# openadc_ztex.net
KiCad netlist of a schematic drawn in EAGLE
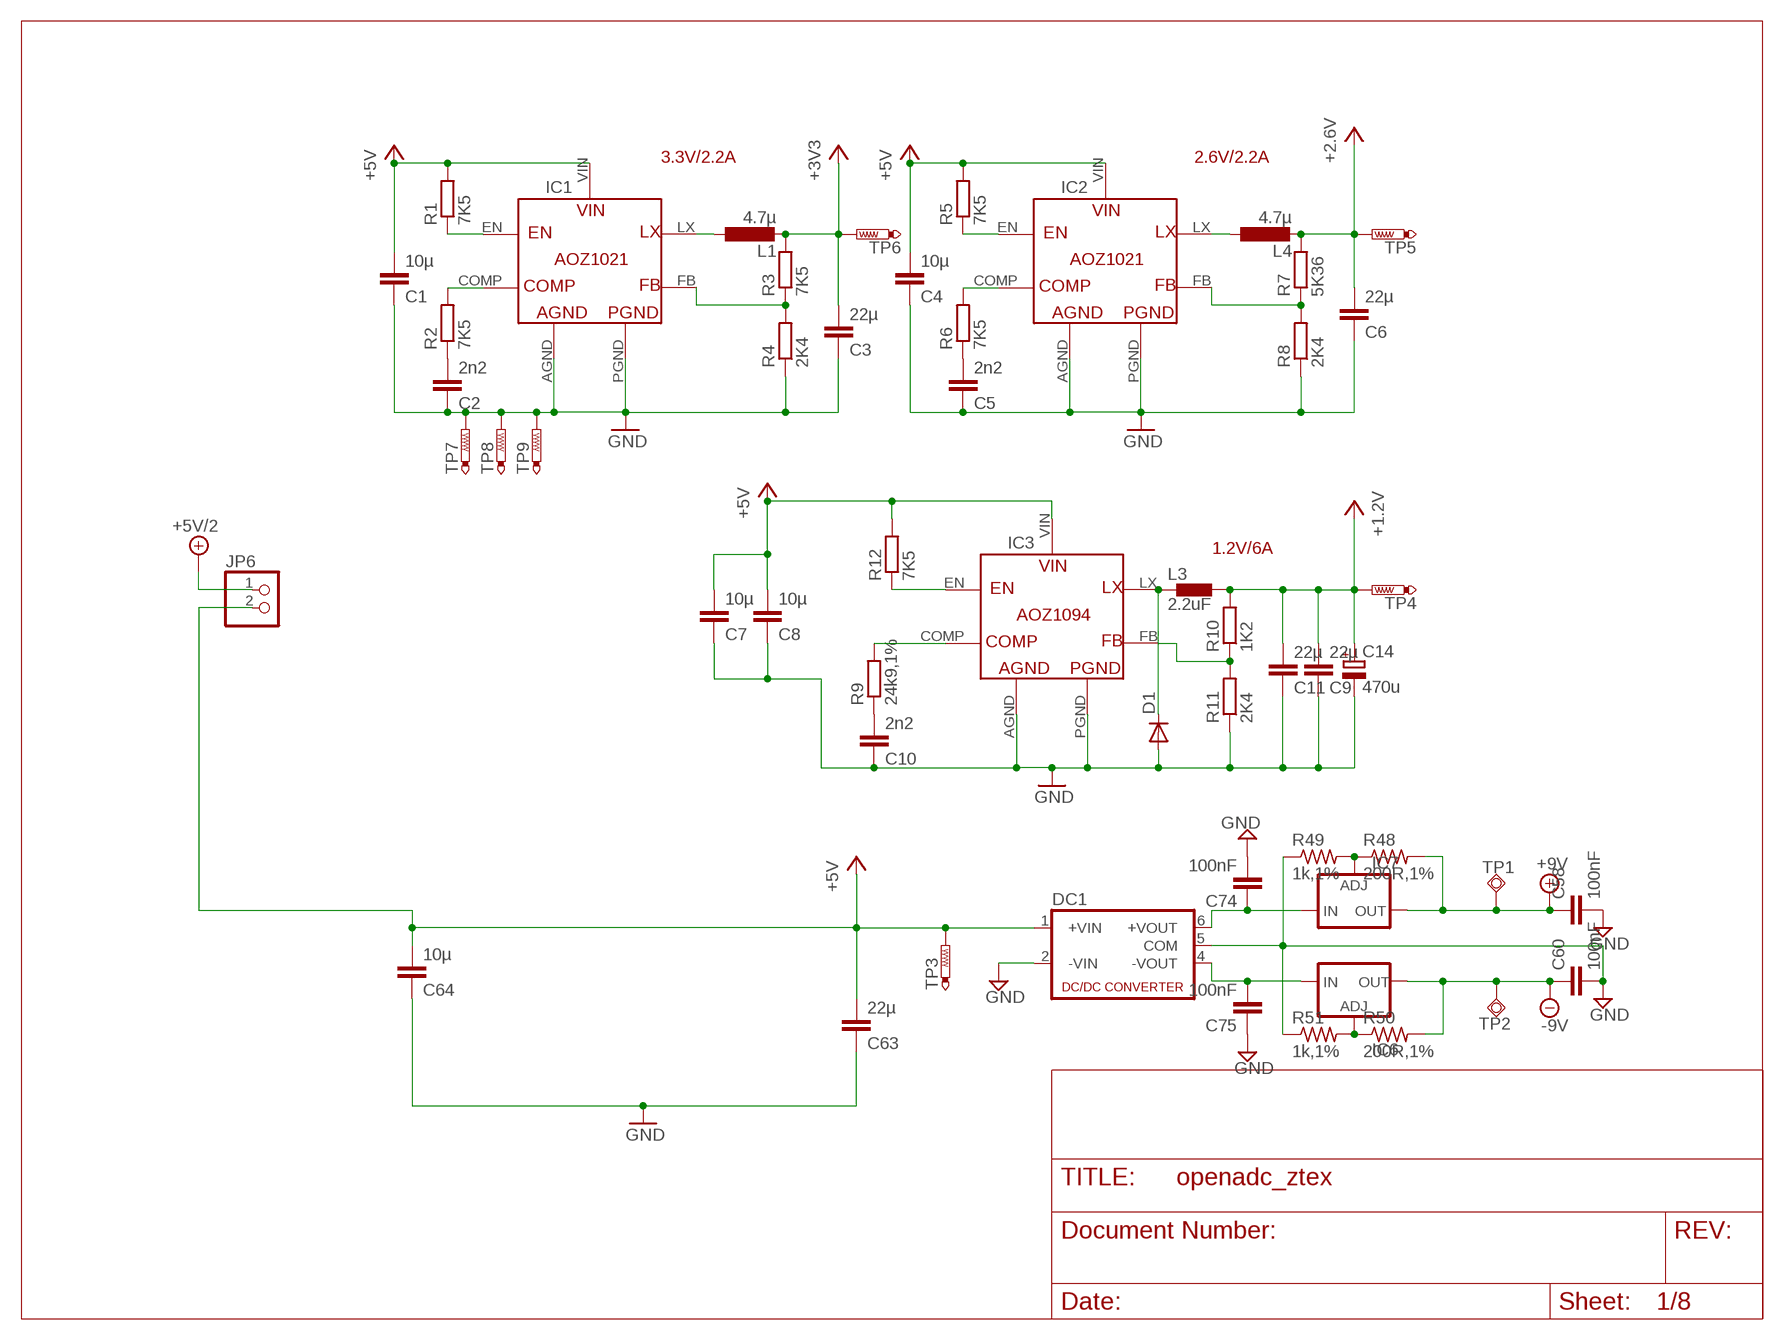
[diagram p0: schematic, sheet 1]
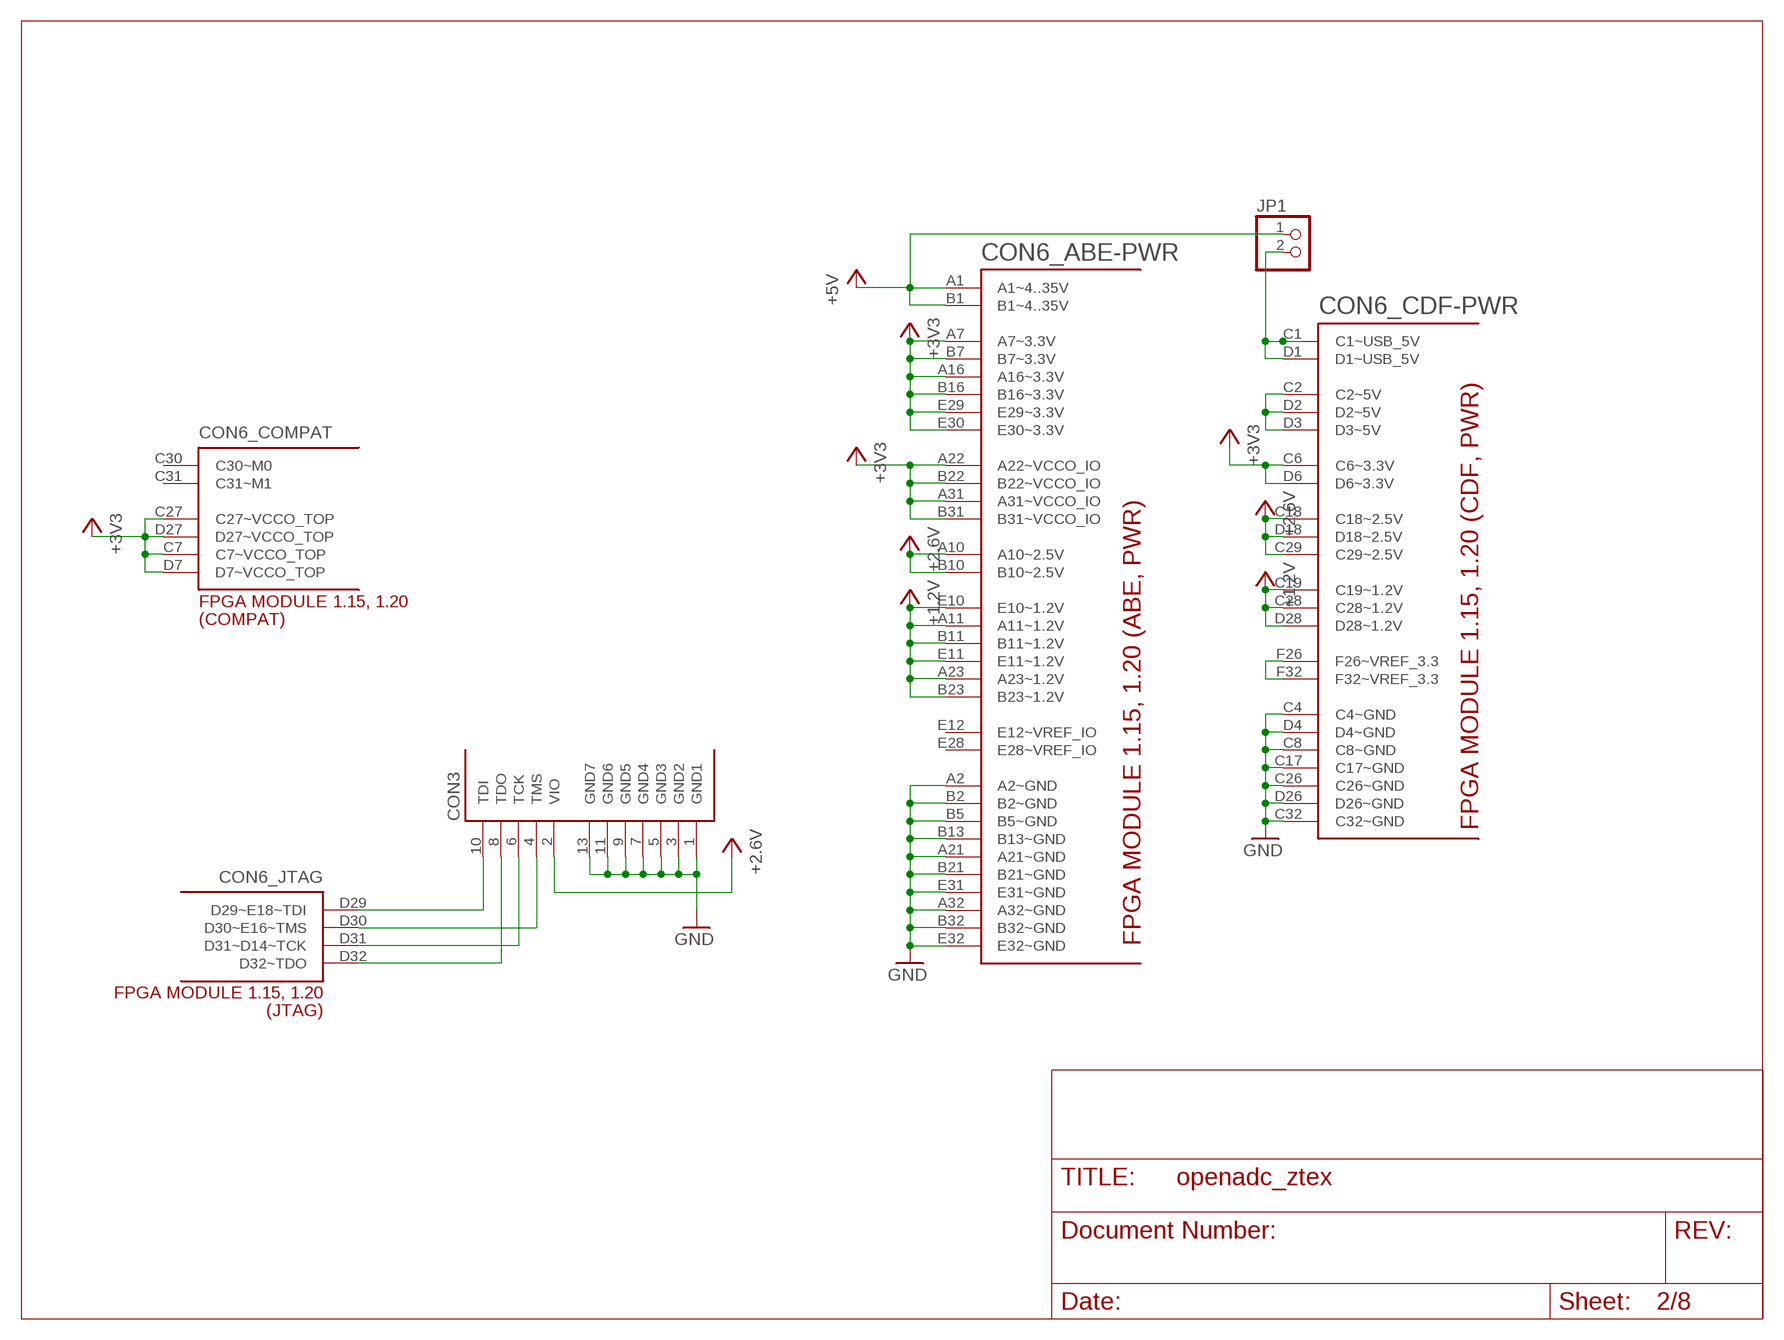
[diagram p1: schematic, sheet 2]
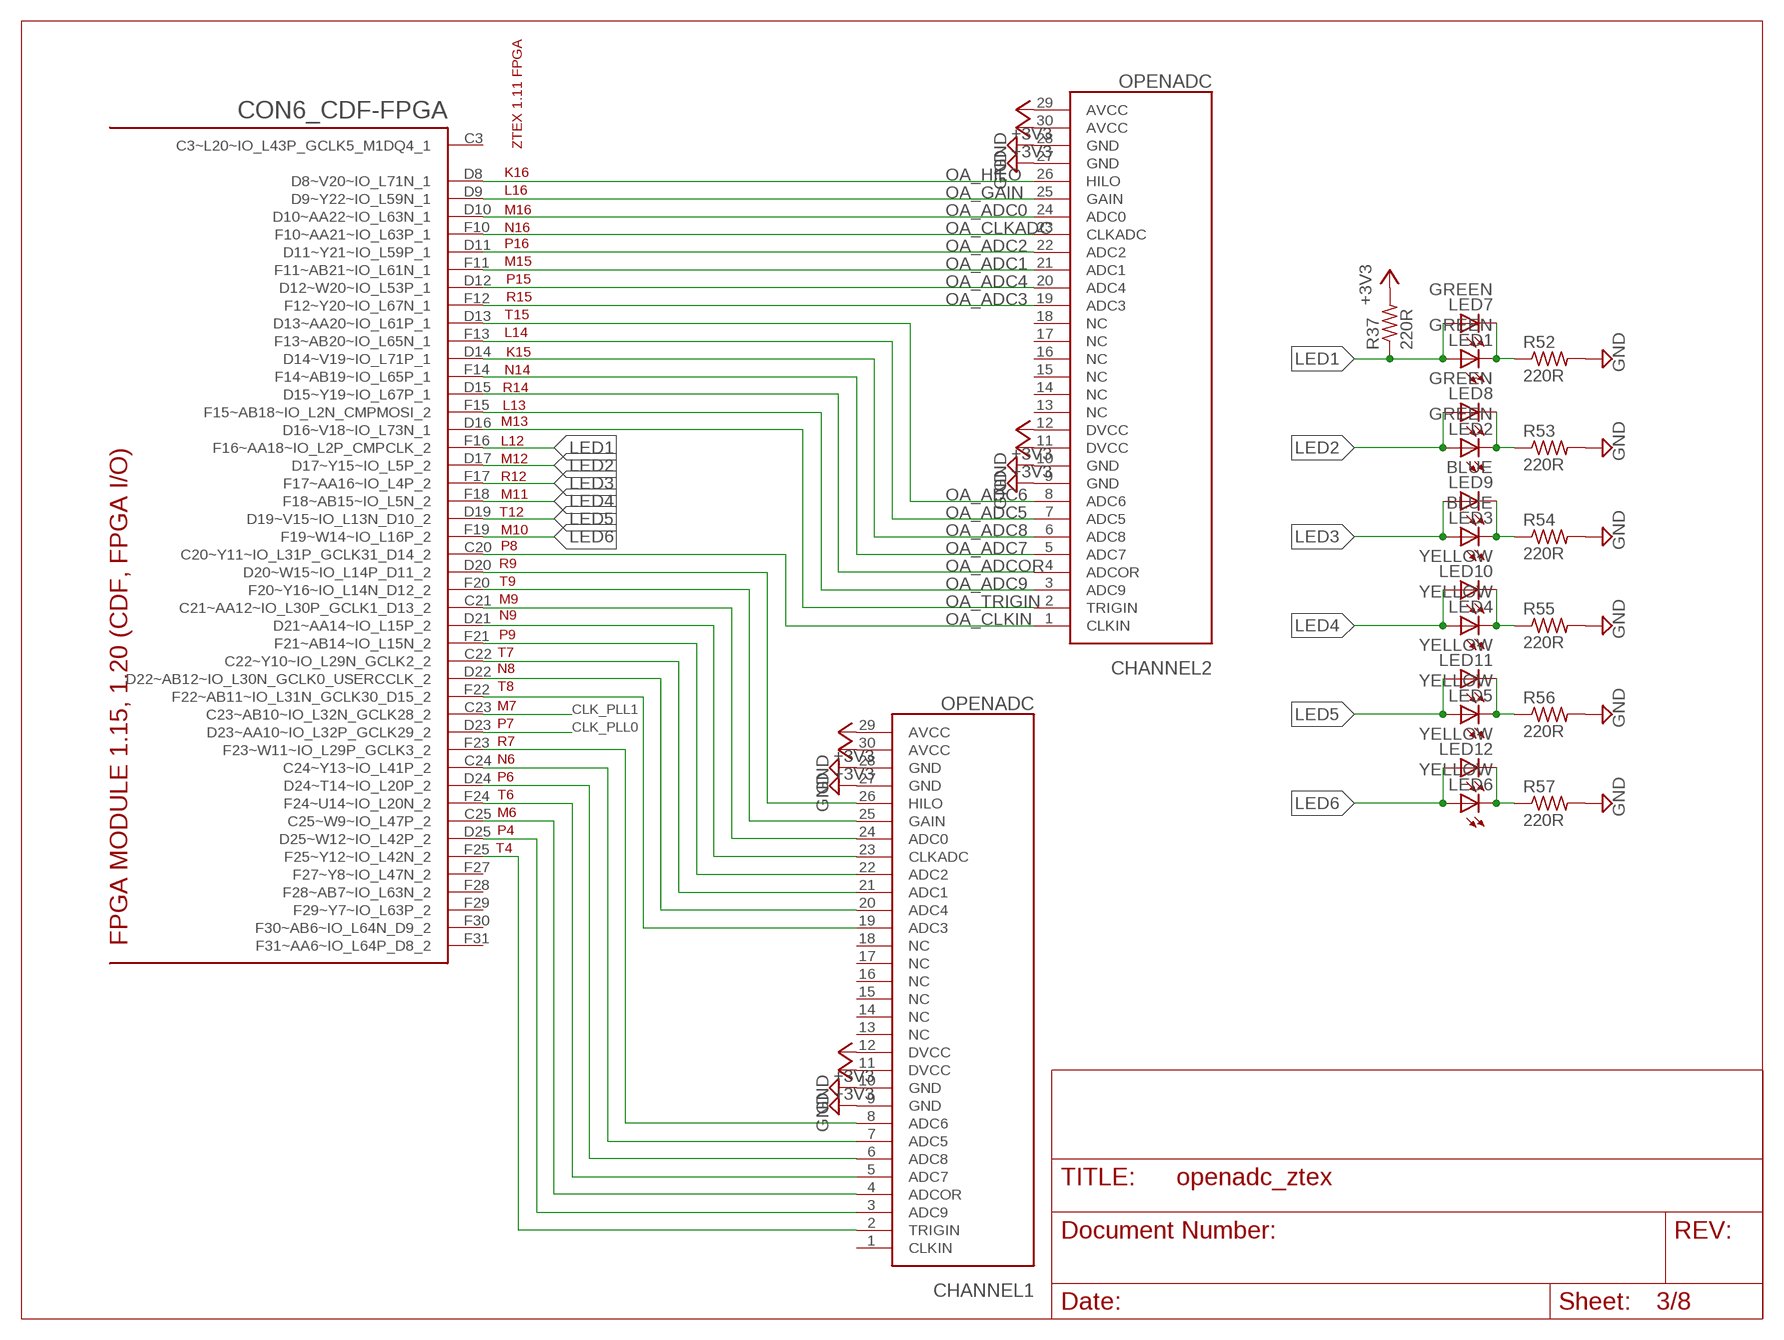
[diagram p2: schematic, sheet 3]
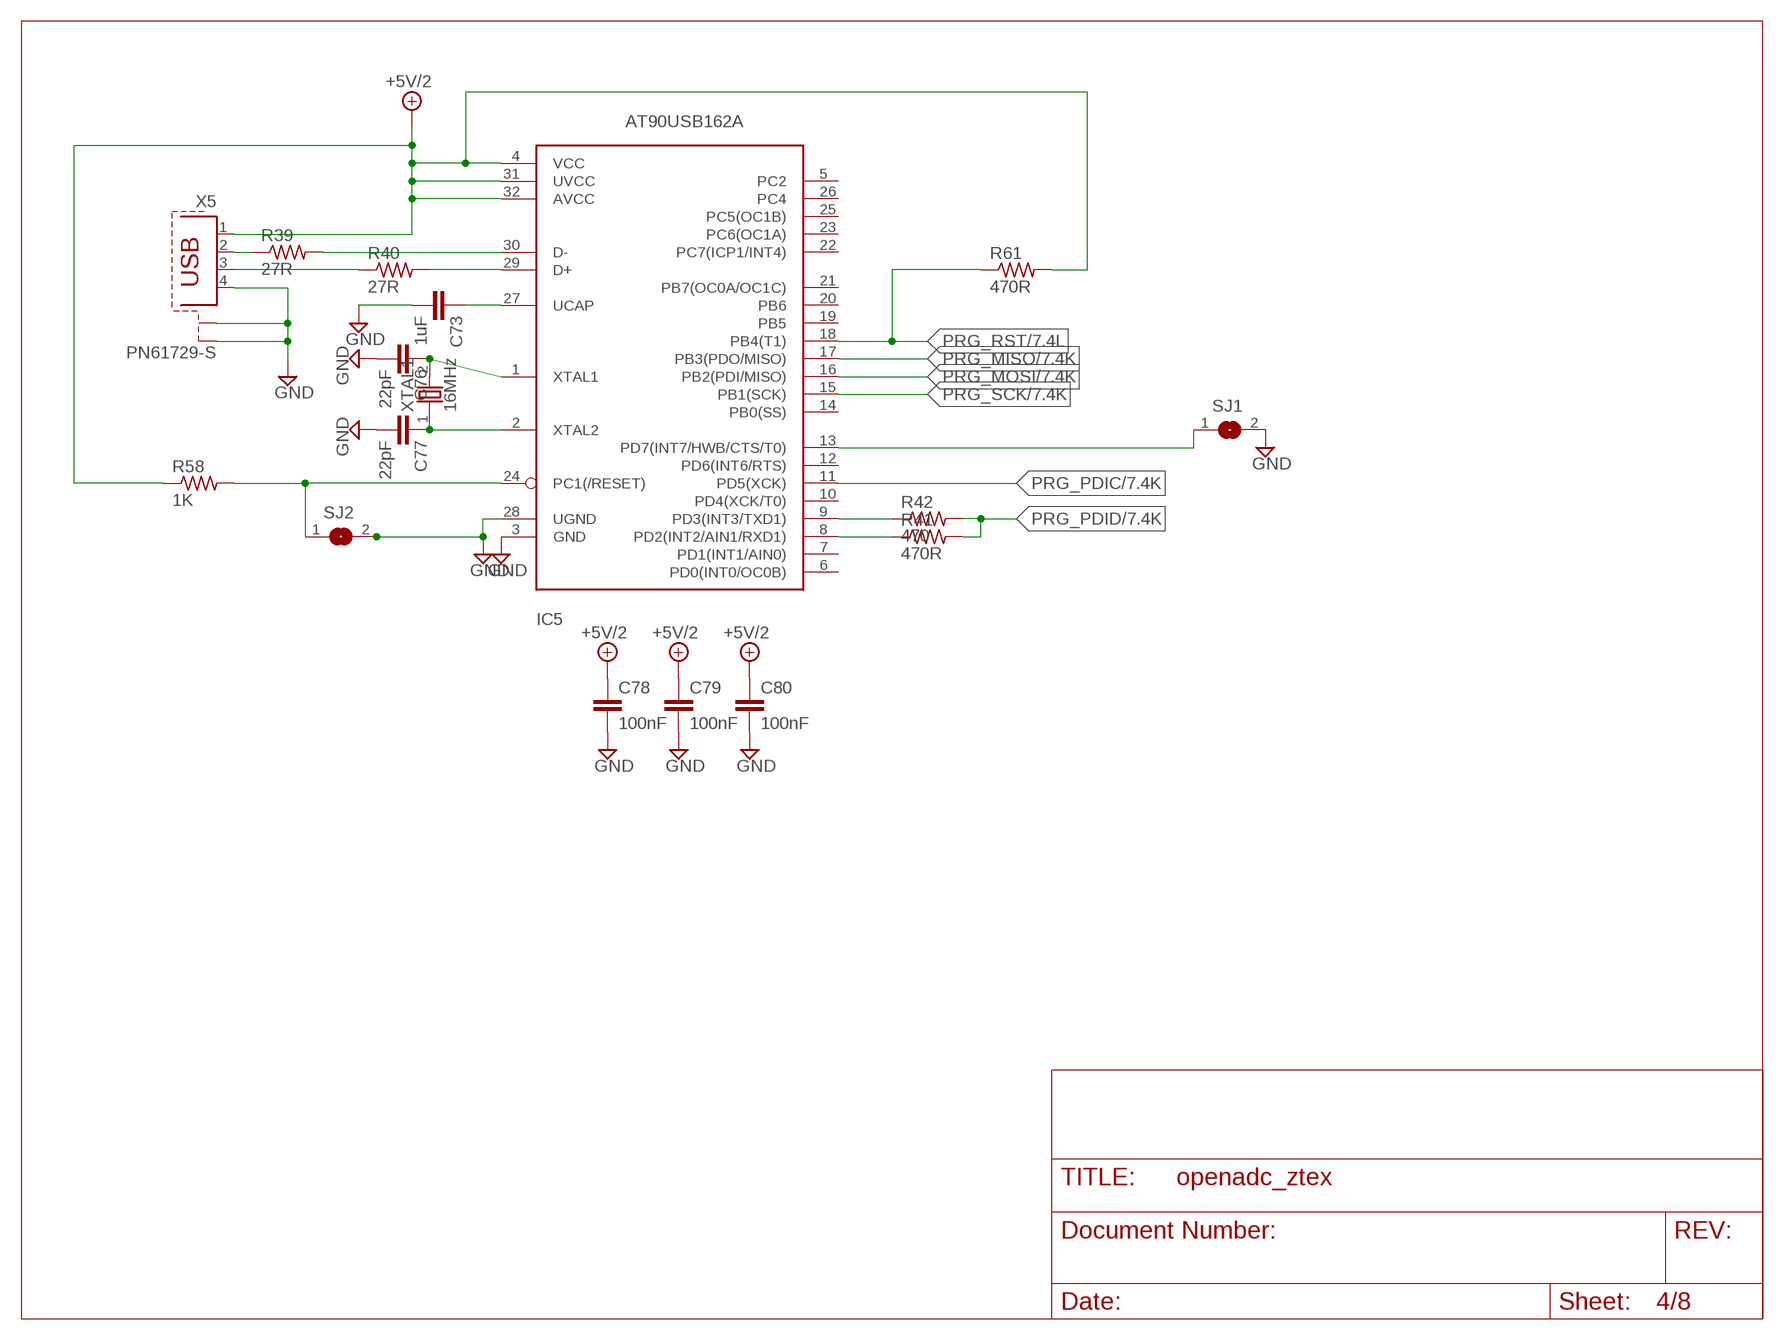
[diagram p3: schematic, sheet 4]
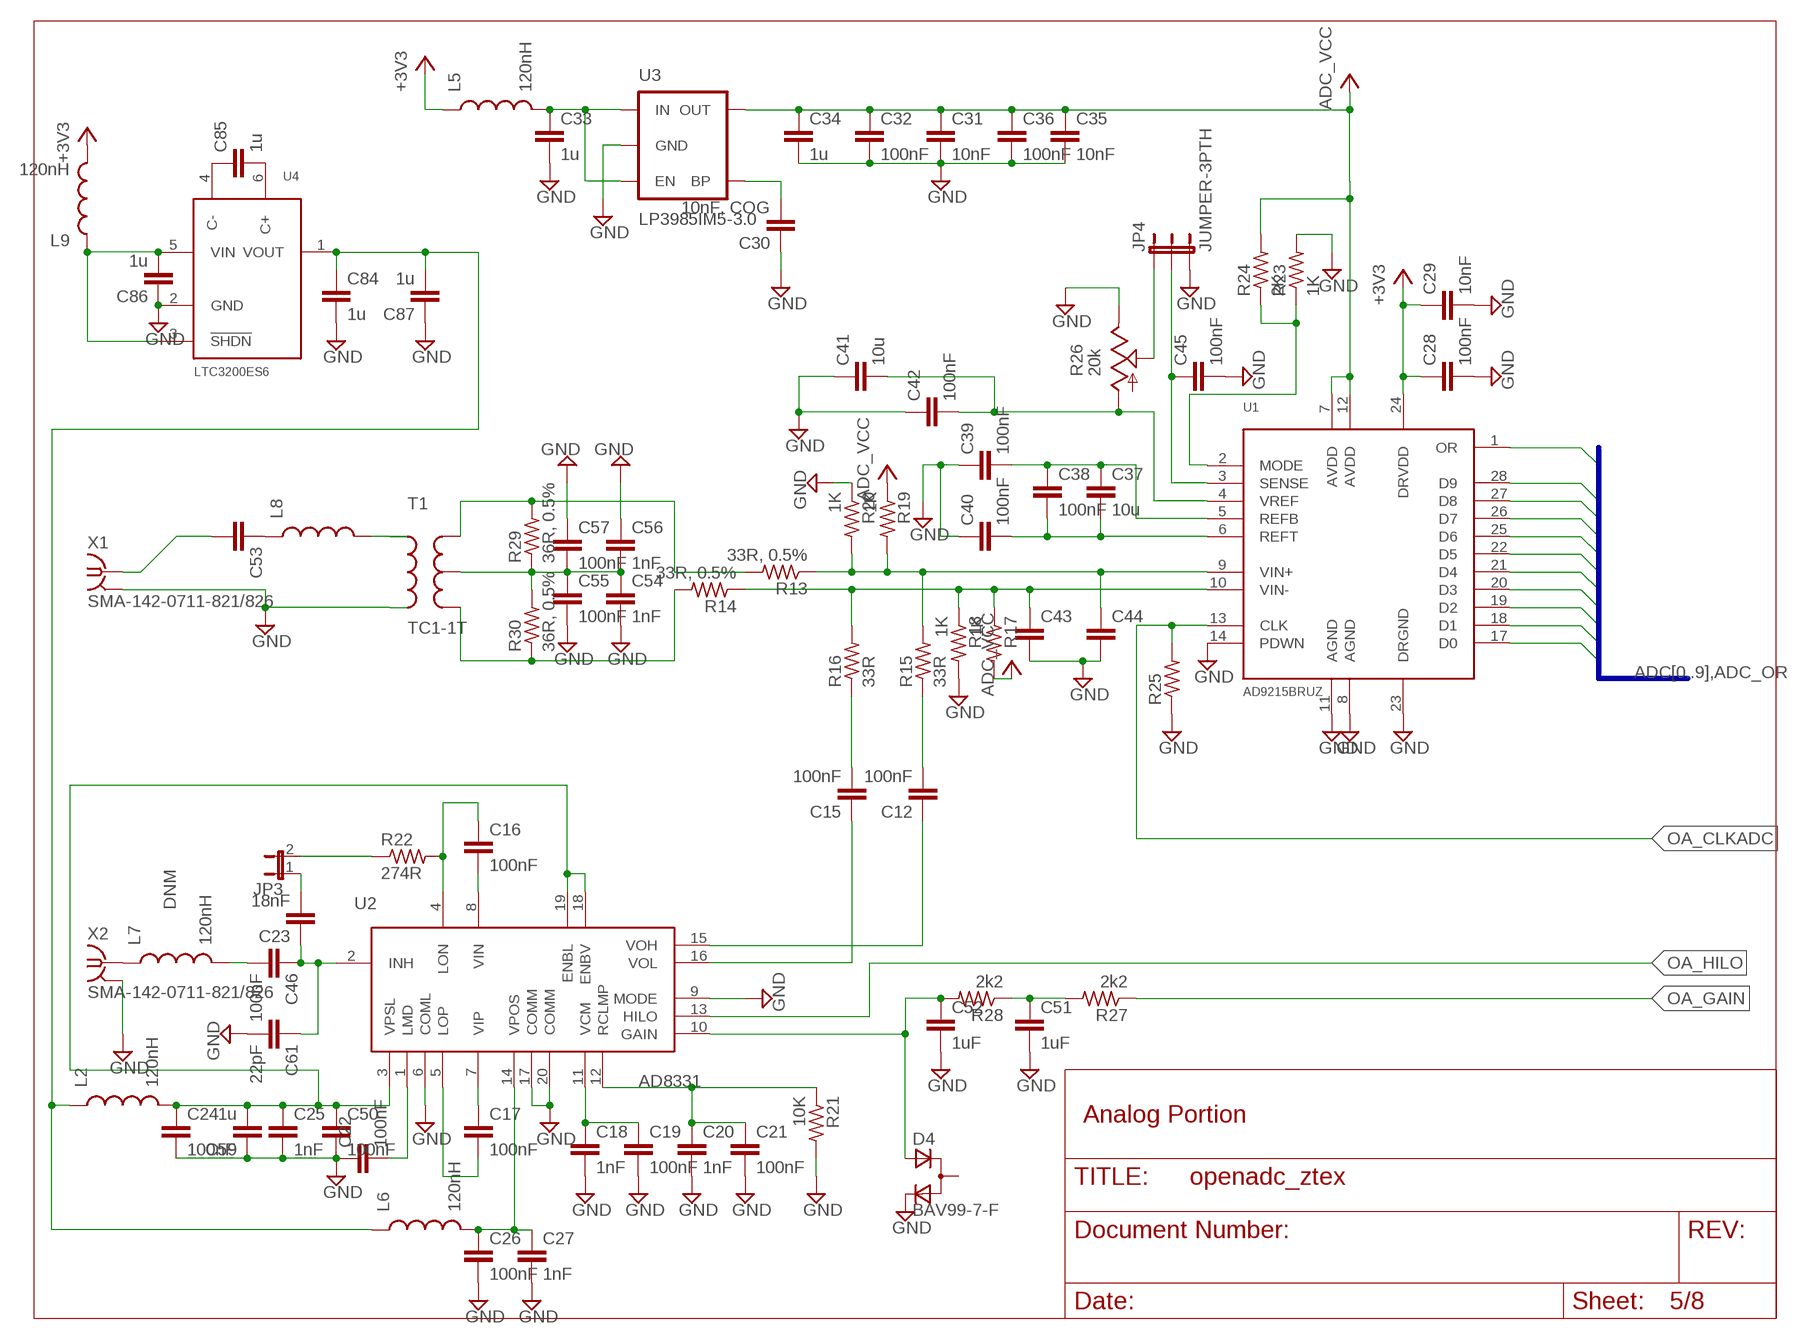
[diagram p4: schematic, sheet 5]
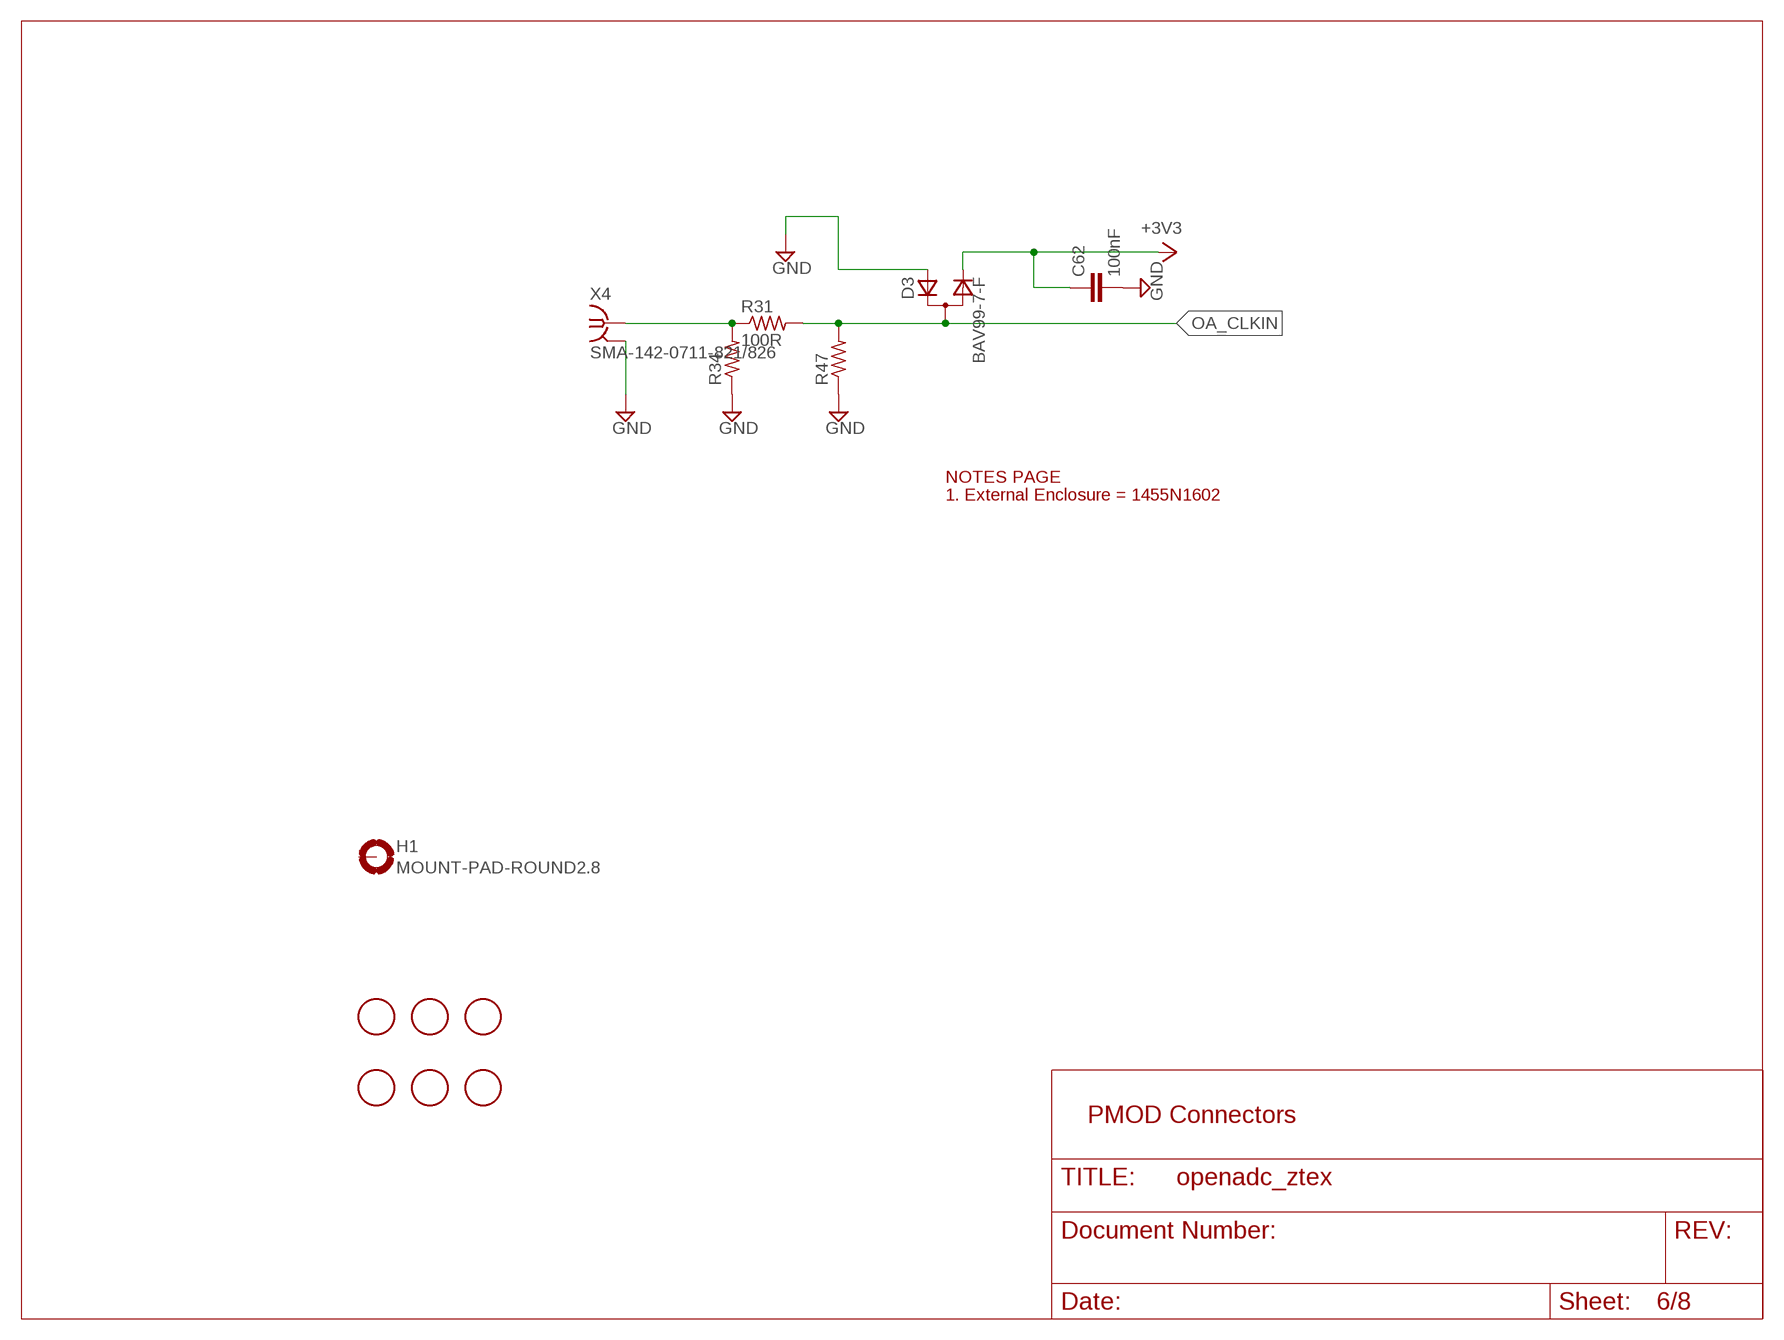
[diagram p5: schematic, sheet 6]
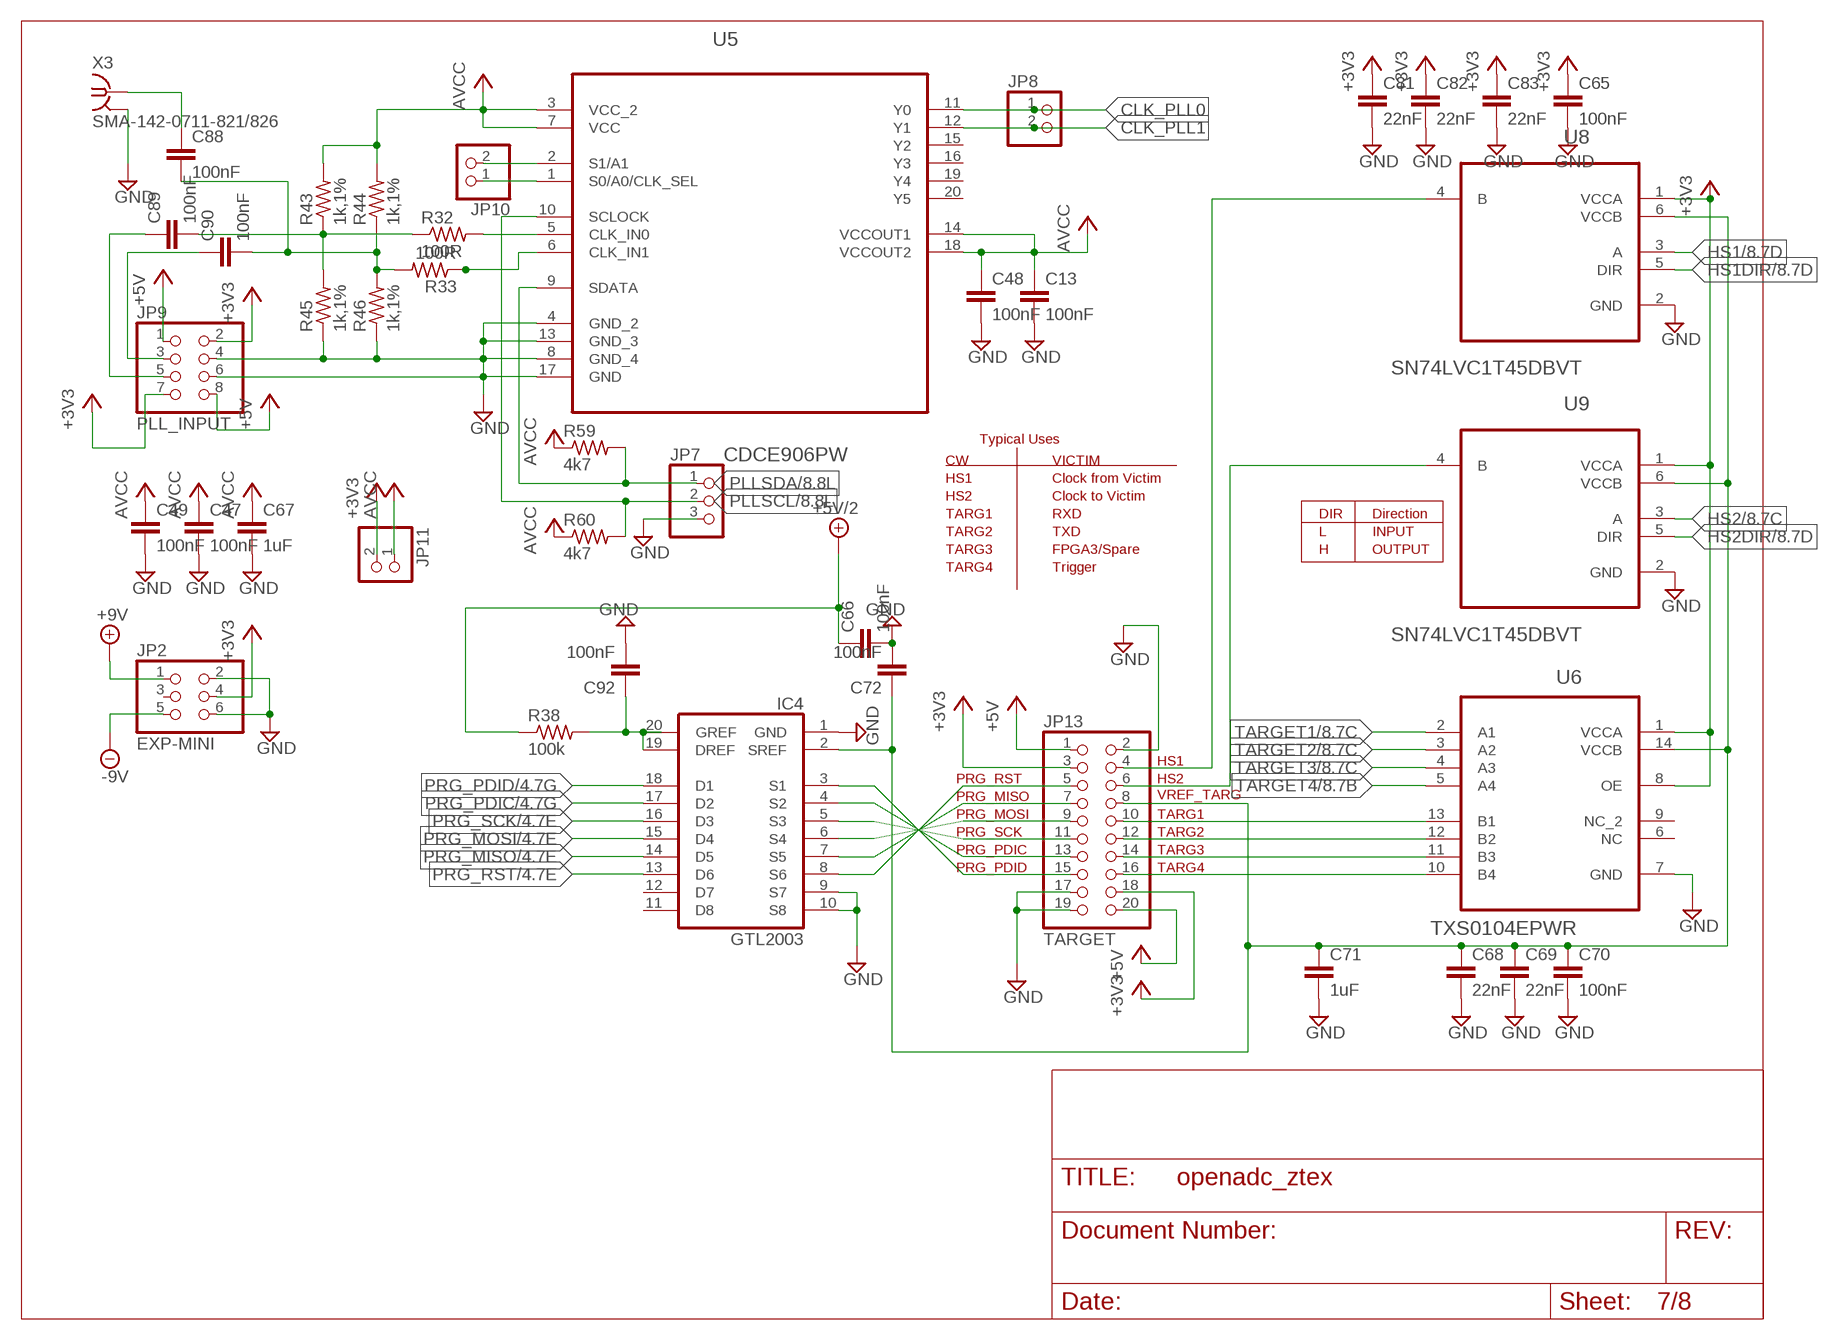
[diagram p6: schematic, sheet 7]
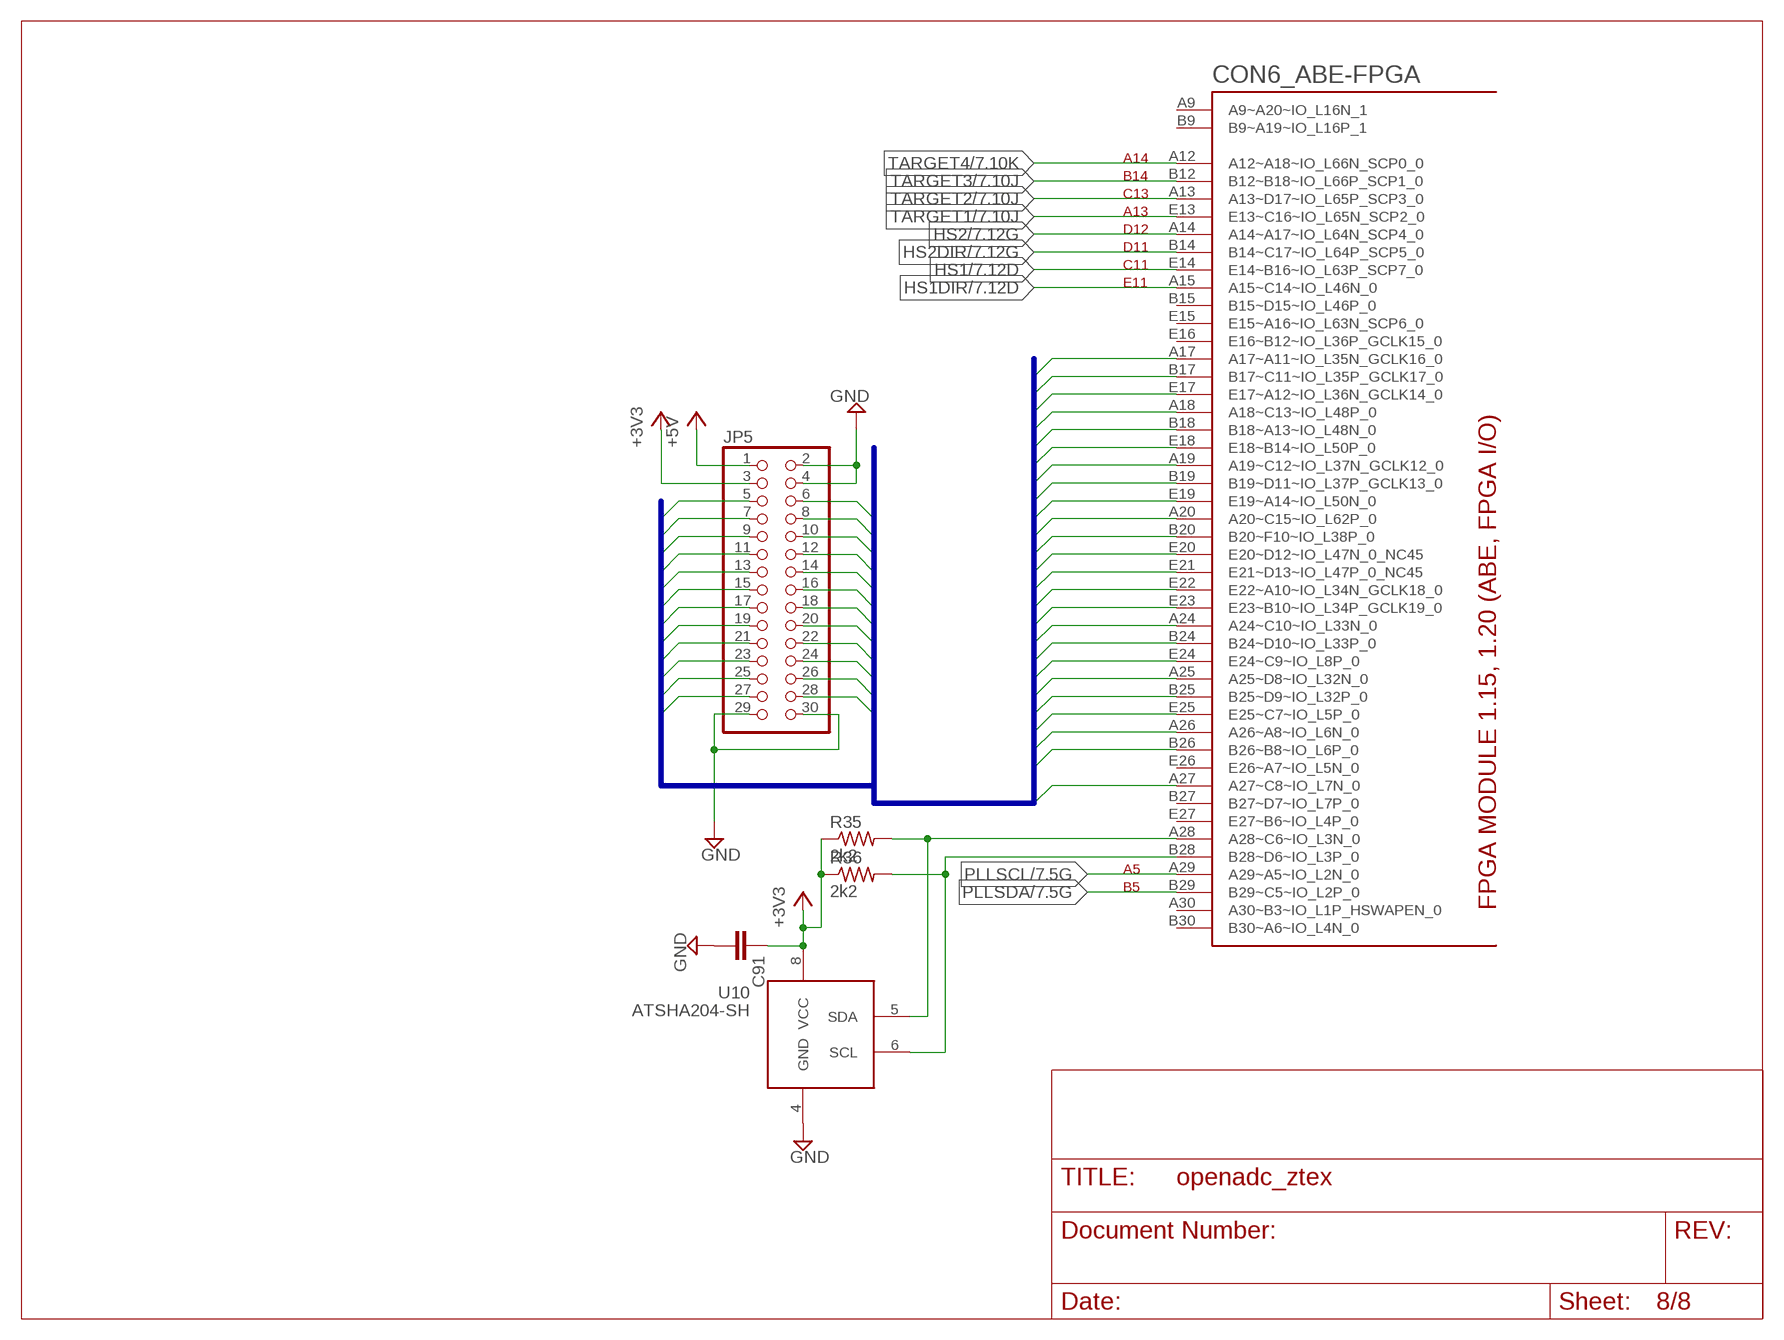
[diagram p7: schematic, sheet 8]

(export (version "E")
  (design (tool "Eeschema 10.0.6"))
  (components
    (comp (ref "C12")
      (value "100nF")
      (footprint "eagle-import:C0603K")
      (libsource (lib "eagle-import") (part "rcl_C-EUC0603K"))
    )
    (comp (ref "C15")
      (value "100nF")
      (footprint "eagle-import:C0603K")
      (libsource (lib "eagle-import") (part "rcl_C-EUC0603K"))
    )
    (comp (ref "C16")
      (value "100nF")
      (footprint "eagle-import:C0402")
      (libsource (lib "eagle-import") (part "rcl_C-EUC0402"))
    )
    (comp (ref "C17")
      (value "100nF")
      (footprint "eagle-import:C0402")
      (libsource (lib "eagle-import") (part "rcl_C-EUC0402"))
    )
    (comp (ref "C18")
      (value "1nF")
      (footprint "eagle-import:C0402")
      (fields (field (name "PART#") "C1005X7R1E102K"))
      (libsource (lib "eagle-import") (part "rcl_C-EUC0402"))
    )
    (comp (ref "C19")
      (value "100nF")
      (footprint "eagle-import:C0402")
      (fields (field (name "PART#") "GRM155R61A104KA01D"))
      (libsource (lib "eagle-import") (part "rcl_C-EUC0402"))
    )
    (comp (ref "C20")
      (value "1nF")
      (footprint "eagle-import:C0402")
      (fields (field (name "PART#") "C1005X7R1E102K"))
      (libsource (lib "eagle-import") (part "rcl_C-EUC0402"))
    )
    (comp (ref "C21")
      (value "100nF")
      (footprint "eagle-import:C0402")
      (fields (field (name "PART#") "GRM155R61A104KA01D"))
      (libsource (lib "eagle-import") (part "rcl_C-EUC0402"))
    )
    (comp (ref "C22")
      (value "100nF")
      (footprint "eagle-import:C0402")
      (fields (field (name "PART#") "GRM155R61A104KA01D"))
      (libsource (lib "eagle-import") (part "rcl_C-EUC0402"))
    )
    (comp (ref "C23")
      (value "18nF")
      (footprint "eagle-import:C0603")
      (libsource (lib "eagle-import") (part "rcl_C-EUC0603"))
    )
    (comp (ref "C24")
      (value "100nF")
      (footprint "eagle-import:C0402")
      (fields (field (name "PART#") "GRM155R61A104KA01D"))
      (libsource (lib "eagle-import") (part "rcl_C-EUC0402"))
    )
    (comp (ref "C25")
      (value "1nF")
      (footprint "eagle-import:C0402")
      (fields (field (name "PART#") "C1005X7R1E102K"))
      (libsource (lib "eagle-import") (part "rcl_C-EUC0402"))
    )
    (comp (ref "C26")
      (value "100nF")
      (footprint "eagle-import:C0402")
      (fields (field (name "PART#") "GRM155R61A104KA01D"))
      (libsource (lib "eagle-import") (part "rcl_C-EUC0402"))
    )
    (comp (ref "C27")
      (value "1nF")
      (footprint "eagle-import:C0402")
      (fields (field (name "PART#") "C1005X7R1E102K"))
      (libsource (lib "eagle-import") (part "rcl_C-EUC0402"))
    )
    (comp (ref "C28")
      (value "100nF")
      (footprint "eagle-import:C0402")
      (fields (field (name "PART#") "GRM155R61A104KA01D"))
      (libsource (lib "eagle-import") (part "rcl_C-EUC0402"))
    )
    (comp (ref "C29")
      (value "10nF")
      (footprint "eagle-import:C0402")
      (libsource (lib "eagle-import") (part "rcl_C-EUC0402"))
    )
    (comp (ref "C30")
      (value "10nF, COG")
      (footprint "eagle-import:C0402")
      (libsource (lib "eagle-import") (part "rcl_C-EUC0402"))
    )
    (comp (ref "C31")
      (value "10nF")
      (footprint "eagle-import:C0402")
      (fields (field (name "PART#") "GRM155R71E103KA01D"))
      (libsource (lib "eagle-import") (part "rcl_C-EUC0402"))
    )
    (comp (ref "C32")
      (value "100nF")
      (footprint "eagle-import:C0402")
      (fields (field (name "PART#") "GRM155R61A104KA01D"))
      (libsource (lib "eagle-import") (part "rcl_C-EUC0402"))
    )
    (comp (ref "C33")
      (value "1u")
      (footprint "eagle-import:C0603")
      (fields (field (name "PART#") "GRM188R61A105KA61D"))
      (libsource (lib "eagle-import") (part "rcl_C-EUC0603"))
    )
    (comp (ref "C34")
      (value "1u")
      (footprint "eagle-import:C0603")
      (fields (field (name "PART#") "GRM188R61A105KA61D"))
      (libsource (lib "eagle-import") (part "rcl_C-EUC0603"))
    )
    (comp (ref "C35")
      (value "10nF")
      (footprint "eagle-import:C0402")
      (fields (field (name "PART#") "GRM155R71E103KA01D"))
      (libsource (lib "eagle-import") (part "rcl_C-EUC0402"))
    )
    (comp (ref "C36")
      (value "100nF")
      (footprint "eagle-import:C0402")
      (fields (field (name "PART#") "GRM155R61A104KA01D"))
      (libsource (lib "eagle-import") (part "rcl_C-EUC0402"))
    )
    (comp (ref "C37")
      (value "10u")
      (footprint "eagle-import:C0603")
      (libsource (lib "eagle-import") (part "rcl_C-EUC0603"))
    )
    (comp (ref "C38")
      (value "100nF")
      (footprint "eagle-import:C0402")
      (fields (field (name "PART#") "GRM155R61A104KA01D"))
      (libsource (lib "eagle-import") (part "rcl_C-EUC0402"))
    )
    (comp (ref "C39")
      (value "100nF")
      (footprint "eagle-import:C0402")
      (fields (field (name "PART#") "GRM155R61A104KA01D"))
      (libsource (lib "eagle-import") (part "rcl_C-EUC0402"))
    )
    (comp (ref "C40")
      (value "100nF")
      (footprint "eagle-import:C0402")
      (fields (field (name "PART#") "GRM155R61A104KA01D"))
      (libsource (lib "eagle-import") (part "rcl_C-EUC0402"))
    )
    (comp (ref "C41")
      (value "10u")
      (footprint "eagle-import:C0603")
      (libsource (lib "eagle-import") (part "rcl_C-EUC0603"))
    )
    (comp (ref "C42")
      (value "100nF")
      (footprint "eagle-import:C0402")
      (fields (field (name "PART#") "GRM155R61A104KA01D"))
      (libsource (lib "eagle-import") (part "rcl_C-EUC0402"))
    )
    (comp (ref "C43")
      (value "C-EUC0402")
      (footprint "eagle-import:C0402")
      (libsource (lib "eagle-import") (part "rcl_C-EUC0402"))
    )
    (comp (ref "C44")
      (value "C-EUC0402")
      (footprint "eagle-import:C0402")
      (libsource (lib "eagle-import") (part "rcl_C-EUC0402"))
    )
    (comp (ref "C45")
      (value "100nF")
      (footprint "eagle-import:C0402")
      (fields (field (name "PART#") "GRM155R61A104KA01D"))
      (libsource (lib "eagle-import") (part "rcl_C-EUC0402"))
    )
    (comp (ref "C46")
      (value "100nF")
      (footprint "eagle-import:C0603K")
      (libsource (lib "eagle-import") (part "rcl_C-EUC0603K"))
    )
    (comp (ref "C50")
      (value "100nF")
      (footprint "eagle-import:C0402")
      (fields (field (name "PART#") "GRM155R61A104KA01D"))
      (libsource (lib "eagle-import") (part "rcl_C-EUC0402"))
    )
    (comp (ref "C51")
      (value "1uF")
      (footprint "eagle-import:C0603")
      (libsource (lib "eagle-import") (part "rcl_C-EUC0603"))
    )
    (comp (ref "C52")
      (value "1uF")
      (footprint "eagle-import:C0603")
      (libsource (lib "eagle-import") (part "rcl_C-EUC0603"))
    )
    (comp (ref "C53")
      (value "C-EUC0603K")
      (footprint "eagle-import:C0603K")
      (libsource (lib "eagle-import") (part "rcl_C-EUC0603K"))
    )
    (comp (ref "C54")
      (value "1nF")
      (footprint "eagle-import:C0402")
      (fields (field (name "PART#") "C1005X7R1E102K"))
      (libsource (lib "eagle-import") (part "rcl_C-EUC0402"))
    )
    (comp (ref "C55")
      (value "100nF")
      (footprint "eagle-import:C0402")
      (fields (field (name "PART#") "GRM155R61A104KA01D"))
      (libsource (lib "eagle-import") (part "rcl_C-EUC0402"))
    )
    (comp (ref "C56")
      (value "1nF")
      (footprint "eagle-import:C0402")
      (fields (field (name "PART#") "C1005X7R1E102K"))
      (libsource (lib "eagle-import") (part "rcl_C-EUC0402"))
    )
    (comp (ref "C57")
      (value "100nF")
      (footprint "eagle-import:C0402")
      (fields (field (name "PART#") "GRM155R61A104KA01D"))
      (libsource (lib "eagle-import") (part "rcl_C-EUC0402"))
    )
    (comp (ref "C59")
      (value "1u")
      (footprint "eagle-import:C0402")
      (fields (field (name "PART#") "GRM188R61A105KA61D"))
      (libsource (lib "eagle-import") (part "rcl_C-EUC0402"))
    )
    (comp (ref "C61")
      (value "22pF")
      (footprint "eagle-import:C0603")
      (libsource (lib "eagle-import") (part "rcl_C-EUC0603"))
    )
    (comp (ref "C84")
      (value "1u")
      (footprint "eagle-import:C0603")
      (fields (field (name "PART#") "GRM188R61A105KA61D"))
      (libsource (lib "eagle-import") (part "rcl_C-EUC0603"))
    )
    (comp (ref "C85")
      (value "1u")
      (footprint "eagle-import:C0603")
      (fields (field (name "PART#") "GRM188R61A105KA61D"))
      (libsource (lib "eagle-import") (part "rcl_C-EUC0603"))
    )
    (comp (ref "C86")
      (value "1u")
      (footprint "eagle-import:C0603")
      (fields (field (name "PART#") "GRM188R61A105KA61D"))
      (libsource (lib "eagle-import") (part "rcl_C-EUC0603"))
    )
    (comp (ref "C87")
      (value "1u")
      (footprint "eagle-import:C0603")
      (fields (field (name "PART#") "GRM188R61A105KA61D"))
      (libsource (lib "eagle-import") (part "rcl_C-EUC0603"))
    )
    (comp (ref "D4")
      (value "BAV99-7-F")
      (footprint "eagle-import:SOT-23")
      (libsource (lib "eagle-import") (part "D_ACACSOT23"))
    )
    (comp (ref "JP3")
      (value "JUMPER-2SMD-NC")
      (footprint "eagle-import:SJ_2S")
      (libsource (lib "eagle-import") (part "JUMPER-2SMD-NC"))
    )
    (comp (ref "JP4")
      (value "JUMPER-3PTH")
      (footprint "eagle-import:1X03")
      (libsource (lib "eagle-import") (part "JUMPER-3PTH"))
    )
    (comp (ref "L2")
      (value "120nH")
      (footprint "eagle-import:0603")
      (fields (field (name "PART#") "MLF1608DR12M"))
      (libsource (lib "eagle-import") (part "INDUCTOR0603"))
    )
    (comp (ref "L5")
      (value "120nH")
      (footprint "eagle-import:0603")
      (libsource (lib "eagle-import") (part "INDUCTOR0603"))
    )
    (comp (ref "L6")
      (value "120nH")
      (footprint "eagle-import:0603")
      (libsource (lib "eagle-import") (part "INDUCTOR0603"))
    )
    (comp (ref "L7")
      (value "120nH")
      (footprint "eagle-import:0603")
      (libsource (lib "eagle-import") (part "INDUCTOR0603"))
    )
    (comp (ref "L8")
      (value "INDUCTOR0603")
      (footprint "eagle-import:0603")
      (libsource (lib "eagle-import") (part "INDUCTOR0603"))
    )
    (comp (ref "L9")
      (value "120nH")
      (footprint "eagle-import:0603")
      (libsource (lib "eagle-import") (part "INDUCTOR0603"))
    )
    (comp (ref "R13")
      (value "33R, 0.5%")
      (footprint "eagle-import:R0603")
      (libsource (lib "eagle-import") (part "R-US_R0603"))
    )
    (comp (ref "R14")
      (value "33R, 0.5%")
      (footprint "eagle-import:R0603")
      (libsource (lib "eagle-import") (part "R-US_R0603"))
    )
    (comp (ref "R15")
      (value "33R")
      (footprint "eagle-import:R0603")
      (libsource (lib "eagle-import") (part "R-US_R0603"))
    )
    (comp (ref "R16")
      (value "33R")
      (footprint "eagle-import:R0603")
      (libsource (lib "eagle-import") (part "R-US_R0603"))
    )
    (comp (ref "R17")
      (value "1K")
      (footprint "eagle-import:R0402")
      (libsource (lib "eagle-import") (part "R-US_R0402"))
    )
    (comp (ref "R18")
      (value "1K")
      (footprint "eagle-import:R0402")
      (libsource (lib "eagle-import") (part "R-US_R0402"))
    )
    (comp (ref "R19")
      (value "1K")
      (footprint "eagle-import:R0402")
      (libsource (lib "eagle-import") (part "R-US_R0402"))
    )
    (comp (ref "R20")
      (value "1K")
      (footprint "eagle-import:R0402")
      (libsource (lib "eagle-import") (part "R-US_R0402"))
    )
    (comp (ref "R21")
      (value "10K")
      (footprint "eagle-import:R0603")
      (libsource (lib "eagle-import") (part "R-US_R0603"))
    )
    (comp (ref "R22")
      (value "274R")
      (footprint "eagle-import:R0603")
      (libsource (lib "eagle-import") (part "R-US_R0603"))
    )
    (comp (ref "R23")
      (value "1K")
      (footprint "eagle-import:R0402")
      (libsource (lib "eagle-import") (part "R-US_R0402"))
    )
    (comp (ref "R24")
      (value "2K")
      (footprint "eagle-import:R0603")
      (libsource (lib "eagle-import") (part "R-US_R0603"))
    )
    (comp (ref "R25")
      (value "R-US_R0603")
      (footprint "eagle-import:R0603")
      (libsource (lib "eagle-import") (part "R-US_R0603"))
    )
    (comp (ref "R26")
      (value "20k")
      (footprint "eagle-import:3361P")
      (fields (field (name "PART#") "3361P-1-203GLF"))
      (libsource (lib "eagle-import") (part "TRIM_US-3361P"))
    )
    (comp (ref "R27")
      (value "2k2")
      (footprint "eagle-import:R0603")
      (libsource (lib "eagle-import") (part "R-US_R0603"))
    )
    (comp (ref "R28")
      (value "2k2")
      (footprint "eagle-import:R0603")
      (libsource (lib "eagle-import") (part "R-US_R0603"))
    )
    (comp (ref "R29")
      (value "36R, 0.5%")
      (footprint "eagle-import:R0603")
      (libsource (lib "eagle-import") (part "R-US_R0603"))
    )
    (comp (ref "R30")
      (value "36R, 0.5%")
      (footprint "eagle-import:R0603")
      (libsource (lib "eagle-import") (part "R-US_R0603"))
    )
    (comp (ref "T1")
      (value "TC1-1T")
      (footprint "eagle-import:AT224-1A")
      (libsource (lib "eagle-import") (part "TC1-1T"))
    )
    (comp (ref "U1")
      (value "AD9215BRUZ")
      (footprint "eagle-import:TSSOP28")
      (libsource (lib "eagle-import") (part "AD9215BRUZ"))
    )
    (comp (ref "U2")
      (value "AD8331")
      (footprint "eagle-import:QSOP20")
      (fields (field (name "PART#") "AD8331ARQZ"))
      (libsource (lib "eagle-import") (part "AD8331"))
    )
    (comp (ref "U3")
      (value "LP3985IM5-3.0")
      (footprint "eagle-import:SOT23-5")
      (libsource (lib "eagle-import") (part "V_REG_LDOSMD"))
    )
    (comp (ref "U4")
      (value "LTC3200ES6")
      (footprint "eagle-import:SOT23-6L")
      (libsource (lib "eagle-import") (part "LTC3200ES6"))
    )
    (comp (ref "X1")
      (value "SMA-142-0711-821/826")
      (footprint "eagle-import:J502-ND-142-0711-821_826")
      (fields (field (name "MF") "JOHNSON COMPONENTS") (field (name "MPN") "142-0711-821"))
      (libsource (lib "eagle-import") (part "SMA-142-0711-821/826"))
    )
    (comp (ref "X2")
      (value "SMA-142-0711-821/826")
      (footprint "eagle-import:J502-ND-142-0711-821_826")
      (fields (field (name "MF") "JOHNSON COMPONENTS") (field (name "MPN") "142-0711-821"))
      (libsource (lib "eagle-import") (part "SMA-142-0711-821/826"))
    )
    (comp (ref "CON3")
      (value "JTAG")
      (footprint "eagle-import:JTAG")
      (libsource (lib "eagle-import") (part "JTAG"))
    )
    (comp (ref "CON6")
      (value "USB-FPGA1.15")
      (footprint "eagle-import:USB-FPGA1.15")
      (libsource (lib "eagle-import") (part "USB-FPGA1.15"))
    )
    (comp (ref "JP1")
      (value "PINHD-1X2")
      (footprint "eagle-import:1X02")
      (libsource (lib "eagle-import") (part "PINHD-1X2"))
    )
    (comp (ref "C73")
      (value "1uF")
      (footprint "eagle-import:C0603")
      (libsource (lib "eagle-import") (part "rcl_C-EUC0603"))
    )
    (comp (ref "C76")
      (value "22pF")
      (footprint "eagle-import:C0603")
      (libsource (lib "eagle-import") (part "rcl_C-EUC0603"))
    )
    (comp (ref "C77")
      (value "22pF")
      (footprint "eagle-import:C0603")
      (libsource (lib "eagle-import") (part "rcl_C-EUC0603"))
    )
    (comp (ref "C78")
      (value "100nF")
      (footprint "eagle-import:C0603")
      (libsource (lib "eagle-import") (part "rcl_C-EUC0603"))
    )
    (comp (ref "C79")
      (value "100nF")
      (footprint "eagle-import:C0603")
      (libsource (lib "eagle-import") (part "rcl_C-EUC0603"))
    )
    (comp (ref "C80")
      (value "100nF")
      (footprint "eagle-import:C0603")
      (libsource (lib "eagle-import") (part "rcl_C-EUC0603"))
    )
    (comp (ref "IC5")
      (value "AT90USB162A")
      (footprint "eagle-import:TQFP32-08")
      (libsource (lib "eagle-import") (part "AT90USB162A"))
    )
    (comp (ref "R39")
      (value "27R")
      (footprint "eagle-import:R0603")
      (libsource (lib "eagle-import") (part "resistor_R-US_R0603"))
    )
    (comp (ref "R40")
      (value "27R")
      (footprint "eagle-import:R0603")
      (libsource (lib "eagle-import") (part "resistor_R-US_R0603"))
    )
    (comp (ref "R41")
      (value "470R")
      (footprint "eagle-import:R0603")
      (libsource (lib "eagle-import") (part "resistor_R-US_R0603"))
    )
    (comp (ref "R42")
      (value "470")
      (footprint "eagle-import:R0603")
      (libsource (lib "eagle-import") (part "resistor_R-US_R0603"))
    )
    (comp (ref "R58")
      (value "1K")
      (footprint "eagle-import:R0603")
      (libsource (lib "eagle-import") (part "resistor_R-US_R0603"))
    )
    (comp (ref "R61")
      (value "470R")
      (footprint "eagle-import:R0603")
      (libsource (lib "eagle-import") (part "resistor_R-US_R0603"))
    )
    (comp (ref "SJ1") (value "SJ") (footprint "eagle-import:SJ") (libsource (lib "eagle-import") (part "SJ")))
    (comp (ref "SJ2") (value "SJ") (footprint "eagle-import:SJ") (libsource (lib "eagle-import") (part "SJ")))
    (comp (ref "X5")
      (value "PN61729-S")
      (footprint "eagle-import:PN61729-S")
      (libsource (lib "eagle-import") (part "PN61729-S"))
    )
    (comp (ref "XTAL1")
      (value "16MHz")
      (footprint "eagle-import:HC-49U")
      (libsource (lib "eagle-import") (part "OSC-XTAL-HC-49U-SMD"))
    )
    (comp (ref "C1")
      (value "10µ")
      (footprint "eagle-import:C1206")
      (libsource (lib "eagle-import") (part "myrcl_C-EUC1206"))
    )
    (comp (ref "C2")
      (value "2n2")
      (footprint "eagle-import:C0805K")
      (libsource (lib "eagle-import") (part "myrcl_C-EUC0805K"))
    )
    (comp (ref "C3")
      (value "22µ")
      (footprint "eagle-import:C0805K")
      (libsource (lib "eagle-import") (part "myrcl_C-EUC0805K"))
    )
    (comp (ref "C4")
      (value "10µ")
      (footprint "eagle-import:C1206")
      (libsource (lib "eagle-import") (part "myrcl_C-EUC1206"))
    )
    (comp (ref "C5")
      (value "2n2")
      (footprint "eagle-import:C0805K")
      (libsource (lib "eagle-import") (part "myrcl_C-EUC0805K"))
    )
    (comp (ref "C6")
      (value "22µ")
      (footprint "eagle-import:C0805K")
      (libsource (lib "eagle-import") (part "myrcl_C-EUC0805K"))
    )
    (comp (ref "C7")
      (value "10µ")
      (footprint "eagle-import:C1206")
      (libsource (lib "eagle-import") (part "myrcl_C-EUC1206"))
    )
    (comp (ref "C8")
      (value "10µ")
      (footprint "eagle-import:C1206")
      (libsource (lib "eagle-import") (part "myrcl_C-EUC1206"))
    )
    (comp (ref "C9")
      (value "22µ")
      (footprint "eagle-import:C0805K")
      (libsource (lib "eagle-import") (part "myrcl_C-EUC0805K"))
    )
    (comp (ref "C10")
      (value "2n2")
      (footprint "eagle-import:C0805K")
      (libsource (lib "eagle-import") (part "myrcl_C-EUC0805K"))
    )
    (comp (ref "C11")
      (value "22µ")
      (footprint "eagle-import:C0805K")
      (libsource (lib "eagle-import") (part "myrcl_C-EUC0805K"))
    )
    (comp (ref "C14")
      (value "470u")
      (footprint "eagle-import:E2,5-6")
      (libsource (lib "eagle-import") (part "CPOL-EUE2.5-6"))
    )
    (comp (ref "C58")
      (value "100nF")
      (footprint "eagle-import:C0603")
      (libsource (lib "eagle-import") (part "resistor_C-EUC0603"))
    )
    (comp (ref "C60")
      (value "100nF")
      (footprint "eagle-import:C0603")
      (libsource (lib "eagle-import") (part "resistor_C-EUC0603"))
    )
    (comp (ref "C63")
      (value "22µ")
      (footprint "eagle-import:C0805K")
      (libsource (lib "eagle-import") (part "myrcl_C-EUC0805K"))
    )
    (comp (ref "C64")
      (value "10µ")
      (footprint "eagle-import:C1206")
      (libsource (lib "eagle-import") (part "myrcl_C-EUC1206"))
    )
    (comp (ref "C74")
      (value "100nF")
      (footprint "eagle-import:C0603")
      (libsource (lib "eagle-import") (part "resistor_C-EUC0603"))
    )
    (comp (ref "C75")
      (value "100nF")
      (footprint "eagle-import:C0603")
      (libsource (lib "eagle-import") (part "resistor_C-EUC0603"))
    )
    (comp (ref "D1")
      (value "DIODE-MELF-MLL41")
      (footprint "eagle-import:MELF-MLL41")
      (libsource (lib "eagle-import") (part "DIODE-MELF-MLL41"))
    )
    (comp (ref "DC1")
      (value "NMA")
      (footprint "eagle-import:NMA")
      (fields (field (name "MF") "C & D TECHNOLOGIES, INC") (field (name "MPN") "NMA0515SC"))
      (libsource (lib "eagle-import") (part "NMA"))
    )
    (comp (ref "IC1")
      (value "AOZ1021")
      (footprint "eagle-import:AOZ1021")
      (libsource (lib "eagle-import") (part "AOZ1021"))
    )
    (comp (ref "IC2")
      (value "AOZ1021")
      (footprint "eagle-import:AOZ1021")
      (libsource (lib "eagle-import") (part "AOZ1021"))
    )
    (comp (ref "IC3")
      (value "AOZ1094")
      (footprint "eagle-import:AOZ1094.PAC")
      (libsource (lib "eagle-import") (part "AOZ1094"))
    )
    (comp (ref "IC6")
      (value "LM337L")
      (footprint "eagle-import:337L")
      (libsource (lib "eagle-import") (part "LM337L"))
    )
    (comp (ref "IC7")
      (value "LM317L")
      (footprint "eagle-import:317L")
      (libsource (lib "eagle-import") (part "LM317L"))
    )
    (comp (ref "JP6")
      (value "PINHD-1X2")
      (footprint "eagle-import:1X02")
      (libsource (lib "eagle-import") (part "PINHD-1X2"))
    )
    (comp (ref "L1")
      (value "4.7µ")
      (footprint "eagle-import:NR60")
      (libsource (lib "eagle-import") (part "L-EUNR60"))
    )
    (comp (ref "L3")
      (value "2.2uF")
      (footprint "eagle-import:DR1030MOD.PAC")
      (fields (field (name "MPN") "CDRH104RNP-2R5NC"))
      (libsource (lib "eagle-import") (part "DR1030FAKE"))
    )
    (comp (ref "L4")
      (value "4.7µ")
      (footprint "eagle-import:NR60")
      (libsource (lib "eagle-import") (part "L-EUNR60"))
    )
    (comp (ref "R1")
      (value "7K5")
      (footprint "eagle-import:R0805K")
      (libsource (lib "eagle-import") (part "R-EU_R0805K"))
    )
    (comp (ref "R2")
      (value "7K5")
      (footprint "eagle-import:R0805K")
      (libsource (lib "eagle-import") (part "R-EU_R0805K"))
    )
    (comp (ref "R3")
      (value "7K5")
      (footprint "eagle-import:R0805K")
      (libsource (lib "eagle-import") (part "R-EU_R0805K"))
    )
    (comp (ref "R4")
      (value "2K4")
      (footprint "eagle-import:R0805K")
      (libsource (lib "eagle-import") (part "R-EU_R0805K"))
    )
    (comp (ref "R5")
      (value "7K5")
      (footprint "eagle-import:R0805K")
      (libsource (lib "eagle-import") (part "R-EU_R0805K"))
    )
    (comp (ref "R6")
      (value "7K5")
      (footprint "eagle-import:R0805K")
      (libsource (lib "eagle-import") (part "R-EU_R0805K"))
    )
    (comp (ref "R7")
      (value "5K36")
      (footprint "eagle-import:R0805K")
      (libsource (lib "eagle-import") (part "R-EU_R0805K"))
    )
    (comp (ref "R8")
      (value "2K4")
      (footprint "eagle-import:R0805K")
      (libsource (lib "eagle-import") (part "R-EU_R0805K"))
    )
    (comp (ref "R9")
      (value "24k9,1%")
      (footprint "eagle-import:R0805K")
      (libsource (lib "eagle-import") (part "R-EU_R0805K"))
    )
    (comp (ref "R10")
      (value "1K2")
      (footprint "eagle-import:R0805K")
      (libsource (lib "eagle-import") (part "R-EU_R0805K"))
    )
    (comp (ref "R11")
      (value "2K4")
      (footprint "eagle-import:R0805K")
      (libsource (lib "eagle-import") (part "R-EU_R0805K"))
    )
    (comp (ref "R12")
      (value "7K5")
      (footprint "eagle-import:R0805K")
      (libsource (lib "eagle-import") (part "R-EU_R0805K"))
    )
    (comp (ref "R48")
      (value "200R,1%")
      (footprint "eagle-import:R0603")
      (libsource (lib "eagle-import") (part "resistor_R-US_R0603"))
    )
    (comp (ref "R49")
      (value "1k,1%")
      (footprint "eagle-import:R0603")
      (libsource (lib "eagle-import") (part "resistor_R-US_R0603"))
    )
    (comp (ref "R50")
      (value "200R,1%")
      (footprint "eagle-import:R0603")
      (libsource (lib "eagle-import") (part "resistor_R-US_R0603"))
    )
    (comp (ref "R51")
      (value "1k,1%")
      (footprint "eagle-import:R0603")
      (libsource (lib "eagle-import") (part "resistor_R-US_R0603"))
    )
    (comp (ref "TP1")
      (value "TPSQPAD1-13")
      (footprint "eagle-import:P1-13")
      (libsource (lib "eagle-import") (part "TPSQPAD1-13"))
    )
    (comp (ref "TP2")
      (value "TPSQPAD1-13")
      (footprint "eagle-import:P1-13")
      (libsource (lib "eagle-import") (part "TPSQPAD1-13"))
    )
    (comp (ref "TP3")
      (value "PTR1PAD1-13")
      (footprint "eagle-import:P1-13")
      (libsource (lib "eagle-import") (part "PTR1PAD1-13"))
    )
    (comp (ref "TP4")
      (value "PTR1PAD1-13")
      (footprint "eagle-import:P1-13")
      (libsource (lib "eagle-import") (part "PTR1PAD1-13"))
    )
    (comp (ref "TP5")
      (value "PTR1PAD1-13")
      (footprint "eagle-import:P1-13")
      (libsource (lib "eagle-import") (part "PTR1PAD1-13"))
    )
    (comp (ref "TP6")
      (value "PTR1PAD1-13")
      (footprint "eagle-import:P1-13")
      (libsource (lib "eagle-import") (part "PTR1PAD1-13"))
    )
    (comp (ref "TP7")
      (value "PTR1PAD1-13")
      (footprint "eagle-import:P1-13")
      (libsource (lib "eagle-import") (part "PTR1PAD1-13"))
    )
    (comp (ref "TP8")
      (value "PTR1PAD1-13")
      (footprint "eagle-import:P1-13")
      (libsource (lib "eagle-import") (part "PTR1PAD1-13"))
    )
    (comp (ref "TP9")
      (value "PTR1PAD1-13")
      (footprint "eagle-import:P1-13")
      (libsource (lib "eagle-import") (part "PTR1PAD1-13"))
    )
    (comp (ref "CHANNEL1")
      (value "OPENADC")
      (footprint "eagle-import:OPENADCREV1")
      (libsource (lib "eagle-import") (part "OPENADC"))
    )
    (comp (ref "CHANNEL2")
      (value "OPENADC")
      (footprint "eagle-import:OPENADCREV1")
      (libsource (lib "eagle-import") (part "OPENADC"))
    )
    (comp (ref "LED1")
      (value "GREEN")
      (footprint "eagle-import:LED-805")
      (libsource (lib "eagle-import") (part "LED-0805"))
    )
    (comp (ref "LED2")
      (value "GREEN")
      (footprint "eagle-import:LED-805")
      (libsource (lib "eagle-import") (part "LED-0805"))
    )
    (comp (ref "LED3")
      (value "BLUE")
      (footprint "eagle-import:LED-805")
      (libsource (lib "eagle-import") (part "LED-0805"))
    )
    (comp (ref "LED4")
      (value "YELLOW")
      (footprint "eagle-import:LED-805")
      (libsource (lib "eagle-import") (part "LED-0805"))
    )
    (comp (ref "LED5")
      (value "YELLOW")
      (footprint "eagle-import:LED-805")
      (libsource (lib "eagle-import") (part "LED-0805"))
    )
    (comp (ref "LED6")
      (value "YELLOW")
      (footprint "eagle-import:LED-805")
      (libsource (lib "eagle-import") (part "LED-0805"))
    )
    (comp (ref "LED7")
      (value "GREEN")
      (footprint "eagle-import:LED-805")
      (libsource (lib "eagle-import") (part "LED-0805"))
    )
    (comp (ref "LED8")
      (value "GREEN")
      (footprint "eagle-import:LED-805")
      (libsource (lib "eagle-import") (part "LED-0805"))
    )
    (comp (ref "LED9")
      (value "BLUE")
      (footprint "eagle-import:LED-805")
      (libsource (lib "eagle-import") (part "LED-0805"))
    )
    (comp (ref "LED10")
      (value "YELLOW")
      (footprint "eagle-import:LED-805")
      (libsource (lib "eagle-import") (part "LED-0805"))
    )
    (comp (ref "LED11")
      (value "YELLOW")
      (footprint "eagle-import:LED-805")
      (libsource (lib "eagle-import") (part "LED-0805"))
    )
    (comp (ref "LED12")
      (value "YELLOW")
      (footprint "eagle-import:LED-805")
      (libsource (lib "eagle-import") (part "LED-0805"))
    )
    (comp (ref "R37")
      (value "220R")
      (footprint "eagle-import:R0603")
      (libsource (lib "eagle-import") (part "resistor_R-US_R0603"))
    )
    (comp (ref "R52")
      (value "220R")
      (footprint "eagle-import:R0603")
      (libsource (lib "eagle-import") (part "resistor_R-US_R0603"))
    )
    (comp (ref "R53")
      (value "220R")
      (footprint "eagle-import:R0603")
      (libsource (lib "eagle-import") (part "resistor_R-US_R0603"))
    )
    (comp (ref "R54")
      (value "220R")
      (footprint "eagle-import:R0603")
      (libsource (lib "eagle-import") (part "resistor_R-US_R0603"))
    )
    (comp (ref "R55")
      (value "220R")
      (footprint "eagle-import:R0603")
      (libsource (lib "eagle-import") (part "resistor_R-US_R0603"))
    )
    (comp (ref "R56")
      (value "220R")
      (footprint "eagle-import:R0603")
      (libsource (lib "eagle-import") (part "resistor_R-US_R0603"))
    )
    (comp (ref "R57")
      (value "220R")
      (footprint "eagle-import:R0603")
      (libsource (lib "eagle-import") (part "resistor_R-US_R0603"))
    )
    (comp (ref "C62")
      (value "100nF")
      (footprint "eagle-import:C0603")
      (libsource (lib "eagle-import") (part "C-EUC0603"))
    )
    (comp (ref "D3")
      (value "BAV99-7-F")
      (footprint "eagle-import:SOT-23")
      (libsource (lib "eagle-import") (part "D_ACACSOT23"))
    )
    (comp (ref "FID1")
      (value "FIDUCIAL")
      (footprint "eagle-import:FIDUCIAL_1MM")
      (libsource (lib "eagle-import") (part "FIDUCIAL"))
    )
    (comp (ref "FID2")
      (value "FIDUCIAL")
      (footprint "eagle-import:FIDUCIAL_1MM")
      (libsource (lib "eagle-import") (part "FIDUCIAL"))
    )
    (comp (ref "FID3")
      (value "FIDUCIAL")
      (footprint "eagle-import:FIDUCIAL_1MM")
      (libsource (lib "eagle-import") (part "FIDUCIAL"))
    )
    (comp (ref "FID4")
      (value "FIDUCIAL")
      (footprint "eagle-import:FIDUCIAL_1MM")
      (libsource (lib "eagle-import") (part "FIDUCIAL"))
    )
    (comp (ref "FID5")
      (value "FIDUCIAL")
      (footprint "eagle-import:FIDUCIAL_1MM")
      (libsource (lib "eagle-import") (part "FIDUCIAL"))
    )
    (comp (ref "FID6")
      (value "FIDUCIAL")
      (footprint "eagle-import:FIDUCIAL_1MM")
      (libsource (lib "eagle-import") (part "FIDUCIAL"))
    )
    (comp (ref "H1")
      (value "MOUNT-PAD-ROUND2.8")
      (footprint "eagle-import:2,8-PAD")
      (libsource (lib "eagle-import") (part "MOUNT-PAD-ROUND2.8"))
    )
    (comp (ref "R31")
      (value "100R")
      (footprint "eagle-import:R0805")
      (libsource (lib "eagle-import") (part "R-US_R0805"))
    )
    (comp (ref "R34")
      (value "R-US_R0805")
      (footprint "eagle-import:R0805")
      (libsource (lib "eagle-import") (part "R-US_R0805"))
    )
    (comp (ref "R47")
      (value "R-US_R0805")
      (footprint "eagle-import:R0805")
      (libsource (lib "eagle-import") (part "R-US_R0805"))
    )
    (comp (ref "X4")
      (value "SMA-142-0711-821/826")
      (footprint "eagle-import:J502-ND-142-0711-821_826")
      (fields (field (name "MF") "JOHNSON COMPONENTS") (field (name "MPN") "142-0711-821"))
      (libsource (lib "eagle-import") (part "SMA-142-0711-821/826"))
    )
    (comp (ref "C13")
      (value "100nF")
      (footprint "eagle-import:C0603")
      (libsource (lib "eagle-import") (part "rcl_C-EUC0603"))
    )
    (comp (ref "C47")
      (value "100nF")
      (footprint "eagle-import:C0603")
      (libsource (lib "eagle-import") (part "rcl_C-EUC0603"))
    )
    (comp (ref "C48")
      (value "100nF")
      (footprint "eagle-import:C0603")
      (libsource (lib "eagle-import") (part "rcl_C-EUC0603"))
    )
    (comp (ref "C49")
      (value "100nF")
      (footprint "eagle-import:C0603")
      (libsource (lib "eagle-import") (part "rcl_C-EUC0603"))
    )
    (comp (ref "C65")
      (value "100nF")
      (footprint "eagle-import:C0603")
      (libsource (lib "eagle-import") (part "rcl_C-EUC0603"))
    )
    (comp (ref "C66")
      (value "100nF")
      (footprint "eagle-import:C0603")
      (libsource (lib "eagle-import") (part "rcl_C-EUC0603"))
    )
    (comp (ref "C67")
      (value "1uF")
      (footprint "eagle-import:C0603")
      (libsource (lib "eagle-import") (part "rcl_C-EUC0603"))
    )
    (comp (ref "C68")
      (value "22nF")
      (footprint "eagle-import:C0603")
      (libsource (lib "eagle-import") (part "rcl_C-EUC0603"))
    )
    (comp (ref "C69")
      (value "22nF")
      (footprint "eagle-import:C0603")
      (libsource (lib "eagle-import") (part "rcl_C-EUC0603"))
    )
    (comp (ref "C70")
      (value "100nF")
      (footprint "eagle-import:C0603")
      (libsource (lib "eagle-import") (part "rcl_C-EUC0603"))
    )
    (comp (ref "C71")
      (value "1uF")
      (footprint "eagle-import:C0603")
      (libsource (lib "eagle-import") (part "rcl_C-EUC0603"))
    )
    (comp (ref "C72")
      (value "100nF")
      (footprint "eagle-import:C0603")
      (libsource (lib "eagle-import") (part "rcl_C-EUC0603"))
    )
    (comp (ref "C81")
      (value "22nF")
      (footprint "eagle-import:C0603")
      (libsource (lib "eagle-import") (part "rcl_C-EUC0603"))
    )
    (comp (ref "C82")
      (value "22nF")
      (footprint "eagle-import:C0603")
      (libsource (lib "eagle-import") (part "rcl_C-EUC0603"))
    )
    (comp (ref "C83")
      (value "22nF")
      (footprint "eagle-import:C0603")
      (libsource (lib "eagle-import") (part "rcl_C-EUC0603"))
    )
    (comp (ref "C88")
      (value "100nF")
      (footprint "eagle-import:C0603")
      (libsource (lib "eagle-import") (part "rcl_C-EUC0603"))
    )
    (comp (ref "C89")
      (value "100nF")
      (footprint "eagle-import:C0603")
      (libsource (lib "eagle-import") (part "rcl_C-EUC0603"))
    )
    (comp (ref "C90")
      (value "100nF")
      (footprint "eagle-import:C0603")
      (libsource (lib "eagle-import") (part "rcl_C-EUC0603"))
    )
    (comp (ref "C92")
      (value "100nF")
      (footprint "eagle-import:C0603")
      (libsource (lib "eagle-import") (part "rcl_C-EUC0603"))
    )
    (comp (ref "IC4")
      (value "GTL2003")
      (footprint "eagle-import:TSSOP20")
      (libsource (lib "eagle-import") (part "GTL2003"))
    )
    (comp (ref "JP2")
      (value "EXP-MINI")
      (footprint "eagle-import:2X03_90")
      (libsource (lib "eagle-import") (part "PINHD-2X3/90"))
    )
    (comp (ref "JP7")
      (value "PINHD-1X3")
      (footprint "eagle-import:1X03")
      (libsource (lib "eagle-import") (part "PINHD-1X3"))
    )
    (comp (ref "JP8")
      (value "PINHD-1X2")
      (footprint "eagle-import:1X02")
      (libsource (lib "eagle-import") (part "PINHD-1X2"))
    )
    (comp (ref "JP9")
      (value "PLL_INPUT")
      (footprint "eagle-import:2X04_90")
      (libsource (lib "eagle-import") (part "PINHD-2X4/90"))
    )
    (comp (ref "JP10")
      (value "PINHD-1X2")
      (footprint "eagle-import:1X02")
      (libsource (lib "eagle-import") (part "PINHD-1X2"))
    )
    (comp (ref "JP11")
      (value "PINHD-1X2")
      (footprint "eagle-import:1X02")
      (libsource (lib "eagle-import") (part "PINHD-1X2"))
    )
    (comp (ref "JP13")
      (value "TARGET")
      (footprint "eagle-import:2X10_90")
      (libsource (lib "eagle-import") (part "PINHD-2X10/90"))
    )
    (comp (ref "R32")
      (value "100R")
      (footprint "eagle-import:R0603")
      (libsource (lib "eagle-import") (part "resistor_R-US_R0603"))
    )
    (comp (ref "R33")
      (value "100R")
      (footprint "eagle-import:R0603")
      (libsource (lib "eagle-import") (part "resistor_R-US_R0603"))
    )
    (comp (ref "R38")
      (value "100k")
      (footprint "eagle-import:R0603")
      (libsource (lib "eagle-import") (part "resistor_R-US_R0603"))
    )
    (comp (ref "R43")
      (value "1k,1%")
      (footprint "eagle-import:R0603")
      (libsource (lib "eagle-import") (part "resistor_R-US_R0603"))
    )
    (comp (ref "R44")
      (value "1k,1%")
      (footprint "eagle-import:R0603")
      (libsource (lib "eagle-import") (part "resistor_R-US_R0603"))
    )
    (comp (ref "R45")
      (value "1k,1%")
      (footprint "eagle-import:R0603")
      (libsource (lib "eagle-import") (part "resistor_R-US_R0603"))
    )
    (comp (ref "R46")
      (value "1k,1%")
      (footprint "eagle-import:R0603")
      (libsource (lib "eagle-import") (part "resistor_R-US_R0603"))
    )
    (comp (ref "R59")
      (value "4k7")
      (footprint "eagle-import:R0603")
      (libsource (lib "eagle-import") (part "resistor_R-US_R0603"))
    )
    (comp (ref "R60")
      (value "4k7")
      (footprint "eagle-import:R0603")
      (libsource (lib "eagle-import") (part "resistor_R-US_R0603"))
    )
    (comp (ref "U5")
      (value "CDCE906PW")
      (footprint "eagle-import:SOP65P640X120-20N")
      (libsource (lib "eagle-import") (part "CDCE906PW"))
    )
    (comp (ref "U6")
      (value "TXS0104EPWR")
      (footprint "eagle-import:SOP65P640X120-14N")
      (fields (field (name "MPN") "TXB0104PWR"))
      (libsource (lib "eagle-import") (part "TXB0104PWR"))
    )
    (comp (ref "U8")
      (value "SN74LVC1T45DBVT")
      (footprint "eagle-import:SOT95P280X145-6N")
      (libsource (lib "eagle-import") (part "SN74LVC1T45DBVT"))
    )
    (comp (ref "U9")
      (value "SN74LVC1T45DBVT")
      (footprint "eagle-import:SOT95P280X145-6N")
      (libsource (lib "eagle-import") (part "SN74LVC1T45DBVT"))
    )
    (comp (ref "X3")
      (value "SMA-142-0711-821/826")
      (footprint "eagle-import:J502-ND-142-0711-821_826")
      (fields (field (name "MF") "JOHNSON COMPONENTS") (field (name "MPN") "142-0711-821"))
      (libsource (lib "eagle-import") (part "SMA-142-0711-821/826"))
    )
    (comp (ref "C91")
      (value "C-EUC0603")
      (footprint "eagle-import:C0603")
      (libsource (lib "eagle-import") (part "resistor_C-EUC0603"))
    )
    (comp (ref "JP5")
      (value "PINHD-2X15/90")
      (footprint "eagle-import:2X15_90")
      (libsource (lib "eagle-import") (part "PINHD-2X15/90"))
    )
    (comp (ref "R35")
      (value "2k2")
      (footprint "eagle-import:R0603")
      (libsource (lib "eagle-import") (part "resistor_R-US_R0603"))
    )
    (comp (ref "R36")
      (value "2k2")
      (footprint "eagle-import:R0603")
      (libsource (lib "eagle-import") (part "resistor_R-US_R0603"))
    )
    (comp (ref "U10")
      (value "ATSHA204-SH")
      (footprint "eagle-import:SO08")
      (libsource (lib "eagle-import") (part "ATSHA204-SH"))
    )
  )
  (nets
    (net (code "2") (name "+1.2V") (class "Default")
      (node (ref "C11") (pin "2") (pinfunction "2_2") (pintype "passive"))
      (node (ref "C14") (pin "+") (pinfunction "+_+") (pintype "passive"))
      (node (ref "C9") (pin "2") (pinfunction "2_2") (pintype "passive"))
      (node (ref "CON6") (pin "A11") (pinfunction "A11~{1.2V}_A11") (pintype "bidirectional"))
      (node (ref "CON6") (pin "A23") (pinfunction "A23~{1.2V}_A23") (pintype "bidirectional"))
      (node (ref "CON6") (pin "B11") (pinfunction "B11~{1.2V}_B11") (pintype "bidirectional"))
      (node (ref "CON6") (pin "B23") (pinfunction "B23~{1.2V}_B23") (pintype "bidirectional"))
      (node (ref "CON6") (pin "C19") (pinfunction "C19~{1.2V}_C19") (pintype "bidirectional"))
      (node (ref "CON6") (pin "C28") (pinfunction "C28~{1.2V}_C28") (pintype "bidirectional"))
      (node (ref "CON6") (pin "D28") (pinfunction "D28~{1.2V}_D28") (pintype "bidirectional"))
      (node (ref "CON6") (pin "E10") (pinfunction "E10~{1.2V}_E10") (pintype "bidirectional"))
      (node (ref "CON6") (pin "E11") (pinfunction "E11~{1.2V}_E11") (pintype "bidirectional"))
      (node (ref "L3") (pin "2") (pinfunction "2_2") (pintype "passive"))
      (node (ref "R10") (pin "2") (pinfunction "2_2") (pintype "passive"))
      (node (ref "TP4") (pin "TP") (pinfunction "TP_TP") (pintype "input"))
    )
    (net (code "3") (name "+2.6V") (class "Default")
      (node (ref "C6") (pin "2") (pinfunction "2_2") (pintype "passive"))
      (node (ref "CON3") (pin "2") (pinfunction "VIO_2") (pintype "bidirectional"))
      (node (ref "CON6") (pin "A10") (pinfunction "A10~{2.5V}_A10") (pintype "bidirectional"))
      (node (ref "CON6") (pin "B10") (pinfunction "B10~{2.5V}_B10") (pintype "bidirectional"))
      (node (ref "CON6") (pin "C18") (pinfunction "C18~{2.5V}_C18") (pintype "bidirectional"))
      (node (ref "CON6") (pin "C29") (pinfunction "C29~{2.5V}_C29") (pintype "bidirectional"))
      (node (ref "CON6") (pin "D18") (pinfunction "D18~{2.5V}_D18") (pintype "bidirectional"))
      (node (ref "L4") (pin "P$2") (pinfunction "2_P$2") (pintype "passive"))
      (node (ref "R7") (pin "2") (pinfunction "2_2") (pintype "passive"))
      (node (ref "TP5") (pin "TP") (pinfunction "TP_TP") (pintype "input"))
    )
    (net (code "4") (name "+3V3") (class "Default")
      (node (ref "C28") (pin "1") (pinfunction "1_1") (pintype "passive"))
      (node (ref "C29") (pin "1") (pinfunction "1_1") (pintype "passive"))
      (node (ref "C3") (pin "2") (pinfunction "2_2") (pintype "passive"))
      (node (ref "C62") (pin "1") (pinfunction "1_1") (pintype "passive"))
      (node (ref "C65") (pin "1") (pinfunction "1_1") (pintype "passive"))
      (node (ref "C81") (pin "1") (pinfunction "1_1") (pintype "passive"))
      (node (ref "C82") (pin "1") (pinfunction "1_1") (pintype "passive"))
      (node (ref "C83") (pin "1") (pinfunction "1_1") (pintype "passive"))
      (node (ref "C91") (pin "1") (pinfunction "1_1") (pintype "passive"))
      (node (ref "CHANNEL1") (pin "11") (pinfunction "DVCC_11") (pintype "bidirectional"))
      (node (ref "CHANNEL1") (pin "12") (pinfunction "DVCC_12") (pintype "bidirectional"))
      (node (ref "CHANNEL1") (pin "29") (pinfunction "AVCC_29") (pintype "bidirectional"))
      (node (ref "CHANNEL1") (pin "30") (pinfunction "AVCC_30") (pintype "bidirectional"))
      (node (ref "CHANNEL2") (pin "11") (pinfunction "DVCC_11") (pintype "bidirectional"))
      (node (ref "CHANNEL2") (pin "12") (pinfunction "DVCC_12") (pintype "bidirectional"))
      (node (ref "CHANNEL2") (pin "29") (pinfunction "AVCC_29") (pintype "bidirectional"))
      (node (ref "CHANNEL2") (pin "30") (pinfunction "AVCC_30") (pintype "bidirectional"))
      (node (ref "CON6") (pin "A16") (pinfunction "A16~{3.3V}_A16") (pintype "bidirectional"))
      (node (ref "CON6") (pin "A22") (pinfunction "A22~{VCCO_IO}_A22") (pintype "bidirectional"))
      (node (ref "CON6") (pin "A31") (pinfunction "A31~{VCCO_IO}_A31") (pintype "bidirectional"))
      (node (ref "CON6") (pin "A7") (pinfunction "A7~{3.3V}_A7") (pintype "bidirectional"))
      (node (ref "CON6") (pin "B16") (pinfunction "B16~{3.3V}_B16") (pintype "bidirectional"))
      (node (ref "CON6") (pin "B22") (pinfunction "B22~{VCCO_IO}_B22") (pintype "bidirectional"))
      (node (ref "CON6") (pin "B31") (pinfunction "B31~{VCCO_IO}_B31") (pintype "bidirectional"))
      (node (ref "CON6") (pin "B7") (pinfunction "B7~{3.3V}_B7") (pintype "bidirectional"))
      (node (ref "CON6") (pin "C27") (pinfunction "C27~{VCCO_TOP}_C27") (pintype "bidirectional"))
      (node (ref "CON6") (pin "C6") (pinfunction "C6~{3.3V}_C6") (pintype "bidirectional"))
      (node (ref "CON6") (pin "C7") (pinfunction "C7~{VCCO_TOP}_C7") (pintype "bidirectional"))
      (node (ref "CON6") (pin "D27") (pinfunction "D27~{VCCO_TOP}_D27") (pintype "bidirectional"))
      (node (ref "CON6") (pin "D6") (pinfunction "D6~{3.3V}_D6") (pintype "bidirectional"))
      (node (ref "CON6") (pin "D7") (pinfunction "D7~{VCCO_TOP}_D7") (pintype "bidirectional"))
      (node (ref "CON6") (pin "E29") (pinfunction "E29~{3.3V}_E29") (pintype "bidirectional"))
      (node (ref "CON6") (pin "E30") (pinfunction "E30~{3.3V}_E30") (pintype "bidirectional"))
      (node (ref "D3") (pin "2") (pinfunction "C_2") (pintype "passive"))
      (node (ref "JP11") (pin "2") (pinfunction "2_2") (pintype "passive"))
      (node (ref "JP13") (pin "18") (pinfunction "18_18") (pintype "passive"))
      (node (ref "JP13") (pin "3") (pinfunction "3_3") (pintype "passive"))
      (node (ref "JP2") (pin "4") (pinfunction "4_4") (pintype "passive"))
      (node (ref "JP5") (pin "3") (pinfunction "3_3") (pintype "passive"))
      (node (ref "JP9") (pin "2") (pinfunction "2_2") (pintype "passive"))
      (node (ref "JP9") (pin "7") (pinfunction "7_7") (pintype "passive"))
      (node (ref "L1") (pin "P$2") (pinfunction "2_P$2") (pintype "passive"))
      (node (ref "L5") (pin "1") (pinfunction "1_1") (pintype "passive"))
      (node (ref "L9") (pin "2") (pinfunction "2_2") (pintype "passive"))
      (node (ref "R3") (pin "2") (pinfunction "2_2") (pintype "passive"))
      (node (ref "R35") (pin "1") (pinfunction "1_1") (pintype "passive"))
      (node (ref "R36") (pin "1") (pinfunction "1_1") (pintype "passive"))
      (node (ref "R37") (pin "2") (pinfunction "2_2") (pintype "passive"))
      (node (ref "TP6") (pin "TP") (pinfunction "TP_TP") (pintype "input"))
      (node (ref "U1") (pin "24") (pinfunction "DRVDD_24") (pintype "bidirectional"))
      (node (ref "U10") (pin "8") (pinfunction "VCC_8") (pintype "bidirectional"))
      (node (ref "U6") (pin "1") (pinfunction "VCCA_1") (pintype "power_in"))
      (node (ref "U6") (pin "8") (pinfunction "OE_8") (pintype "input"))
      (node (ref "U8") (pin "1") (pinfunction "VCCA_1") (pintype "power_in"))
      (node (ref "U9") (pin "1") (pinfunction "VCCA_1") (pintype "power_in"))
    )
    (net (code "5") (name "+5V") (class "Default")
      (node (ref "C1") (pin "2") (pinfunction "2_2") (pintype "passive"))
      (node (ref "C4") (pin "2") (pinfunction "2_2") (pintype "passive"))
      (node (ref "C63") (pin "2") (pinfunction "2_2") (pintype "passive"))
      (node (ref "C64") (pin "2") (pinfunction "2_2") (pintype "passive"))
      (node (ref "C7") (pin "2") (pinfunction "2_2") (pintype "passive"))
      (node (ref "C8") (pin "2") (pinfunction "2_2") (pintype "passive"))
      (node (ref "CON6") (pin "A1") (pinfunction "A1~{4..35V}_A1") (pintype "bidirectional"))
      (node (ref "CON6") (pin "B1") (pinfunction "B1~{4..35V}_B1") (pintype "bidirectional"))
      (node (ref "DC1") (pin "1") (pinfunction "+VIN_1") (pintype "passive"))
      (node (ref "IC1") (pin "VIN") (pinfunction "VIN_VIN") (pintype "bidirectional"))
      (node (ref "IC2") (pin "VIN") (pinfunction "VIN_VIN") (pintype "bidirectional"))
      (node (ref "IC3") (pin "VIN") (pinfunction "VIN_VIN") (pintype "bidirectional"))
      (node (ref "JP1") (pin "1") (pinfunction "1_1") (pintype "passive"))
      (node (ref "JP13") (pin "1") (pinfunction "1_1") (pintype "passive"))
      (node (ref "JP13") (pin "20") (pinfunction "20_20") (pintype "passive"))
      (node (ref "JP5") (pin "1") (pinfunction "1_1") (pintype "passive"))
      (node (ref "JP6") (pin "2") (pinfunction "2_2") (pintype "passive"))
      (node (ref "JP9") (pin "1") (pinfunction "1_1") (pintype "passive"))
      (node (ref "JP9") (pin "8") (pinfunction "8_8") (pintype "passive"))
      (node (ref "R1") (pin "2") (pinfunction "2_2") (pintype "passive"))
      (node (ref "R12") (pin "2") (pinfunction "2_2") (pintype "passive"))
      (node (ref "R5") (pin "2") (pinfunction "2_2") (pintype "passive"))
      (node (ref "TP3") (pin "TP") (pinfunction "TP_TP") (pintype "input"))
    )
    (net (code "6") (name "+5V{slash}2") (class "Default")
      (node (ref "C66") (pin "1") (pinfunction "1_1") (pintype "passive"))
      (node (ref "C78") (pin "1") (pinfunction "1_1") (pintype "passive"))
      (node (ref "C79") (pin "1") (pinfunction "1_1") (pintype "passive"))
      (node (ref "C80") (pin "1") (pinfunction "1_1") (pintype "passive"))
      (node (ref "IC5") (pin "31") (pinfunction "UVCC_31") (pintype "bidirectional"))
      (node (ref "IC5") (pin "32") (pinfunction "AVCC_32") (pintype "bidirectional"))
      (node (ref "IC5") (pin "4") (pinfunction "VCC_4") (pintype "bidirectional"))
      (node (ref "JP6") (pin "1") (pinfunction "1_1") (pintype "passive"))
      (node (ref "R38") (pin "1") (pinfunction "1_1") (pintype "passive"))
      (node (ref "R58") (pin "1") (pinfunction "1_1") (pintype "passive"))
      (node (ref "R61") (pin "2") (pinfunction "2_2") (pintype "passive"))
      (node (ref "X5") (pin "1") (pinfunction "1_1") (pintype "passive"))
    )
    (net (code "7") (name "+9V") (class "Default")
      (node (ref "C58") (pin "1") (pinfunction "1_1") (pintype "passive"))
      (node (ref "IC7") (pin "2") (pinfunction "OUT_2") (pintype "passive"))
      (node (ref "JP2") (pin "1") (pinfunction "1_1") (pintype "passive"))
      (node (ref "R48") (pin "2") (pinfunction "2_2") (pintype "passive"))
      (node (ref "TP1") (pin "TP") (pinfunction "TP_TP") (pintype "input"))
    )
    (net (code "8") (name "-9V") (class "Default")
      (node (ref "C60") (pin "1") (pinfunction "1_1") (pintype "passive"))
      (node (ref "IC6") (pin "OUT") (pinfunction "OUT_OUT") (pintype "passive"))
      (node (ref "JP2") (pin "5") (pinfunction "5_5") (pintype "passive"))
      (node (ref "R50") (pin "2") (pinfunction "2_2") (pintype "passive"))
      (node (ref "TP2") (pin "TP") (pinfunction "TP_TP") (pintype "input"))
    )
    (net (code "10") (name "ADC_VCC") (class "Default")
      (node (ref "C31") (pin "1") (pinfunction "1_1") (pintype "passive"))
      (node (ref "C32") (pin "1") (pinfunction "1_1") (pintype "passive"))
      (node (ref "C34") (pin "1") (pinfunction "1_1") (pintype "passive"))
      (node (ref "C35") (pin "1") (pinfunction "1_1") (pintype "passive"))
      (node (ref "C36") (pin "1") (pinfunction "1_1") (pintype "passive"))
      (node (ref "R17") (pin "2") (pinfunction "2_2") (pintype "passive"))
      (node (ref "R19") (pin "1") (pinfunction "1_1") (pintype "passive"))
      (node (ref "R24") (pin "2") (pinfunction "2_2") (pintype "passive"))
      (node (ref "U1") (pin "12") (pinfunction "AVDD_12") (pintype "bidirectional"))
      (node (ref "U1") (pin "7") (pinfunction "AVDD_7") (pintype "bidirectional"))
      (node (ref "U3") (pin "5") (pinfunction "OUT_5") (pintype "passive"))
    )
    (net (code "11") (name "AVCC") (class "Default")
      (node (ref "C13") (pin "1") (pinfunction "1_1") (pintype "passive"))
      (node (ref "C47") (pin "1") (pinfunction "1_1") (pintype "passive"))
      (node (ref "C48") (pin "1") (pinfunction "1_1") (pintype "passive"))
      (node (ref "C49") (pin "1") (pinfunction "1_1") (pintype "passive"))
      (node (ref "C67") (pin "1") (pinfunction "1_1") (pintype "passive"))
      (node (ref "JP11") (pin "1") (pinfunction "1_1") (pintype "passive"))
      (node (ref "R43") (pin "2") (pinfunction "2_2") (pintype "passive"))
      (node (ref "R44") (pin "2") (pinfunction "2_2") (pintype "passive"))
      (node (ref "R59") (pin "1") (pinfunction "1_1") (pintype "passive"))
      (node (ref "R60") (pin "1") (pinfunction "1_1") (pintype "passive"))
      (node (ref "U5") (pin "14") (pinfunction "VCCOUT1_14") (pintype "output"))
      (node (ref "U5") (pin "18") (pinfunction "VCCOUT2_18") (pintype "output"))
      (node (ref "U5") (pin "3") (pinfunction "VCC_2_3") (pintype "power_in"))
      (node (ref "U5") (pin "7") (pinfunction "VCC_7") (pintype "power_in"))
    )
    (net (code "12") (name "CLK_PLL0") (class "Default")
      (node (ref "CON6") (pin "D23") (pinfunction "D23~{AA10}IO_L32P_GCLK29_2_D23") (pintype "bidirectional"))
      (node (ref "JP8") (pin "1") (pinfunction "1_1") (pintype "passive"))
      (node (ref "U5") (pin "11") (pinfunction "Y0_11") (pintype "output"))
    )
    (net (code "13") (name "CLK_PLL1") (class "Default")
      (node (ref "CON6") (pin "C23") (pinfunction "C23~{AB10}IO_L32N_GCLK28_2_C23") (pintype "bidirectional"))
      (node (ref "JP8") (pin "2") (pinfunction "2_2") (pintype "passive"))
      (node (ref "U5") (pin "12") (pinfunction "Y1_12") (pintype "output"))
    )
    (net (code "14") (name "EXPIO5") (class "Default")
      (node (ref "CON6") (pin "A27") (pinfunction "A27~{C8}IO_L7N_0_A27") (pintype "bidirectional"))
      (node (ref "JP5") (pin "5") (pinfunction "5_5") (pintype "passive"))
    )
    (net (code "15") (name "EXPIO6") (class "Default")
      (node (ref "CON6") (pin "B26") (pinfunction "B26~{B8}IO_L6P_0_B26") (pintype "bidirectional"))
      (node (ref "JP5") (pin "6") (pinfunction "6_6") (pintype "passive"))
    )
    (net (code "16") (name "EXPIO7") (class "Default")
      (node (ref "CON6") (pin "A26") (pinfunction "A26~{A8}IO_L6N_0_A26") (pintype "bidirectional"))
      (node (ref "JP5") (pin "7") (pinfunction "7_7") (pintype "passive"))
    )
    (net (code "17") (name "EXPIO8") (class "Default")
      (node (ref "CON6") (pin "A25") (pinfunction "A25~{D8}IO_L32N_0_A25") (pintype "bidirectional"))
      (node (ref "JP5") (pin "8") (pinfunction "8_8") (pintype "passive"))
    )
    (net (code "18") (name "EXPIO9") (class "Default")
      (node (ref "CON6") (pin "B25") (pinfunction "B25~{D9}IO_L32P_0_B25") (pintype "bidirectional"))
      (node (ref "JP5") (pin "9") (pinfunction "9_9") (pintype "passive"))
    )
    (net (code "19") (name "EXPIO10") (class "Default")
      (node (ref "CON6") (pin "E25") (pinfunction "E25~{C7}IO_L5P_0_E25") (pintype "bidirectional"))
      (node (ref "JP5") (pin "10") (pinfunction "10_10") (pintype "passive"))
    )
    (net (code "20") (name "EXPIO11") (class "Default")
      (node (ref "CON6") (pin "A24") (pinfunction "A24~{C10}IO_L33N_0_A24") (pintype "bidirectional"))
      (node (ref "JP5") (pin "11") (pinfunction "11_11") (pintype "passive"))
    )
    (net (code "21") (name "EXPIO12") (class "Default")
      (node (ref "CON6") (pin "B24") (pinfunction "B24~{D10}IO_L33P_0_B24") (pintype "bidirectional"))
      (node (ref "JP5") (pin "12") (pinfunction "12_12") (pintype "passive"))
    )
    (net (code "22") (name "EXPIO13") (class "Default")
      (node (ref "CON6") (pin "E24") (pinfunction "E24~{C9}IO_L8P_0_E24") (pintype "bidirectional"))
      (node (ref "JP5") (pin "13") (pinfunction "13_13") (pintype "passive"))
    )
    (net (code "23") (name "EXPIO14") (class "Default")
      (node (ref "CON6") (pin "E23") (pinfunction "E23~{B10}IO_L34P_GCLK19_0_E23") (pintype "bidirectional"))
      (node (ref "JP5") (pin "14") (pinfunction "14_14") (pintype "passive"))
    )
    (net (code "24") (name "EXPIO15") (class "Default")
      (node (ref "CON6") (pin "E22") (pinfunction "E22~{A10}IO_L34N_GCLK18_0_E22") (pintype "bidirectional"))
      (node (ref "JP5") (pin "15") (pinfunction "15_15") (pintype "passive"))
    )
    (net (code "25") (name "EXPIO16") (class "Default")
      (node (ref "CON6") (pin "E21") (pinfunction "E21~{D13}IO_L47P_0_NC45_E21") (pintype "bidirectional"))
      (node (ref "JP5") (pin "16") (pinfunction "16_16") (pintype "passive"))
    )
    (net (code "26") (name "EXPIO17") (class "Default")
      (node (ref "CON6") (pin "E20") (pinfunction "E20~{D12}IO_L47N_0_NC45_E20") (pintype "bidirectional"))
      (node (ref "JP5") (pin "17") (pinfunction "17_17") (pintype "passive"))
    )
    (net (code "27") (name "EXPIO18") (class "Default")
      (node (ref "CON6") (pin "B20") (pinfunction "B20~{F10}IO_L38P_0_B20") (pintype "bidirectional"))
      (node (ref "JP5") (pin "18") (pinfunction "18_18") (pintype "passive"))
    )
    (net (code "28") (name "EXPIO19") (class "Default")
      (node (ref "CON6") (pin "A20") (pinfunction "A20~{C15}IO_L62P_0_A20") (pintype "bidirectional"))
      (node (ref "JP5") (pin "19") (pinfunction "19_19") (pintype "passive"))
    )
    (net (code "29") (name "EXPIO20") (class "Default")
      (node (ref "CON6") (pin "E19") (pinfunction "E19~{A14}IO_L50N_0_E19") (pintype "bidirectional"))
      (node (ref "JP5") (pin "20") (pinfunction "20_20") (pintype "passive"))
    )
    (net (code "30") (name "EXPIO21") (class "Default")
      (node (ref "CON6") (pin "B19") (pinfunction "B19~{D11}IO_L37P_GCLK13_0_B19") (pintype "bidirectional"))
      (node (ref "JP5") (pin "21") (pinfunction "21_21") (pintype "passive"))
    )
    (net (code "31") (name "EXPIO22") (class "Default")
      (node (ref "CON6") (pin "A19") (pinfunction "A19~{C12}IO_L37N_GCLK12_0_A19") (pintype "bidirectional"))
      (node (ref "JP5") (pin "22") (pinfunction "22_22") (pintype "passive"))
    )
    (net (code "32") (name "EXPIO23") (class "Default")
      (node (ref "CON6") (pin "A18") (pinfunction "A18~{C13}IO_L48P_0_A18") (pintype "bidirectional"))
      (node (ref "JP5") (pin "23") (pinfunction "23_23") (pintype "passive"))
    )
    (net (code "33") (name "EXPIO24") (class "Default")
      (node (ref "CON6") (pin "B18") (pinfunction "B18~{A13}IO_L48N_0_B18") (pintype "bidirectional"))
      (node (ref "JP5") (pin "24") (pinfunction "24_24") (pintype "passive"))
    )
    (net (code "34") (name "EXPIO25") (class "Default")
      (node (ref "CON6") (pin "E18") (pinfunction "E18~{B14}IO_L50P_0_E18") (pintype "bidirectional"))
      (node (ref "JP5") (pin "25") (pinfunction "25_25") (pintype "passive"))
    )
    (net (code "35") (name "EXPIO26") (class "Default")
      (node (ref "CON6") (pin "B17") (pinfunction "B17~{C11}IO_L35P_GCLK17_0_B17") (pintype "bidirectional"))
      (node (ref "JP5") (pin "26") (pinfunction "26_26") (pintype "passive"))
    )
    (net (code "36") (name "EXPIO27") (class "Default")
      (node (ref "CON6") (pin "A17") (pinfunction "A17~{A11}IO_L35N_GCLK16_0_A17") (pintype "bidirectional"))
      (node (ref "JP5") (pin "27") (pinfunction "27_27") (pintype "passive"))
    )
    (net (code "37") (name "EXPIO28") (class "Default")
      (node (ref "CON6") (pin "E17") (pinfunction "E17~{A12}IO_L36N_GCLK14_0_E17") (pintype "bidirectional"))
      (node (ref "JP5") (pin "28") (pinfunction "28_28") (pintype "passive"))
    )
    (net (code "38") (name "GND") (class "Default")
      (node (ref "C1") (pin "1") (pinfunction "1_1") (pintype "passive"))
      (node (ref "C10") (pin "1") (pinfunction "1_1") (pintype "passive"))
      (node (ref "C11") (pin "1") (pinfunction "1_1") (pintype "passive"))
      (node (ref "C13") (pin "2") (pinfunction "2_2") (pintype "passive"))
      (node (ref "C14") (pin "-") (pinfunction "-_-") (pintype "passive"))
      (node (ref "C18") (pin "2") (pinfunction "2_2") (pintype "passive"))
      (node (ref "C19") (pin "2") (pinfunction "2_2") (pintype "passive"))
      (node (ref "C2") (pin "1") (pinfunction "1_1") (pintype "passive"))
      (node (ref "C20") (pin "2") (pinfunction "2_2") (pintype "passive"))
      (node (ref "C21") (pin "2") (pinfunction "2_2") (pintype "passive"))
      (node (ref "C22") (pin "1") (pinfunction "1_1") (pintype "passive"))
      (node (ref "C24") (pin "2") (pinfunction "2_2") (pintype "passive"))
      (node (ref "C25") (pin "2") (pinfunction "2_2") (pintype "passive"))
      (node (ref "C26") (pin "2") (pinfunction "2_2") (pintype "passive"))
      (node (ref "C27") (pin "2") (pinfunction "2_2") (pintype "passive"))
      (node (ref "C28") (pin "2") (pinfunction "2_2") (pintype "passive"))
      (node (ref "C29") (pin "2") (pinfunction "2_2") (pintype "passive"))
      (node (ref "C3") (pin "1") (pinfunction "1_1") (pintype "passive"))
      (node (ref "C30") (pin "1") (pinfunction "1_1") (pintype "passive"))
      (node (ref "C31") (pin "2") (pinfunction "2_2") (pintype "passive"))
      (node (ref "C32") (pin "2") (pinfunction "2_2") (pintype "passive"))
      (node (ref "C33") (pin "2") (pinfunction "2_2") (pintype "passive"))
      (node (ref "C34") (pin "2") (pinfunction "2_2") (pintype "passive"))
      (node (ref "C35") (pin "2") (pinfunction "2_2") (pintype "passive"))
      (node (ref "C36") (pin "2") (pinfunction "2_2") (pintype "passive"))
      (node (ref "C39") (pin "1") (pinfunction "1_1") (pintype "passive"))
      (node (ref "C4") (pin "1") (pinfunction "1_1") (pintype "passive"))
      (node (ref "C40") (pin "1") (pinfunction "1_1") (pintype "passive"))
      (node (ref "C41") (pin "1") (pinfunction "1_1") (pintype "passive"))
      (node (ref "C42") (pin "1") (pinfunction "1_1") (pintype "passive"))
      (node (ref "C43") (pin "2") (pinfunction "2_2") (pintype "passive"))
      (node (ref "C44") (pin "2") (pinfunction "2_2") (pintype "passive"))
      (node (ref "C45") (pin "2") (pinfunction "2_2") (pintype "passive"))
      (node (ref "C47") (pin "2") (pinfunction "2_2") (pintype "passive"))
      (node (ref "C48") (pin "2") (pinfunction "2_2") (pintype "passive"))
      (node (ref "C49") (pin "2") (pinfunction "2_2") (pintype "passive"))
      (node (ref "C5") (pin "1") (pinfunction "1_1") (pintype "passive"))
      (node (ref "C50") (pin "2") (pinfunction "2_2") (pintype "passive"))
      (node (ref "C51") (pin "2") (pinfunction "2_2") (pintype "passive"))
      (node (ref "C52") (pin "2") (pinfunction "2_2") (pintype "passive"))
      (node (ref "C54") (pin "2") (pinfunction "2_2") (pintype "passive"))
      (node (ref "C55") (pin "2") (pinfunction "2_2") (pintype "passive"))
      (node (ref "C56") (pin "1") (pinfunction "1_1") (pintype "passive"))
      (node (ref "C57") (pin "1") (pinfunction "1_1") (pintype "passive"))
      (node (ref "C58") (pin "2") (pinfunction "2_2") (pintype "passive"))
      (node (ref "C59") (pin "1") (pinfunction "1_1") (pintype "passive"))
      (node (ref "C6") (pin "1") (pinfunction "1_1") (pintype "passive"))
      (node (ref "C60") (pin "2") (pinfunction "2_2") (pintype "passive"))
      (node (ref "C61") (pin "2") (pinfunction "2_2") (pintype "passive"))
      (node (ref "C62") (pin "2") (pinfunction "2_2") (pintype "passive"))
      (node (ref "C63") (pin "1") (pinfunction "1_1") (pintype "passive"))
      (node (ref "C64") (pin "1") (pinfunction "1_1") (pintype "passive"))
      (node (ref "C65") (pin "2") (pinfunction "2_2") (pintype "passive"))
      (node (ref "C66") (pin "2") (pinfunction "2_2") (pintype "passive"))
      (node (ref "C67") (pin "2") (pinfunction "2_2") (pintype "passive"))
      (node (ref "C68") (pin "2") (pinfunction "2_2") (pintype "passive"))
      (node (ref "C69") (pin "2") (pinfunction "2_2") (pintype "passive"))
      (node (ref "C7") (pin "1") (pinfunction "1_1") (pintype "passive"))
      (node (ref "C70") (pin "2") (pinfunction "2_2") (pintype "passive"))
      (node (ref "C71") (pin "2") (pinfunction "2_2") (pintype "passive"))
      (node (ref "C72") (pin "2") (pinfunction "2_2") (pintype "passive"))
      (node (ref "C73") (pin "2") (pinfunction "2_2") (pintype "passive"))
      (node (ref "C74") (pin "2") (pinfunction "2_2") (pintype "passive"))
      (node (ref "C75") (pin "1") (pinfunction "1_1") (pintype "passive"))
      (node (ref "C76") (pin "2") (pinfunction "2_2") (pintype "passive"))
      (node (ref "C77") (pin "2") (pinfunction "2_2") (pintype "passive"))
      (node (ref "C78") (pin "2") (pinfunction "2_2") (pintype "passive"))
      (node (ref "C79") (pin "2") (pinfunction "2_2") (pintype "passive"))
      (node (ref "C8") (pin "1") (pinfunction "1_1") (pintype "passive"))
      (node (ref "C80") (pin "2") (pinfunction "2_2") (pintype "passive"))
      (node (ref "C81") (pin "2") (pinfunction "2_2") (pintype "passive"))
      (node (ref "C82") (pin "2") (pinfunction "2_2") (pintype "passive"))
      (node (ref "C83") (pin "2") (pinfunction "2_2") (pintype "passive"))
      (node (ref "C84") (pin "2") (pinfunction "2_2") (pintype "passive"))
      (node (ref "C86") (pin "1") (pinfunction "1_1") (pintype "passive"))
      (node (ref "C87") (pin "1") (pinfunction "1_1") (pintype "passive"))
      (node (ref "C9") (pin "1") (pinfunction "1_1") (pintype "passive"))
      (node (ref "C91") (pin "2") (pinfunction "2_2") (pintype "passive"))
      (node (ref "C92") (pin "2") (pinfunction "2_2") (pintype "passive"))
      (node (ref "CHANNEL1") (pin "10") (pinfunction "GND_10") (pintype "bidirectional"))
      (node (ref "CHANNEL1") (pin "27") (pinfunction "GND_27") (pintype "bidirectional"))
      (node (ref "CHANNEL1") (pin "28") (pinfunction "GND_28") (pintype "bidirectional"))
      (node (ref "CHANNEL1") (pin "9") (pinfunction "GND_9") (pintype "bidirectional"))
      (node (ref "CHANNEL2") (pin "10") (pinfunction "GND_10") (pintype "bidirectional"))
      (node (ref "CHANNEL2") (pin "27") (pinfunction "GND_27") (pintype "bidirectional"))
      (node (ref "CHANNEL2") (pin "28") (pinfunction "GND_28") (pintype "bidirectional"))
      (node (ref "CHANNEL2") (pin "9") (pinfunction "GND_9") (pintype "bidirectional"))
      (node (ref "CON3") (pin "1") (pinfunction "GND1_1") (pintype "bidirectional"))
      (node (ref "CON3") (pin "11") (pinfunction "GND6_11") (pintype "bidirectional"))
      (node (ref "CON3") (pin "13") (pinfunction "GND7_13") (pintype "bidirectional"))
      (node (ref "CON3") (pin "3") (pinfunction "GND2_3") (pintype "bidirectional"))
      (node (ref "CON3") (pin "5") (pinfunction "GND3_5") (pintype "bidirectional"))
      (node (ref "CON3") (pin "7") (pinfunction "GND4_7") (pintype "bidirectional"))
      (node (ref "CON3") (pin "9") (pinfunction "GND5_9") (pintype "bidirectional"))
      (node (ref "CON6") (pin "A2") (pinfunction "A2~{GND}_A2") (pintype "bidirectional"))
      (node (ref "CON6") (pin "A21") (pinfunction "A21~{GND}_A21") (pintype "bidirectional"))
      (node (ref "CON6") (pin "A32") (pinfunction "A32~{GND}_A32") (pintype "bidirectional"))
      (node (ref "CON6") (pin "B13") (pinfunction "B13~{GND}_B13") (pintype "bidirectional"))
      (node (ref "CON6") (pin "B2") (pinfunction "B2~{GND}_B2") (pintype "bidirectional"))
      (node (ref "CON6") (pin "B21") (pinfunction "B21~{GND}_B21") (pintype "bidirectional"))
      (node (ref "CON6") (pin "B32") (pinfunction "B32~{GND}_B32") (pintype "bidirectional"))
      (node (ref "CON6") (pin "B5") (pinfunction "B5~{GND}_B5") (pintype "bidirectional"))
      (node (ref "CON6") (pin "C17") (pinfunction "C17~{GND}_C17") (pintype "bidirectional"))
      (node (ref "CON6") (pin "C26") (pinfunction "C26~{GND}_C26") (pintype "bidirectional"))
      (node (ref "CON6") (pin "C32") (pinfunction "C32~{GND}_C32") (pintype "bidirectional"))
      (node (ref "CON6") (pin "C4") (pinfunction "C4~{GND}_C4") (pintype "bidirectional"))
      (node (ref "CON6") (pin "C8") (pinfunction "C8~{GND}_C8") (pintype "bidirectional"))
      (node (ref "CON6") (pin "D26") (pinfunction "D26~{GND}_D26") (pintype "bidirectional"))
      (node (ref "CON6") (pin "D4") (pinfunction "D4~{GND}_D4") (pintype "bidirectional"))
      (node (ref "CON6") (pin "E31") (pinfunction "E31~{GND}_E31") (pintype "bidirectional"))
      (node (ref "CON6") (pin "E32") (pinfunction "E32~{GND}_E32") (pintype "bidirectional"))
      (node (ref "D1") (pin "A") (pinfunction "A_A") (pintype "passive"))
      (node (ref "D3") (pin "3") (pinfunction "A_3") (pintype "passive"))
      (node (ref "D4") (pin "2") (pinfunction "C_2") (pintype "passive"))
      (node (ref "DC1") (pin "2") (pinfunction "-VIN_2") (pintype "passive"))
      (node (ref "DC1") (pin "5") (pinfunction "COM_5") (pintype "passive"))
      (node (ref "IC1") (pin "AGND") (pinfunction "AGND_AGND") (pintype "bidirectional"))
      (node (ref "IC1") (pin "PGND") (pinfunction "PGND_PGND") (pintype "bidirectional"))
      (node (ref "IC2") (pin "AGND") (pinfunction "AGND_AGND") (pintype "bidirectional"))
      (node (ref "IC2") (pin "PGND") (pinfunction "PGND_PGND") (pintype "bidirectional"))
      (node (ref "IC3") (pin "AGND") (pinfunction "AGND_AGND") (pintype "bidirectional"))
      (node (ref "IC3") (pin "PGND") (pinfunction "PGND_PGND") (pintype "bidirectional"))
      (node (ref "IC4") (pin "1") (pinfunction "GND_1") (pintype "power_in"))
      (node (ref "IC4") (pin "10") (pinfunction "S8_10") (pintype "bidirectional"))
      (node (ref "IC4") (pin "9") (pinfunction "S7_9") (pintype "bidirectional"))
      (node (ref "IC5") (pin "28") (pinfunction "UGND_28") (pintype "bidirectional"))
      (node (ref "IC5") (pin "3") (pinfunction "GND_3") (pintype "bidirectional"))
      (node (ref "JP13") (pin "17") (pinfunction "17_17") (pintype "passive"))
      (node (ref "JP13") (pin "19") (pinfunction "19_19") (pintype "passive"))
      (node (ref "JP13") (pin "2") (pinfunction "2_2") (pintype "passive"))
      (node (ref "JP2") (pin "2") (pinfunction "2_2") (pintype "passive"))
      (node (ref "JP2") (pin "6") (pinfunction "6_6") (pintype "passive"))
      (node (ref "JP4") (pin "3") (pinfunction "3_3") (pintype "passive"))
      (node (ref "JP5") (pin "2") (pinfunction "2_2") (pintype "passive"))
      (node (ref "JP5") (pin "29") (pinfunction "29_29") (pintype "passive"))
      (node (ref "JP5") (pin "30") (pinfunction "30_30") (pintype "passive"))
      (node (ref "JP5") (pin "4") (pinfunction "4_4") (pintype "passive"))
      (node (ref "JP7") (pin "3") (pinfunction "3_3") (pintype "passive"))
      (node (ref "JP9") (pin "4") (pinfunction "4_4") (pintype "passive"))
      (node (ref "JP9") (pin "6") (pinfunction "6_6") (pintype "passive"))
      (node (ref "R11") (pin "1") (pinfunction "1_1") (pintype "passive"))
      (node (ref "R18") (pin "2") (pinfunction "2_2") (pintype "passive"))
      (node (ref "R20") (pin "1") (pinfunction "1_1") (pintype "passive"))
      (node (ref "R21") (pin "2") (pinfunction "2_2") (pintype "passive"))
      (node (ref "R23") (pin "2") (pinfunction "2_2") (pintype "passive"))
      (node (ref "R25") (pin "1") (pinfunction "1_1") (pintype "passive"))
      (node (ref "R26") (pin "1") (pinfunction "E_1") (pintype "passive"))
      (node (ref "R34") (pin "1") (pinfunction "1_1") (pintype "passive"))
      (node (ref "R4") (pin "1") (pinfunction "1_1") (pintype "passive"))
      (node (ref "R45") (pin "1") (pinfunction "1_1") (pintype "passive"))
      (node (ref "R46") (pin "1") (pinfunction "1_1") (pintype "passive"))
      (node (ref "R47") (pin "1") (pinfunction "1_1") (pintype "passive"))
      (node (ref "R49") (pin "1") (pinfunction "1_1") (pintype "passive"))
      (node (ref "R51") (pin "1") (pinfunction "1_1") (pintype "passive"))
      (node (ref "R52") (pin "2") (pinfunction "2_2") (pintype "passive"))
      (node (ref "R53") (pin "2") (pinfunction "2_2") (pintype "passive"))
      (node (ref "R54") (pin "2") (pinfunction "2_2") (pintype "passive"))
      (node (ref "R55") (pin "2") (pinfunction "2_2") (pintype "passive"))
      (node (ref "R56") (pin "2") (pinfunction "2_2") (pintype "passive"))
      (node (ref "R57") (pin "2") (pinfunction "2_2") (pintype "passive"))
      (node (ref "R8") (pin "1") (pinfunction "1_1") (pintype "passive"))
      (node (ref "SJ1") (pin "2") (pinfunction "2_2") (pintype "passive"))
      (node (ref "SJ2") (pin "2") (pinfunction "2_2") (pintype "passive"))
      (node (ref "T1") (pin "4") (pinfunction "P2_4") (pintype "passive"))
      (node (ref "TP7") (pin "TP") (pinfunction "TP_TP") (pintype "input"))
      (node (ref "TP8") (pin "TP") (pinfunction "TP_TP") (pintype "input"))
      (node (ref "TP9") (pin "TP") (pinfunction "TP_TP") (pintype "input"))
      (node (ref "U1") (pin "11") (pinfunction "AGND_11") (pintype "bidirectional"))
      (node (ref "U1") (pin "14") (pinfunction "PDWN_14") (pintype "bidirectional"))
      (node (ref "U1") (pin "23") (pinfunction "DRGND_23") (pintype "bidirectional"))
      (node (ref "U1") (pin "8") (pinfunction "AGND_8") (pintype "bidirectional"))
      (node (ref "U10") (pin "4") (pinfunction "GND_4") (pintype "bidirectional"))
      (node (ref "U2") (pin "17") (pinfunction "COMM_17") (pintype "bidirectional"))
      (node (ref "U2") (pin "20") (pinfunction "COMM_20") (pintype "bidirectional"))
      (node (ref "U2") (pin "6") (pinfunction "COML_6") (pintype "bidirectional"))
      (node (ref "U2") (pin "9") (pinfunction "MODE_9") (pintype "bidirectional"))
      (node (ref "U3") (pin "2") (pinfunction "GND_2") (pintype "input"))
      (node (ref "U4") (pin "2") (pinfunction "GND_2") (pintype "bidirectional"))
      (node (ref "U5") (pin "13") (pinfunction "GND_3_13") (pintype "passive"))
      (node (ref "U5") (pin "17") (pinfunction "GND_17") (pintype "output"))
      (node (ref "U5") (pin "4") (pinfunction "GND_2_4") (pintype "passive"))
      (node (ref "U5") (pin "8") (pinfunction "GND_4_8") (pintype "passive"))
      (node (ref "U6") (pin "7") (pinfunction "GND_7") (pintype "passive"))
      (node (ref "U8") (pin "2") (pinfunction "GND_2") (pintype "passive"))
      (node (ref "U9") (pin "2") (pinfunction "GND_2") (pintype "passive"))
      (node (ref "X1") (pin "G@1") (pinfunction "2_G@1") (pintype "passive"))
      (node (ref "X1") (pin "G@2") (pinfunction "2_G@2") (pintype "passive"))
      (node (ref "X1") (pin "G@3") (pinfunction "2_G@3") (pintype "passive"))
      (node (ref "X1") (pin "G@4") (pinfunction "2_G@4") (pintype "passive"))
      (node (ref "X2") (pin "G@1") (pinfunction "2_G@1") (pintype "passive"))
      (node (ref "X2") (pin "G@2") (pinfunction "2_G@2") (pintype "passive"))
      (node (ref "X2") (pin "G@3") (pinfunction "2_G@3") (pintype "passive"))
      (node (ref "X2") (pin "G@4") (pinfunction "2_G@4") (pintype "passive"))
      (node (ref "X3") (pin "G@1") (pinfunction "2_G@1") (pintype "passive"))
      (node (ref "X3") (pin "G@2") (pinfunction "2_G@2") (pintype "passive"))
      (node (ref "X3") (pin "G@3") (pinfunction "2_G@3") (pintype "passive"))
      (node (ref "X3") (pin "G@4") (pinfunction "2_G@4") (pintype "passive"))
      (node (ref "X4") (pin "G@1") (pinfunction "2_G@1") (pintype "passive"))
      (node (ref "X4") (pin "G@2") (pinfunction "2_G@2") (pintype "passive"))
      (node (ref "X4") (pin "G@3") (pinfunction "2_G@3") (pintype "passive"))
      (node (ref "X4") (pin "G@4") (pinfunction "2_G@4") (pintype "passive"))
      (node (ref "X5") (pin "4") (pinfunction "4_4") (pintype "passive"))
      (node (ref "X5") (pin "S1") (pinfunction "S1_S1") (pintype "passive"))
      (node (ref "X5") (pin "S2") (pinfunction "S2_S2") (pintype "passive"))
    )
    (net (code "39") (name "HS1") (class "Default")
      (node (ref "CON6") (pin "E14") (pinfunction "E14~{B16}IO_L63P_SCP7_0_E14") (pintype "bidirectional"))
      (node (ref "U8") (pin "3") (pinfunction "A_3") (pintype "input"))
    )
    (net (code "40") (name "HS1DIR") (class "Default")
      (node (ref "CON6") (pin "A15") (pinfunction "A15~{C14}IO_L46N_0_A15") (pintype "bidirectional"))
      (node (ref "U8") (pin "5") (pinfunction "DIR_5") (pintype "input"))
    )
    (net (code "41") (name "HS2") (class "Default")
      (node (ref "CON6") (pin "A14") (pinfunction "A14~{A17}IO_L64N_SCP4_0_A14") (pintype "bidirectional"))
      (node (ref "U9") (pin "3") (pinfunction "A_3") (pintype "input"))
    )
    (net (code "42") (name "HS2DIR") (class "Default")
      (node (ref "CON6") (pin "B14") (pinfunction "B14~{C17}IO_L64P_SCP5_0_B14") (pintype "bidirectional"))
      (node (ref "U9") (pin "5") (pinfunction "DIR_5") (pintype "input"))
    )
    (net (code "43") (name "LED1") (class "Default")
      (node (ref "CON6") (pin "F16") (pinfunction "F16~{AA18}IO_L2P_CMPCLK_2_F16") (pintype "bidirectional"))
      (node (ref "LED1") (pin "A") (pinfunction "A_A") (pintype "passive"))
      (node (ref "LED7") (pin "A") (pinfunction "A_A") (pintype "passive"))
      (node (ref "R37") (pin "1") (pinfunction "1_1") (pintype "passive"))
    )
    (net (code "44") (name "LED2") (class "Default")
      (node (ref "CON6") (pin "D17") (pinfunction "D17~{Y15}IO_L5P_2_D17") (pintype "bidirectional"))
      (node (ref "LED2") (pin "A") (pinfunction "A_A") (pintype "passive"))
      (node (ref "LED8") (pin "A") (pinfunction "A_A") (pintype "passive"))
    )
    (net (code "45") (name "LED3") (class "Default")
      (node (ref "CON6") (pin "F17") (pinfunction "F17~{AA16}IO_L4P_2_F17") (pintype "bidirectional"))
      (node (ref "LED3") (pin "A") (pinfunction "A_A") (pintype "passive"))
      (node (ref "LED9") (pin "A") (pinfunction "A_A") (pintype "passive"))
    )
    (net (code "46") (name "LED4") (class "Default")
      (node (ref "CON6") (pin "F18") (pinfunction "F18~{AB15}IO_L5N_2_F18") (pintype "bidirectional"))
      (node (ref "LED10") (pin "A") (pinfunction "A_A") (pintype "passive"))
      (node (ref "LED4") (pin "A") (pinfunction "A_A") (pintype "passive"))
    )
    (net (code "47") (name "LED5") (class "Default")
      (node (ref "CON6") (pin "D19") (pinfunction "D19~{V15}IO_L13N_D10_2_D19") (pintype "bidirectional"))
      (node (ref "LED11") (pin "A") (pinfunction "A_A") (pintype "passive"))
      (node (ref "LED5") (pin "A") (pinfunction "A_A") (pintype "passive"))
    )
    (net (code "48") (name "LED6") (class "Default")
      (node (ref "CON6") (pin "F19") (pinfunction "F19~{W14}IO_L16P_2_F19") (pintype "bidirectional"))
      (node (ref "LED12") (pin "A") (pinfunction "A_A") (pintype "passive"))
      (node (ref "LED6") (pin "A") (pinfunction "A_A") (pintype "passive"))
    )
    (net (code "49") (name "Net-(C2-Pad2)") (class "Default")
      (node (ref "C2") (pin "2") (pinfunction "2_2") (pintype "passive"))
      (node (ref "R2") (pin "1") (pinfunction "1_1") (pintype "passive"))
    )
    (net (code "50") (name "Net-(C5-Pad2)") (class "Default")
      (node (ref "C5") (pin "2") (pinfunction "2_2") (pintype "passive"))
      (node (ref "R6") (pin "1") (pinfunction "1_1") (pintype "passive"))
    )
    (net (code "51") (name "Net-(C10-Pad2)") (class "Default")
      (node (ref "C10") (pin "2") (pinfunction "2_2") (pintype "passive"))
      (node (ref "R9") (pin "1") (pinfunction "1_1") (pintype "passive"))
    )
    (net (code "52") (name "Net-(C12-Pad2)") (class "Default")
      (node (ref "C12") (pin "2") (pinfunction "2_2") (pintype "passive"))
      (node (ref "R15") (pin "1") (pinfunction "1_1") (pintype "passive"))
    )
    (net (code "53") (name "Net-(C15-Pad2)") (class "Default")
      (node (ref "C15") (pin "2") (pinfunction "2_2") (pintype "passive"))
      (node (ref "R16") (pin "1") (pinfunction "1_1") (pintype "passive"))
    )
    (net (code "54") (name "Net-(C23-Pad2)") (class "Default")
      (node (ref "C23") (pin "2") (pinfunction "2_2") (pintype "passive"))
      (node (ref "JP3") (pin "1") (pinfunction "1_1") (pintype "passive"))
    )
    (net (code "55") (name "Net-(C46-Pad2)") (class "Default")
      (node (ref "C46") (pin "2") (pinfunction "2_2") (pintype "passive"))
      (node (ref "L7") (pin "2") (pinfunction "2_2") (pintype "passive"))
    )
    (net (code "56") (name "Net-(C51-Pad1)") (class "Default")
      (node (ref "C51") (pin "1") (pinfunction "1_1") (pintype "passive"))
      (node (ref "R27") (pin "2") (pinfunction "2_2") (pintype "passive"))
      (node (ref "R28") (pin "1") (pinfunction "1_1") (pintype "passive"))
    )
    (net (code "57") (name "Net-(C53-Pad1)") (class "Default")
      (node (ref "C53") (pin "1") (pinfunction "1_1") (pintype "passive"))
      (node (ref "L8") (pin "1") (pinfunction "1_1") (pintype "passive"))
    )
    (net (code "58") (name "Net-(C53-Pad2)") (class "Default")
      (node (ref "C53") (pin "2") (pinfunction "2_2") (pintype "passive"))
      (node (ref "X1") (pin "1") (pinfunction "1_1") (pintype "passive"))
    )
    (net (code "59") (name "Net-(C88-Pad1)") (class "Default")
      (node (ref "C88") (pin "1") (pinfunction "1_1") (pintype "passive"))
      (node (ref "X3") (pin "1") (pinfunction "1_1") (pintype "passive"))
    )
    (net (code "60") (name "Net-(C88-Pad2)") (class "Default")
      (node (ref "C88") (pin "2") (pinfunction "2_2") (pintype "passive"))
      (node (ref "C90") (pin "2") (pinfunction "2_2") (pintype "passive"))
      (node (ref "R33") (pin "2") (pinfunction "2_2") (pintype "passive"))
      (node (ref "R44") (pin "1") (pinfunction "1_1") (pintype "passive"))
      (node (ref "R46") (pin "2") (pinfunction "2_2") (pintype "passive"))
    )
    (net (code "61") (name "Net-(C89-Pad1)") (class "Default")
      (node (ref "C89") (pin "1") (pinfunction "1_1") (pintype "passive"))
      (node (ref "JP9") (pin "5") (pinfunction "5_5") (pintype "passive"))
    )
    (net (code "62") (name "Net-(C89-Pad2)") (class "Default")
      (node (ref "C89") (pin "2") (pinfunction "2_2") (pintype "passive"))
      (node (ref "R32") (pin "1") (pinfunction "1_1") (pintype "passive"))
      (node (ref "R43") (pin "1") (pinfunction "1_1") (pintype "passive"))
      (node (ref "R45") (pin "2") (pinfunction "2_2") (pintype "passive"))
    )
    (net (code "63") (name "Net-(C90-Pad1)") (class "Default")
      (node (ref "C90") (pin "1") (pinfunction "1_1") (pintype "passive"))
      (node (ref "JP9") (pin "3") (pinfunction "3_3") (pintype "passive"))
    )
    (net (code "64") (name "Net-(CHANNEL1-ADC0)") (class "Default")
      (node (ref "CHANNEL1") (pin "24") (pinfunction "ADC0_24") (pintype "bidirectional"))
      (node (ref "CON6") (pin "C21") (pinfunction "C21~{AA12}IO_L30P_GCLK1_D13_2_C21") (pintype "bidirectional"))
    )
    (net (code "65") (name "Net-(CHANNEL1-ADC1)") (class "Default")
      (node (ref "CHANNEL1") (pin "21") (pinfunction "ADC1_21") (pintype "bidirectional"))
      (node (ref "CON6") (pin "C22") (pinfunction "C22~{Y10}IO_L29N_GCLK2_2_C22") (pintype "bidirectional"))
    )
    (net (code "66") (name "Net-(CHANNEL1-ADC2)") (class "Default")
      (node (ref "CHANNEL1") (pin "22") (pinfunction "ADC2_22") (pintype "bidirectional"))
      (node (ref "CON6") (pin "F21") (pinfunction "F21~{AB14}IO_L15N_2_F21") (pintype "bidirectional"))
    )
    (net (code "67") (name "Net-(CHANNEL1-ADC3)") (class "Default")
      (node (ref "CHANNEL1") (pin "19") (pinfunction "ADC3_19") (pintype "bidirectional"))
      (node (ref "CON6") (pin "F22") (pinfunction "F22~{AB11}IO_L31N_GCLK30_D15_2_F22") (pintype "bidirectional"))
    )
    (net (code "68") (name "Net-(CHANNEL1-ADC4)") (class "Default")
      (node (ref "CHANNEL1") (pin "20") (pinfunction "ADC4_20") (pintype "bidirectional"))
      (node (ref "CON6") (pin "D22") (pinfunction "D22~{AB12}IO_L30N_GCLK0_USERCCLK_2_D22") (pintype "bidirectional"))
    )
    (net (code "69") (name "Net-(CHANNEL1-ADC5)") (class "Default")
      (node (ref "CHANNEL1") (pin "7") (pinfunction "ADC5_7") (pintype "bidirectional"))
      (node (ref "CON6") (pin "C24") (pinfunction "C24~{Y13}IO_L41P_2_C24") (pintype "bidirectional"))
    )
    (net (code "70") (name "Net-(CHANNEL1-ADC6)") (class "Default")
      (node (ref "CHANNEL1") (pin "8") (pinfunction "ADC6_8") (pintype "bidirectional"))
      (node (ref "CON6") (pin "F23") (pinfunction "F23~{W11}IO_L29P_GCLK3_2_F23") (pintype "bidirectional"))
    )
    (net (code "71") (name "Net-(CHANNEL1-ADC7)") (class "Default")
      (node (ref "CHANNEL1") (pin "5") (pinfunction "ADC7_5") (pintype "bidirectional"))
      (node (ref "CON6") (pin "F24") (pinfunction "F24~{U14}IO_L20N_2_F24") (pintype "bidirectional"))
    )
    (net (code "72") (name "Net-(CHANNEL1-ADC8)") (class "Default")
      (node (ref "CHANNEL1") (pin "6") (pinfunction "ADC8_6") (pintype "bidirectional"))
      (node (ref "CON6") (pin "D24") (pinfunction "D24~{T14}IO_L20P_2_D24") (pintype "bidirectional"))
    )
    (net (code "73") (name "Net-(CHANNEL1-ADC9)") (class "Default")
      (node (ref "CHANNEL1") (pin "3") (pinfunction "ADC9_3") (pintype "bidirectional"))
      (node (ref "CON6") (pin "D25") (pinfunction "D25~{W12}IO_L42P_2_D25") (pintype "bidirectional"))
    )
    (net (code "74") (name "Net-(CHANNEL1-ADCOR)") (class "Default")
      (node (ref "CHANNEL1") (pin "4") (pinfunction "ADCOR_4") (pintype "bidirectional"))
      (node (ref "CON6") (pin "C25") (pinfunction "C25~{W9}IO_L47P_2_C25") (pintype "bidirectional"))
    )
    (net (code "75") (name "Net-(CHANNEL1-CLKADC)") (class "Default")
      (node (ref "CHANNEL1") (pin "23") (pinfunction "CLKADC_23") (pintype "bidirectional"))
      (node (ref "CON6") (pin "D21") (pinfunction "D21~{AA14}IO_L15P_2_D21") (pintype "bidirectional"))
    )
    (net (code "76") (name "Net-(CHANNEL1-GAIN)") (class "Default")
      (node (ref "CHANNEL1") (pin "25") (pinfunction "GAIN_25") (pintype "bidirectional"))
      (node (ref "CON6") (pin "F20") (pinfunction "F20~{Y16}IO_L14N_D12_2_F20") (pintype "bidirectional"))
    )
    (net (code "77") (name "Net-(CHANNEL1-HILO)") (class "Default")
      (node (ref "CHANNEL1") (pin "26") (pinfunction "HILO_26") (pintype "bidirectional"))
      (node (ref "CON6") (pin "D20") (pinfunction "D20~{W15}IO_L14P_D11_2_D20") (pintype "bidirectional"))
    )
    (net (code "78") (name "Net-(CHANNEL1-TRIGIN)") (class "Default")
      (node (ref "CHANNEL1") (pin "2") (pinfunction "TRIGIN_2") (pintype "bidirectional"))
      (node (ref "CON6") (pin "F25") (pinfunction "F25~{Y12}IO_L42N_2_F25") (pintype "bidirectional"))
    )
    (net (code "79") (name "Net-(CON3-TCK)") (class "Default")
      (node (ref "CON3") (pin "6") (pinfunction "TCK_6") (pintype "bidirectional"))
      (node (ref "CON6") (pin "D31") (pinfunction "D31~{D14}TCK_D31") (pintype "bidirectional"))
    )
    (net (code "80") (name "Net-(CON3-TDI)") (class "Default")
      (node (ref "CON3") (pin "10") (pinfunction "TDI_10") (pintype "bidirectional"))
      (node (ref "CON6") (pin "D29") (pinfunction "D29~{E18}TDI_D29") (pintype "bidirectional"))
    )
    (net (code "81") (name "Net-(CON3-TDO)") (class "Default")
      (node (ref "CON3") (pin "8") (pinfunction "TDO_8") (pintype "bidirectional"))
      (node (ref "CON6") (pin "D32") (pinfunction "D32~{TDO}_D32") (pintype "bidirectional"))
    )
    (net (code "82") (name "Net-(CON3-TMS)") (class "Default")
      (node (ref "CON3") (pin "4") (pinfunction "TMS_4") (pintype "bidirectional"))
      (node (ref "CON6") (pin "D30") (pinfunction "D30~{E16}TMS_D30") (pintype "bidirectional"))
    )
    (net (code "83") (name "Net-(CON6A-A28~{C6}IO_L3N_0)") (class "Default")
      (node (ref "CON6") (pin "A28") (pinfunction "A28~{C6}IO_L3N_0_A28") (pintype "bidirectional"))
      (node (ref "R35") (pin "2") (pinfunction "2_2") (pintype "passive"))
      (node (ref "U10") (pin "5") (pinfunction "SDA_5") (pintype "bidirectional"))
    )
    (net (code "84") (name "Net-(CON6A-B28~{D6}IO_L3P_0)") (class "Default")
      (node (ref "CON6") (pin "B28") (pinfunction "B28~{D6}IO_L3P_0_B28") (pintype "bidirectional"))
      (node (ref "R36") (pin "2") (pinfunction "2_2") (pintype "passive"))
      (node (ref "U10") (pin "6") (pinfunction "SCL_6") (pintype "bidirectional"))
    )
    (net (code "85") (name "Net-(CON6F-C1~{USB_5V})") (class "Default")
      (node (ref "CON6") (pin "C1") (pinfunction "C1~{USB_5V}_C1") (pintype "bidirectional"))
      (node (ref "CON6") (pin "D1") (pinfunction "D1~{USB_5V}_D1") (pintype "bidirectional"))
      (node (ref "JP1") (pin "2") (pinfunction "2_2") (pintype "passive"))
    )
    (net (code "86") (name "Net-(CON6F-C2~{5V})") (class "Default")
      (node (ref "CON6") (pin "C2") (pinfunction "C2~{5V}_C2") (pintype "bidirectional"))
      (node (ref "CON6") (pin "D2") (pinfunction "D2~{5V}_D2") (pintype "bidirectional"))
      (node (ref "CON6") (pin "D3") (pinfunction "D3~{5V}_D3") (pintype "bidirectional"))
    )
    (net (code "87") (name "Net-(CON6F-F26~{VREF_3.3})") (class "Default")
      (node (ref "CON6") (pin "F26") (pinfunction "F26~{VREF_3.3}_F26") (pintype "bidirectional"))
      (node (ref "CON6") (pin "F32") (pinfunction "F32~{VREF_3.3}_F32") (pintype "bidirectional"))
    )
    (net (code "88") (name "Net-(D1-PadC)") (class "Default")
      (node (ref "D1") (pin "C") (pinfunction "C_C") (pintype "passive"))
      (node (ref "IC3") (pin "LX") (pinfunction "LX_LX") (pintype "bidirectional"))
      (node (ref "L3") (pin "1") (pinfunction "1_1") (pintype "passive"))
    )
    (net (code "89") (name "Net-(D4-A)") (class "Default")
      (node (ref "C52") (pin "1") (pinfunction "1_1") (pintype "passive"))
      (node (ref "D4") (pin "3") (pinfunction "A_3") (pintype "passive"))
      (node (ref "R28") (pin "2") (pinfunction "2_2") (pintype "passive"))
      (node (ref "U2") (pin "10") (pinfunction "GAIN_10") (pintype "bidirectional"))
    )
    (net (code "90") (name "Net-(DC1-+VOUT)") (class "Default")
      (node (ref "C74") (pin "1") (pinfunction "1_1") (pintype "passive"))
      (node (ref "DC1") (pin "6") (pinfunction "+VOUT_6") (pintype "passive"))
      (node (ref "IC7") (pin "3") (pinfunction "IN_3") (pintype "input"))
    )
    (net (code "91") (name "Net-(DC1--VOUT)") (class "Default")
      (node (ref "C75") (pin "2") (pinfunction "2_2") (pintype "passive"))
      (node (ref "DC1") (pin "4") (pinfunction "-VOUT_4") (pintype "passive"))
      (node (ref "IC6") (pin "IN") (pinfunction "IN_IN") (pintype "input"))
    )
    (net (code "92") (name "Net-(IC1-PadCOMP)") (class "Default")
      (node (ref "IC1") (pin "COMP") (pinfunction "COMP_COMP") (pintype "bidirectional"))
      (node (ref "R2") (pin "2") (pinfunction "2_2") (pintype "passive"))
    )
    (net (code "93") (name "Net-(IC1-PadEN)") (class "Default")
      (node (ref "IC1") (pin "EN") (pinfunction "EN_EN") (pintype "bidirectional"))
      (node (ref "R1") (pin "1") (pinfunction "1_1") (pintype "passive"))
    )
    (net (code "94") (name "Net-(IC1-PadFB)") (class "Default")
      (node (ref "IC1") (pin "FB") (pinfunction "FB_FB") (pintype "bidirectional"))
      (node (ref "R3") (pin "1") (pinfunction "1_1") (pintype "passive"))
      (node (ref "R4") (pin "2") (pinfunction "2_2") (pintype "passive"))
    )
    (net (code "95") (name "Net-(IC2-PadCOMP)") (class "Default")
      (node (ref "IC2") (pin "COMP") (pinfunction "COMP_COMP") (pintype "bidirectional"))
      (node (ref "R6") (pin "2") (pinfunction "2_2") (pintype "passive"))
    )
    (net (code "96") (name "Net-(IC2-PadEN)") (class "Default")
      (node (ref "IC2") (pin "EN") (pinfunction "EN_EN") (pintype "bidirectional"))
      (node (ref "R5") (pin "1") (pinfunction "1_1") (pintype "passive"))
    )
    (net (code "97") (name "Net-(IC2-PadFB)") (class "Default")
      (node (ref "IC2") (pin "FB") (pinfunction "FB_FB") (pintype "bidirectional"))
      (node (ref "R7") (pin "1") (pinfunction "1_1") (pintype "passive"))
      (node (ref "R8") (pin "2") (pinfunction "2_2") (pintype "passive"))
    )
    (net (code "98") (name "Net-(IC3-PadCOMP)") (class "Default")
      (node (ref "IC3") (pin "COMP") (pinfunction "COMP_COMP") (pintype "bidirectional"))
      (node (ref "R9") (pin "2") (pinfunction "2_2") (pintype "passive"))
    )
    (net (code "99") (name "Net-(IC3-PadEN)") (class "Default")
      (node (ref "IC3") (pin "EN") (pinfunction "EN_EN") (pintype "bidirectional"))
      (node (ref "R12") (pin "1") (pinfunction "1_1") (pintype "passive"))
    )
    (net (code "100") (name "Net-(IC3-PadFB)") (class "Default")
      (node (ref "IC3") (pin "FB") (pinfunction "FB_FB") (pintype "bidirectional"))
      (node (ref "R10") (pin "1") (pinfunction "1_1") (pintype "passive"))
      (node (ref "R11") (pin "2") (pinfunction "2_2") (pintype "passive"))
    )
    (net (code "101") (name "Net-(IC4-DREF)") (class "Default")
      (node (ref "C92") (pin "1") (pinfunction "1_1") (pintype "passive"))
      (node (ref "IC4") (pin "19") (pinfunction "DREF_19") (pintype "bidirectional"))
      (node (ref "IC4") (pin "20") (pinfunction "GREF_20") (pintype "bidirectional"))
      (node (ref "R38") (pin "2") (pinfunction "2_2") (pintype "passive"))
    )
    (net (code "102") (name "Net-(IC4-S1)") (class "Default")
      (node (ref "IC4") (pin "3") (pinfunction "S1_3") (pintype "bidirectional"))
      (node (ref "JP13") (pin "15") (pinfunction "15_15") (pintype "passive"))
    )
    (net (code "103") (name "Net-(IC4-S2)") (class "Default")
      (node (ref "IC4") (pin "4") (pinfunction "S2_4") (pintype "bidirectional"))
      (node (ref "JP13") (pin "13") (pinfunction "13_13") (pintype "passive"))
    )
    (net (code "104") (name "Net-(IC4-S3)") (class "Default")
      (node (ref "IC4") (pin "5") (pinfunction "S3_5") (pintype "bidirectional"))
      (node (ref "JP13") (pin "11") (pinfunction "11_11") (pintype "passive"))
    )
    (net (code "105") (name "Net-(IC4-S4)") (class "Default")
      (node (ref "IC4") (pin "6") (pinfunction "S4_6") (pintype "bidirectional"))
      (node (ref "JP13") (pin "9") (pinfunction "9_9") (pintype "passive"))
    )
    (net (code "106") (name "Net-(IC4-S5)") (class "Default")
      (node (ref "IC4") (pin "7") (pinfunction "S5_7") (pintype "bidirectional"))
      (node (ref "JP13") (pin "7") (pinfunction "7_7") (pintype "passive"))
    )
    (net (code "107") (name "Net-(IC4-S6)") (class "Default")
      (node (ref "IC4") (pin "8") (pinfunction "S6_8") (pintype "bidirectional"))
      (node (ref "JP13") (pin "5") (pinfunction "5_5") (pintype "passive"))
    )
    (net (code "108") (name "Net-(IC4-SREF)") (class "Default")
      (node (ref "C68") (pin "1") (pinfunction "1_1") (pintype "passive"))
      (node (ref "C69") (pin "1") (pinfunction "1_1") (pintype "passive"))
      (node (ref "C70") (pin "1") (pinfunction "1_1") (pintype "passive"))
      (node (ref "C71") (pin "1") (pinfunction "1_1") (pintype "passive"))
      (node (ref "C72") (pin "1") (pinfunction "1_1") (pintype "passive"))
      (node (ref "IC4") (pin "2") (pinfunction "SREF_2") (pintype "bidirectional"))
      (node (ref "JP13") (pin "8") (pinfunction "8_8") (pintype "passive"))
      (node (ref "U6") (pin "14") (pinfunction "VCCB_14") (pintype "power_in"))
      (node (ref "U8") (pin "6") (pinfunction "VCCB_6") (pintype "power_in"))
      (node (ref "U9") (pin "6") (pinfunction "VCCB_6") (pintype "power_in"))
    )
    (net (code "109") (name "Net-(IC5-D+)") (class "Default")
      (node (ref "IC5") (pin "29") (pinfunction "D+_29") (pintype "bidirectional"))
      (node (ref "R40") (pin "2") (pinfunction "2_2") (pintype "passive"))
    )
    (net (code "110") (name "Net-(IC5-D-)") (class "Default")
      (node (ref "IC5") (pin "30") (pinfunction "D-_30") (pintype "bidirectional"))
      (node (ref "R39") (pin "2") (pinfunction "2_2") (pintype "passive"))
    )
    (net (code "111") (name "Net-(IC5-PC1({slash}RESET))") (class "Default")
      (node (ref "IC5") (pin "24") (pinfunction "PC1(/RESET)_24") (pintype "bidirectional"))
      (node (ref "R58") (pin "2") (pinfunction "2_2") (pintype "passive"))
      (node (ref "SJ2") (pin "1") (pinfunction "1_1") (pintype "passive"))
    )
    (net (code "112") (name "Net-(IC5-PD2(INT2{slash}AIN1{slash}RXD1))") (class "Default")
      (node (ref "IC5") (pin "8") (pinfunction "PD2(INT2/AIN1/RXD1)_8") (pintype "bidirectional"))
      (node (ref "R41") (pin "1") (pinfunction "1_1") (pintype "passive"))
    )
    (net (code "113") (name "Net-(IC5-PD3(INT3{slash}TXD1))") (class "Default")
      (node (ref "IC5") (pin "9") (pinfunction "PD3(INT3/TXD1)_9") (pintype "bidirectional"))
      (node (ref "R42") (pin "1") (pinfunction "1_1") (pintype "passive"))
    )
    (net (code "114") (name "Net-(IC5-PD7(INT7{slash}HWB{slash}CTS{slash}T0))") (class "Default")
      (node (ref "IC5") (pin "13") (pinfunction "PD7(INT7/HWB/CTS/T0)_13") (pintype "bidirectional"))
      (node (ref "SJ1") (pin "1") (pinfunction "1_1") (pintype "passive"))
    )
    (net (code "115") (name "Net-(IC5-UCAP)") (class "Default")
      (node (ref "C73") (pin "1") (pinfunction "1_1") (pintype "passive"))
      (node (ref "IC5") (pin "27") (pinfunction "UCAP_27") (pintype "bidirectional"))
    )
    (net (code "116") (name "Net-(IC5-XTAL1)") (class "Default")
      (node (ref "C76") (pin "1") (pinfunction "1_1") (pintype "passive"))
      (node (ref "IC5") (pin "1") (pinfunction "XTAL1_1") (pintype "bidirectional"))
      (node (ref "XTAL1") (pin "2") (pinfunction "2_2") (pintype "passive"))
    )
    (net (code "117") (name "Net-(IC5-XTAL2)") (class "Default")
      (node (ref "C77") (pin "1") (pinfunction "1_1") (pintype "passive"))
      (node (ref "IC5") (pin "2") (pinfunction "XTAL2_2") (pintype "bidirectional"))
      (node (ref "XTAL1") (pin "1") (pinfunction "1_1") (pintype "passive"))
    )
    (net (code "118") (name "Net-(IC6-PadADJ)") (class "Default")
      (node (ref "IC6") (pin "ADJ") (pinfunction "ADJ_ADJ") (pintype "input"))
      (node (ref "R50") (pin "1") (pinfunction "1_1") (pintype "passive"))
      (node (ref "R51") (pin "2") (pinfunction "2_2") (pintype "passive"))
    )
    (net (code "119") (name "Net-(IC7-ADJ)") (class "Default")
      (node (ref "IC7") (pin "1") (pinfunction "ADJ_1") (pintype "input"))
      (node (ref "R48") (pin "1") (pinfunction "1_1") (pintype "passive"))
      (node (ref "R49") (pin "2") (pinfunction "2_2") (pintype "passive"))
    )
    (net (code "120") (name "Net-(JP3-Pad2)") (class "Default")
      (node (ref "JP3") (pin "2") (pinfunction "2_2") (pintype "passive"))
      (node (ref "R22") (pin "1") (pinfunction "1_1") (pintype "passive"))
    )
    (net (code "121") (name "Net-(L1-1)") (class "Default")
      (node (ref "IC1") (pin "LX") (pinfunction "LX_LX") (pintype "bidirectional"))
      (node (ref "L1") (pin "P$1") (pinfunction "1_P$1") (pintype "passive"))
    )
    (net (code "122") (name "Net-(L4-1)") (class "Default")
      (node (ref "IC2") (pin "LX") (pinfunction "LX_LX") (pintype "bidirectional"))
      (node (ref "L4") (pin "P$1") (pinfunction "1_P$1") (pintype "passive"))
    )
    (net (code "123") (name "Net-(L7-Pad1)") (class "Default")
      (node (ref "L7") (pin "1") (pinfunction "1_1") (pintype "passive"))
      (node (ref "X2") (pin "1") (pinfunction "1_1") (pintype "passive"))
    )
    (net (code "124") (name "Net-(LED1-PadC)") (class "Default")
      (node (ref "LED1") (pin "C") (pinfunction "C_C") (pintype "passive"))
      (node (ref "LED7") (pin "C") (pinfunction "C_C") (pintype "passive"))
      (node (ref "R52") (pin "1") (pinfunction "1_1") (pintype "passive"))
    )
    (net (code "125") (name "Net-(LED2-PadC)") (class "Default")
      (node (ref "LED2") (pin "C") (pinfunction "C_C") (pintype "passive"))
      (node (ref "LED8") (pin "C") (pinfunction "C_C") (pintype "passive"))
      (node (ref "R53") (pin "1") (pinfunction "1_1") (pintype "passive"))
    )
    (net (code "126") (name "Net-(LED3-PadC)") (class "Default")
      (node (ref "LED3") (pin "C") (pinfunction "C_C") (pintype "passive"))
      (node (ref "LED9") (pin "C") (pinfunction "C_C") (pintype "passive"))
      (node (ref "R54") (pin "1") (pinfunction "1_1") (pintype "passive"))
    )
    (net (code "127") (name "Net-(LED10-PadC)") (class "Default")
      (node (ref "LED10") (pin "C") (pinfunction "C_C") (pintype "passive"))
      (node (ref "LED4") (pin "C") (pinfunction "C_C") (pintype "passive"))
      (node (ref "R55") (pin "1") (pinfunction "1_1") (pintype "passive"))
    )
    (net (code "128") (name "Net-(LED11-PadC)") (class "Default")
      (node (ref "LED11") (pin "C") (pinfunction "C_C") (pintype "passive"))
      (node (ref "LED5") (pin "C") (pinfunction "C_C") (pintype "passive"))
      (node (ref "R56") (pin "1") (pinfunction "1_1") (pintype "passive"))
    )
    (net (code "129") (name "Net-(LED12-PadC)") (class "Default")
      (node (ref "LED12") (pin "C") (pinfunction "C_C") (pintype "passive"))
      (node (ref "LED6") (pin "C") (pinfunction "C_C") (pintype "passive"))
      (node (ref "R57") (pin "1") (pinfunction "1_1") (pintype "passive"))
    )
    (net (code "130") (name "Net-(R26-A)") (class "Default")
      (node (ref "C41") (pin "2") (pinfunction "2_2") (pintype "passive"))
      (node (ref "C42") (pin "2") (pinfunction "2_2") (pintype "passive"))
      (node (ref "R26") (pin "3") (pinfunction "A_3") (pintype "passive"))
      (node (ref "U1") (pin "4") (pinfunction "VREF_4") (pintype "bidirectional"))
    )
    (net (code "131") (name "Net-(R26-S)") (class "Default")
      (node (ref "JP4") (pin "1") (pinfunction "1_1") (pintype "passive"))
      (node (ref "R26") (pin "2") (pinfunction "S_2") (pintype "passive"))
    )
    (net (code "132") (name "Net-(R31-Pad1)") (class "Default")
      (node (ref "R31") (pin "1") (pinfunction "1_1") (pintype "passive"))
      (node (ref "R34") (pin "2") (pinfunction "2_2") (pintype "passive"))
      (node (ref "X4") (pin "1") (pinfunction "1_1") (pintype "passive"))
    )
    (net (code "133") (name "Net-(R39-Pad1)") (class "Default")
      (node (ref "R39") (pin "1") (pinfunction "1_1") (pintype "passive"))
      (node (ref "X5") (pin "2") (pinfunction "2_2") (pintype "passive"))
    )
    (net (code "134") (name "Net-(R40-Pad1)") (class "Default")
      (node (ref "R40") (pin "1") (pinfunction "1_1") (pintype "passive"))
      (node (ref "X5") (pin "3") (pinfunction "3_3") (pintype "passive"))
    )
    (net (code "135") (name "Net-(T1-P1)") (class "Default")
      (node (ref "L8") (pin "2") (pinfunction "2_2") (pintype "passive"))
      (node (ref "T1") (pin "6") (pinfunction "P1_6") (pintype "passive"))
    )
    (net (code "136") (name "Net-(T1-S1)") (class "Default")
      (node (ref "R13") (pin "2") (pinfunction "2_2") (pintype "passive"))
      (node (ref "R29") (pin "2") (pinfunction "2_2") (pintype "passive"))
      (node (ref "T1") (pin "1") (pinfunction "S1_1") (pintype "passive"))
    )
    (net (code "137") (name "Net-(T1-S2)") (class "Default")
      (node (ref "R14") (pin "2") (pinfunction "2_2") (pintype "passive"))
      (node (ref "R30") (pin "1") (pinfunction "1_1") (pintype "passive"))
      (node (ref "T1") (pin "3") (pinfunction "S2_3") (pintype "passive"))
    )
    (net (code "138") (name "Net-(T1-ST)") (class "Default")
      (node (ref "C54") (pin "1") (pinfunction "1_1") (pintype "passive"))
      (node (ref "C55") (pin "1") (pinfunction "1_1") (pintype "passive"))
      (node (ref "C56") (pin "2") (pinfunction "2_2") (pintype "passive"))
      (node (ref "C57") (pin "2") (pinfunction "2_2") (pintype "passive"))
      (node (ref "R29") (pin "1") (pinfunction "1_1") (pintype "passive"))
      (node (ref "R30") (pin "2") (pinfunction "2_2") (pintype "passive"))
      (node (ref "T1") (pin "2") (pinfunction "ST_2") (pintype "passive"))
    )
    (net (code "139") (name "Net-(U1-MODE)") (class "Default")
      (node (ref "R23") (pin "1") (pinfunction "1_1") (pintype "passive"))
      (node (ref "R24") (pin "1") (pinfunction "1_1") (pintype "passive"))
      (node (ref "U1") (pin "2") (pinfunction "MODE_2") (pintype "bidirectional"))
    )
    (net (code "140") (name "Net-(U1-REFB)") (class "Default")
      (node (ref "C37") (pin "1") (pinfunction "1_1") (pintype "passive"))
      (node (ref "C38") (pin "1") (pinfunction "1_1") (pintype "passive"))
      (node (ref "C39") (pin "2") (pinfunction "2_2") (pintype "passive"))
      (node (ref "U1") (pin "5") (pinfunction "REFB_5") (pintype "bidirectional"))
    )
    (net (code "141") (name "Net-(U1-REFT)") (class "Default")
      (node (ref "C37") (pin "2") (pinfunction "2_2") (pintype "passive"))
      (node (ref "C38") (pin "2") (pinfunction "2_2") (pintype "passive"))
      (node (ref "C40") (pin "2") (pinfunction "2_2") (pintype "passive"))
      (node (ref "U1") (pin "6") (pinfunction "REFT_6") (pintype "bidirectional"))
    )
    (net (code "142") (name "Net-(U1-SENSE)") (class "Default")
      (node (ref "C45") (pin "1") (pinfunction "1_1") (pintype "passive"))
      (node (ref "JP4") (pin "2") (pinfunction "2_2") (pintype "passive"))
      (node (ref "U1") (pin "3") (pinfunction "SENSE_3") (pintype "bidirectional"))
    )
    (net (code "143") (name "Net-(U1-VIN+)") (class "Default")
      (node (ref "C44") (pin "1") (pinfunction "1_1") (pintype "passive"))
      (node (ref "R13") (pin "1") (pinfunction "1_1") (pintype "passive"))
      (node (ref "R15") (pin "2") (pinfunction "2_2") (pintype "passive"))
      (node (ref "R19") (pin "2") (pinfunction "2_2") (pintype "passive"))
      (node (ref "R20") (pin "2") (pinfunction "2_2") (pintype "passive"))
      (node (ref "U1") (pin "9") (pinfunction "VIN+_9") (pintype "bidirectional"))
    )
    (net (code "144") (name "Net-(U1-VIN-)") (class "Default")
      (node (ref "C43") (pin "1") (pinfunction "1_1") (pintype "passive"))
      (node (ref "R14") (pin "1") (pinfunction "1_1") (pintype "passive"))
      (node (ref "R16") (pin "2") (pinfunction "2_2") (pintype "passive"))
      (node (ref "R17") (pin "1") (pinfunction "1_1") (pintype "passive"))
      (node (ref "R18") (pin "1") (pinfunction "1_1") (pintype "passive"))
      (node (ref "U1") (pin "10") (pinfunction "VIN-_10") (pintype "bidirectional"))
    )
    (net (code "145") (name "Net-(U2-ENBL)") (class "Default")
      (node (ref "C24") (pin "1") (pinfunction "1_1") (pintype "passive"))
      (node (ref "C25") (pin "1") (pinfunction "1_1") (pintype "passive"))
      (node (ref "C50") (pin "1") (pinfunction "1_1") (pintype "passive"))
      (node (ref "C59") (pin "2") (pinfunction "2_2") (pintype "passive"))
      (node (ref "L2") (pin "2") (pinfunction "2_2") (pintype "passive"))
      (node (ref "U2") (pin "18") (pinfunction "ENBV_18") (pintype "bidirectional"))
      (node (ref "U2") (pin "19") (pinfunction "ENBL_19") (pintype "bidirectional"))
      (node (ref "U2") (pin "3") (pinfunction "VPSL_3") (pintype "bidirectional"))
    )
    (net (code "146") (name "Net-(U2-INH)") (class "Default")
      (node (ref "C23") (pin "1") (pinfunction "1_1") (pintype "passive"))
      (node (ref "C46") (pin "1") (pinfunction "1_1") (pintype "passive"))
      (node (ref "C61") (pin "1") (pinfunction "1_1") (pintype "passive"))
      (node (ref "U2") (pin "2") (pinfunction "INH_2") (pintype "bidirectional"))
    )
    (net (code "147") (name "Net-(U2-LMD)") (class "Default")
      (node (ref "C22") (pin "2") (pinfunction "2_2") (pintype "passive"))
      (node (ref "U2") (pin "1") (pinfunction "LMD_1") (pintype "bidirectional"))
    )
    (net (code "148") (name "Net-(U2-LON)") (class "Default")
      (node (ref "C16") (pin "1") (pinfunction "1_1") (pintype "passive"))
      (node (ref "R22") (pin "2") (pinfunction "2_2") (pintype "passive"))
      (node (ref "U2") (pin "4") (pinfunction "LON_4") (pintype "bidirectional"))
    )
    (net (code "149") (name "Net-(U2-LOP)") (class "Default")
      (node (ref "C17") (pin "2") (pinfunction "2_2") (pintype "passive"))
      (node (ref "U2") (pin "5") (pinfunction "LOP_5") (pintype "bidirectional"))
    )
    (net (code "150") (name "Net-(U2-RCLMP)") (class "Default")
      (node (ref "C20") (pin "1") (pinfunction "1_1") (pintype "passive"))
      (node (ref "C21") (pin "1") (pinfunction "1_1") (pintype "passive"))
      (node (ref "R21") (pin "1") (pinfunction "1_1") (pintype "passive"))
      (node (ref "U2") (pin "12") (pinfunction "RCLMP_12") (pintype "bidirectional"))
    )
    (net (code "151") (name "Net-(U2-VCM)") (class "Default")
      (node (ref "C18") (pin "1") (pinfunction "1_1") (pintype "passive"))
      (node (ref "C19") (pin "1") (pinfunction "1_1") (pintype "passive"))
      (node (ref "U2") (pin "11") (pinfunction "VCM_11") (pintype "bidirectional"))
    )
    (net (code "152") (name "Net-(U2-VIN)") (class "Default")
      (node (ref "C16") (pin "2") (pinfunction "2_2") (pintype "passive"))
      (node (ref "U2") (pin "8") (pinfunction "VIN_8") (pintype "bidirectional"))
    )
    (net (code "153") (name "Net-(U2-VIP)") (class "Default")
      (node (ref "C17") (pin "1") (pinfunction "1_1") (pintype "passive"))
      (node (ref "U2") (pin "7") (pinfunction "VIP_7") (pintype "bidirectional"))
    )
    (net (code "154") (name "Net-(U2-VOH)") (class "Default")
      (node (ref "C12") (pin "1") (pinfunction "1_1") (pintype "passive"))
      (node (ref "U2") (pin "15") (pinfunction "VOH_15") (pintype "bidirectional"))
    )
    (net (code "155") (name "Net-(U2-VOL)") (class "Default")
      (node (ref "C15") (pin "1") (pinfunction "1_1") (pintype "passive"))
      (node (ref "U2") (pin "16") (pinfunction "VOL_16") (pintype "bidirectional"))
    )
    (net (code "156") (name "Net-(U2-VPOS)") (class "Default")
      (node (ref "C26") (pin "1") (pinfunction "1_1") (pintype "passive"))
      (node (ref "C27") (pin "1") (pinfunction "1_1") (pintype "passive"))
      (node (ref "L6") (pin "2") (pinfunction "2_2") (pintype "passive"))
      (node (ref "U2") (pin "14") (pinfunction "VPOS_14") (pintype "bidirectional"))
    )
    (net (code "157") (name "Net-(U3-BP)") (class "Default")
      (node (ref "C30") (pin "2") (pinfunction "2_2") (pintype "passive"))
      (node (ref "U3") (pin "4") (pinfunction "BP_4") (pintype "input"))
    )
    (net (code "158") (name "Net-(U3-EN)") (class "Default")
      (node (ref "C33") (pin "1") (pinfunction "1_1") (pintype "passive"))
      (node (ref "L5") (pin "2") (pinfunction "2_2") (pintype "passive"))
      (node (ref "U3") (pin "1") (pinfunction "IN_1") (pintype "input"))
      (node (ref "U3") (pin "3") (pinfunction "EN_3") (pintype "input"))
    )
    (net (code "159") (name "Net-(U4-C+)") (class "Default")
      (node (ref "C85") (pin "2") (pinfunction "2_2") (pintype "passive"))
      (node (ref "U4") (pin "6") (pinfunction "C+_6") (pintype "bidirectional"))
    )
    (net (code "160") (name "Net-(U4-C-)") (class "Default")
      (node (ref "C85") (pin "1") (pinfunction "1_1") (pintype "passive"))
      (node (ref "U4") (pin "4") (pinfunction "C-_4") (pintype "bidirectional"))
    )
    (net (code "161") (name "Net-(U4-VIN)") (class "Default")
      (node (ref "C86") (pin "2") (pinfunction "2_2") (pintype "passive"))
      (node (ref "L9") (pin "1") (pinfunction "1_1") (pintype "passive"))
      (node (ref "U4") (pin "3") (pinfunction "~{SHDN}_3") (pintype "bidirectional"))
      (node (ref "U4") (pin "5") (pinfunction "VIN_5") (pintype "bidirectional"))
    )
    (net (code "162") (name "Net-(U4-VOUT)") (class "Default")
      (node (ref "C84") (pin "1") (pinfunction "1_1") (pintype "passive"))
      (node (ref "C87") (pin "2") (pinfunction "2_2") (pintype "passive"))
      (node (ref "L2") (pin "1") (pinfunction "1_1") (pintype "passive"))
      (node (ref "L6") (pin "1") (pinfunction "1_1") (pintype "passive"))
      (node (ref "U4") (pin "1") (pinfunction "VOUT_1") (pintype "bidirectional"))
    )
    (net (code "163") (name "Net-(U5-CLK_IN0)") (class "Default")
      (node (ref "R32") (pin "2") (pinfunction "2_2") (pintype "passive"))
      (node (ref "U5") (pin "5") (pinfunction "CLK_IN0_5") (pintype "input"))
    )
    (net (code "164") (name "Net-(U5-CLK_IN1)") (class "Default")
      (node (ref "R33") (pin "1") (pinfunction "1_1") (pintype "passive"))
      (node (ref "U5") (pin "6") (pinfunction "CLK_IN1_6") (pintype "input"))
    )
    (net (code "165") (name "Net-(U5-S0{slash}A0{slash}CLK_SEL)") (class "Default")
      (node (ref "JP10") (pin "1") (pinfunction "1_1") (pintype "passive"))
      (node (ref "U5") (pin "1") (pinfunction "S0/A0/CLK_SEL_1") (pintype "input"))
    )
    (net (code "166") (name "Net-(U5-S1{slash}A1)") (class "Default")
      (node (ref "JP10") (pin "2") (pinfunction "2_2") (pintype "passive"))
      (node (ref "U5") (pin "2") (pinfunction "S1/A1_2") (pintype "input"))
    )
    (net (code "167") (name "Net-(U6-B1)") (class "Default")
      (node (ref "JP13") (pin "10") (pinfunction "10_10") (pintype "passive"))
      (node (ref "U6") (pin "13") (pinfunction "B1_13") (pintype "bidirectional"))
    )
    (net (code "168") (name "Net-(U6-B2)") (class "Default")
      (node (ref "JP13") (pin "12") (pinfunction "12_12") (pintype "passive"))
      (node (ref "U6") (pin "12") (pinfunction "B2_12") (pintype "bidirectional"))
    )
    (net (code "169") (name "Net-(U6-B3)") (class "Default")
      (node (ref "JP13") (pin "14") (pinfunction "14_14") (pintype "passive"))
      (node (ref "U6") (pin "11") (pinfunction "B3_11") (pintype "bidirectional"))
    )
    (net (code "170") (name "Net-(U6-B4)") (class "Default")
      (node (ref "JP13") (pin "16") (pinfunction "16_16") (pintype "passive"))
      (node (ref "U6") (pin "10") (pinfunction "B4_10") (pintype "bidirectional"))
    )
    (net (code "171") (name "Net-(U8-B)") (class "Default")
      (node (ref "JP13") (pin "4") (pinfunction "4_4") (pintype "passive"))
      (node (ref "U8") (pin "4") (pinfunction "B_4") (pintype "output"))
    )
    (net (code "172") (name "Net-(U9-B)") (class "Default")
      (node (ref "JP13") (pin "6") (pinfunction "6_6") (pintype "passive"))
      (node (ref "U9") (pin "4") (pinfunction "B_4") (pintype "output"))
    )
    (net (code "173") (name "OA_ADC0") (class "Default")
      (node (ref "CHANNEL2") (pin "24") (pinfunction "ADC0_24") (pintype "bidirectional"))
      (node (ref "CON6") (pin "D10") (pinfunction "D10~{AA22}IO_L63N_1_D10") (pintype "bidirectional"))
      (node (ref "U1") (pin "17") (pinfunction "D0_17") (pintype "bidirectional"))
    )
    (net (code "174") (name "OA_ADC1") (class "Default")
      (node (ref "CHANNEL2") (pin "21") (pinfunction "ADC1_21") (pintype "bidirectional"))
      (node (ref "CON6") (pin "F11") (pinfunction "F11~{AB21}IO_L61N_1_F11") (pintype "bidirectional"))
      (node (ref "U1") (pin "18") (pinfunction "D1_18") (pintype "bidirectional"))
    )
    (net (code "175") (name "OA_ADC2") (class "Default")
      (node (ref "CHANNEL2") (pin "22") (pinfunction "ADC2_22") (pintype "bidirectional"))
      (node (ref "CON6") (pin "D11") (pinfunction "D11~{Y21}IO_L59P_1_D11") (pintype "bidirectional"))
      (node (ref "U1") (pin "19") (pinfunction "D2_19") (pintype "bidirectional"))
    )
    (net (code "176") (name "OA_ADC3") (class "Default")
      (node (ref "CHANNEL2") (pin "19") (pinfunction "ADC3_19") (pintype "bidirectional"))
      (node (ref "CON6") (pin "F12") (pinfunction "F12~{Y20}IO_L67N_1_F12") (pintype "bidirectional"))
      (node (ref "U1") (pin "20") (pinfunction "D3_20") (pintype "bidirectional"))
    )
    (net (code "177") (name "OA_ADC4") (class "Default")
      (node (ref "CHANNEL2") (pin "20") (pinfunction "ADC4_20") (pintype "bidirectional"))
      (node (ref "CON6") (pin "D12") (pinfunction "D12~{W20}IO_L53P_1_D12") (pintype "bidirectional"))
      (node (ref "U1") (pin "21") (pinfunction "D4_21") (pintype "bidirectional"))
    )
    (net (code "178") (name "OA_ADC5") (class "Default")
      (node (ref "CHANNEL2") (pin "7") (pinfunction "ADC5_7") (pintype "bidirectional"))
      (node (ref "CON6") (pin "F13") (pinfunction "F13~{AB20}IO_L65N_1_F13") (pintype "bidirectional"))
      (node (ref "U1") (pin "22") (pinfunction "D5_22") (pintype "bidirectional"))
    )
    (net (code "179") (name "OA_ADC6") (class "Default")
      (node (ref "CHANNEL2") (pin "8") (pinfunction "ADC6_8") (pintype "bidirectional"))
      (node (ref "CON6") (pin "D13") (pinfunction "D13~{AA20}IO_L61P_1_D13") (pintype "bidirectional"))
      (node (ref "U1") (pin "25") (pinfunction "D6_25") (pintype "bidirectional"))
    )
    (net (code "180") (name "OA_ADC7") (class "Default")
      (node (ref "CHANNEL2") (pin "5") (pinfunction "ADC7_5") (pintype "bidirectional"))
      (node (ref "CON6") (pin "F14") (pinfunction "F14~{AB19}IO_L65P_1_F14") (pintype "bidirectional"))
      (node (ref "U1") (pin "26") (pinfunction "D7_26") (pintype "bidirectional"))
    )
    (net (code "181") (name "OA_ADC8") (class "Default")
      (node (ref "CHANNEL2") (pin "6") (pinfunction "ADC8_6") (pintype "bidirectional"))
      (node (ref "CON6") (pin "D14") (pinfunction "D14~{V19}IO_L71P_1_D14") (pintype "bidirectional"))
      (node (ref "U1") (pin "27") (pinfunction "D8_27") (pintype "bidirectional"))
    )
    (net (code "182") (name "OA_ADC9") (class "Default")
      (node (ref "CHANNEL2") (pin "3") (pinfunction "ADC9_3") (pintype "bidirectional"))
      (node (ref "CON6") (pin "F15") (pinfunction "F15~{AB18}IO_L2N_CMPMOSI_2_F15") (pintype "bidirectional"))
      (node (ref "U1") (pin "28") (pinfunction "D9_28") (pintype "bidirectional"))
    )
    (net (code "183") (name "OA_ADCOR") (class "Default")
      (node (ref "CHANNEL2") (pin "4") (pinfunction "ADCOR_4") (pintype "bidirectional"))
      (node (ref "CON6") (pin "D15") (pinfunction "D15~{Y19}IO_L67P_1_D15") (pintype "bidirectional"))
      (node (ref "U1") (pin "1") (pinfunction "OR_1") (pintype "bidirectional"))
    )
    (net (code "184") (name "OA_CLKADC") (class "Default")
      (node (ref "CHANNEL2") (pin "23") (pinfunction "CLKADC_23") (pintype "bidirectional"))
      (node (ref "CON6") (pin "F10") (pinfunction "F10~{AA21}IO_L63P_1_F10") (pintype "bidirectional"))
      (node (ref "R25") (pin "2") (pinfunction "2_2") (pintype "passive"))
      (node (ref "U1") (pin "13") (pinfunction "CLK_13") (pintype "bidirectional"))
    )
    (net (code "185") (name "OA_CLKIN") (class "Default")
      (node (ref "CHANNEL2") (pin "1") (pinfunction "CLKIN_1") (pintype "bidirectional"))
      (node (ref "CON6") (pin "C20") (pinfunction "C20~{Y11}IO_L31P_GCLK31_D14_2_C20") (pintype "bidirectional"))
      (node (ref "D3") (pin "1") (pinfunction "CA_1") (pintype "passive"))
      (node (ref "R31") (pin "2") (pinfunction "2_2") (pintype "passive"))
      (node (ref "R47") (pin "2") (pinfunction "2_2") (pintype "passive"))
    )
    (net (code "186") (name "OA_GAIN") (class "Default")
      (node (ref "CHANNEL2") (pin "25") (pinfunction "GAIN_25") (pintype "bidirectional"))
      (node (ref "CON6") (pin "D9") (pinfunction "D9~{Y22}IO_L59N_1_D9") (pintype "bidirectional"))
      (node (ref "R27") (pin "1") (pinfunction "1_1") (pintype "passive"))
    )
    (net (code "187") (name "OA_HILO") (class "Default")
      (node (ref "CHANNEL2") (pin "26") (pinfunction "HILO_26") (pintype "bidirectional"))
      (node (ref "CON6") (pin "D8") (pinfunction "D8~{V20}IO_L71N_1_D8") (pintype "bidirectional"))
      (node (ref "U2") (pin "13") (pinfunction "HILO_13") (pintype "bidirectional"))
    )
    (net (code "188") (name "OA_TRIGIN") (class "Default")
      (node (ref "CHANNEL2") (pin "2") (pinfunction "TRIGIN_2") (pintype "bidirectional"))
      (node (ref "CON6") (pin "D16") (pinfunction "D16~{V18}IO_L73N_1_D16") (pintype "bidirectional"))
    )
    (net (code "189") (name "PLLSCL") (class "Default")
      (node (ref "CON6") (pin "A29") (pinfunction "A29~{A5}IO_L2N_0_A29") (pintype "bidirectional"))
      (node (ref "JP7") (pin "2") (pinfunction "2_2") (pintype "passive"))
      (node (ref "R60") (pin "2") (pinfunction "2_2") (pintype "passive"))
      (node (ref "U5") (pin "10") (pinfunction "SCLOCK_10") (pintype "input"))
    )
    (net (code "190") (name "PLLSDA") (class "Default")
      (node (ref "CON6") (pin "B29") (pinfunction "B29~{C5}IO_L2P_0_B29") (pintype "bidirectional"))
      (node (ref "JP7") (pin "1") (pinfunction "1_1") (pintype "passive"))
      (node (ref "R59") (pin "2") (pinfunction "2_2") (pintype "passive"))
      (node (ref "U5") (pin "9") (pinfunction "SDATA_9") (pintype "input"))
    )
    (net (code "191") (name "PRG_MISO") (class "Default")
      (node (ref "IC4") (pin "14") (pinfunction "D5_14") (pintype "bidirectional"))
      (node (ref "IC5") (pin "17") (pinfunction "PB3(PDO/MISO)_17") (pintype "bidirectional"))
    )
    (net (code "192") (name "PRG_MOSI") (class "Default")
      (node (ref "IC4") (pin "15") (pinfunction "D4_15") (pintype "bidirectional"))
      (node (ref "IC5") (pin "16") (pinfunction "PB2(PDI/MISO)_16") (pintype "bidirectional"))
    )
    (net (code "193") (name "PRG_PDIC") (class "Default")
      (node (ref "IC4") (pin "17") (pinfunction "D2_17") (pintype "bidirectional"))
      (node (ref "IC5") (pin "11") (pinfunction "PD5(XCK)_11") (pintype "bidirectional"))
    )
    (net (code "194") (name "PRG_PDID") (class "Default")
      (node (ref "IC4") (pin "18") (pinfunction "D1_18") (pintype "bidirectional"))
      (node (ref "R41") (pin "2") (pinfunction "2_2") (pintype "passive"))
      (node (ref "R42") (pin "2") (pinfunction "2_2") (pintype "passive"))
    )
    (net (code "195") (name "PRG_RST") (class "Default")
      (node (ref "IC4") (pin "13") (pinfunction "D6_13") (pintype "bidirectional"))
      (node (ref "IC5") (pin "18") (pinfunction "PB4(T1)_18") (pintype "bidirectional"))
      (node (ref "R61") (pin "1") (pinfunction "1_1") (pintype "passive"))
    )
    (net (code "196") (name "PRG_SCK") (class "Default")
      (node (ref "IC4") (pin "16") (pinfunction "D3_16") (pintype "bidirectional"))
      (node (ref "IC5") (pin "15") (pinfunction "PB1(SCK)_15") (pintype "bidirectional"))
    )
    (net (code "197") (name "TARGET1") (class "Default")
      (node (ref "CON6") (pin "E13") (pinfunction "E13~{C16}IO_L65N_SCP2_0_E13") (pintype "bidirectional"))
      (node (ref "U6") (pin "2") (pinfunction "A1_2") (pintype "bidirectional"))
    )
    (net (code "198") (name "TARGET2") (class "Default")
      (node (ref "CON6") (pin "A13") (pinfunction "A13~{D17}IO_L65P_SCP3_0_A13") (pintype "bidirectional"))
      (node (ref "U6") (pin "3") (pinfunction "A2_3") (pintype "bidirectional"))
    )
    (net (code "199") (name "TARGET3") (class "Default")
      (node (ref "CON6") (pin "B12") (pinfunction "B12~{B18}IO_L66P_SCP1_0_B12") (pintype "bidirectional"))
      (node (ref "U6") (pin "4") (pinfunction "A3_4") (pintype "bidirectional"))
    )
    (net (code "200") (name "TARGET4") (class "Default")
      (node (ref "CON6") (pin "A12") (pinfunction "A12~{A18}IO_L66N_SCP0_0_A12") (pintype "bidirectional"))
      (node (ref "U6") (pin "5") (pinfunction "A4_5") (pintype "bidirectional"))
    )
    (net (code "201") (name "unconnected-(CHANNEL1-CLKIN-Pad1)") (class "Default")
      (node (ref "CHANNEL1") (pin "1") (pinfunction "CLKIN_1") (pintype "bidirectional"))
    )
    (net (code "202") (name "unconnected-(CHANNEL1-NC-Pad13)") (class "Default")
      (node (ref "CHANNEL1") (pin "13") (pinfunction "NC_13") (pintype "bidirectional"))
    )
    (net (code "203") (name "unconnected-(CHANNEL1-NC-Pad14)") (class "Default")
      (node (ref "CHANNEL1") (pin "14") (pinfunction "NC_14") (pintype "bidirectional"))
    )
    (net (code "204") (name "unconnected-(CHANNEL1-NC-Pad15)") (class "Default")
      (node (ref "CHANNEL1") (pin "15") (pinfunction "NC_15") (pintype "bidirectional"))
    )
    (net (code "205") (name "unconnected-(CHANNEL1-NC-Pad16)") (class "Default")
      (node (ref "CHANNEL1") (pin "16") (pinfunction "NC_16") (pintype "bidirectional"))
    )
    (net (code "206") (name "unconnected-(CHANNEL1-NC-Pad17)") (class "Default")
      (node (ref "CHANNEL1") (pin "17") (pinfunction "NC_17") (pintype "bidirectional"))
    )
    (net (code "207") (name "unconnected-(CHANNEL1-NC-Pad18)") (class "Default")
      (node (ref "CHANNEL1") (pin "18") (pinfunction "NC_18") (pintype "bidirectional"))
    )
    (net (code "208") (name "unconnected-(CHANNEL2-NC-Pad13)") (class "Default")
      (node (ref "CHANNEL2") (pin "13") (pinfunction "NC_13") (pintype "bidirectional"))
    )
    (net (code "209") (name "unconnected-(CHANNEL2-NC-Pad14)") (class "Default")
      (node (ref "CHANNEL2") (pin "14") (pinfunction "NC_14") (pintype "bidirectional"))
    )
    (net (code "210") (name "unconnected-(CHANNEL2-NC-Pad15)") (class "Default")
      (node (ref "CHANNEL2") (pin "15") (pinfunction "NC_15") (pintype "bidirectional"))
    )
    (net (code "211") (name "unconnected-(CHANNEL2-NC-Pad16)") (class "Default")
      (node (ref "CHANNEL2") (pin "16") (pinfunction "NC_16") (pintype "bidirectional"))
    )
    (net (code "212") (name "unconnected-(CHANNEL2-NC-Pad17)") (class "Default")
      (node (ref "CHANNEL2") (pin "17") (pinfunction "NC_17") (pintype "bidirectional"))
    )
    (net (code "213") (name "unconnected-(CHANNEL2-NC-Pad18)") (class "Default")
      (node (ref "CHANNEL2") (pin "18") (pinfunction "NC_18") (pintype "bidirectional"))
    )
    (net (code "214") (name "unconnected-(CON6A-A9~{A20}IO_L16N_1-PadA9)") (class "Default")
      (node (ref "CON6") (pin "A9") (pinfunction "A9~{A20}IO_L16N_1_A9") (pintype "bidirectional"))
    )
    (net (code "215") (name "unconnected-(CON6A-A30~{B3}IO_L1P_HSWAPEN_0-PadA30)") (class "Default")
      (node (ref "CON6") (pin "A30") (pinfunction "A30~{B3}IO_L1P_HSWAPEN_0_A30") (pintype "bidirectional"))
    )
    (net (code "216") (name "unconnected-(CON6A-B9~{A19}IO_L16P_1-PadB9)") (class "Default")
      (node (ref "CON6") (pin "B9") (pinfunction "B9~{A19}IO_L16P_1_B9") (pintype "bidirectional"))
    )
    (net (code "217") (name "unconnected-(CON6A-B15~{D15}IO_L46P_0-PadB15)") (class "Default")
      (node (ref "CON6") (pin "B15") (pinfunction "B15~{D15}IO_L46P_0_B15") (pintype "bidirectional"))
    )
    (net (code "218") (name "unconnected-(CON6A-B27~{D7}IO_L7P_0-PadB27)") (class "Default")
      (node (ref "CON6") (pin "B27") (pinfunction "B27~{D7}IO_L7P_0_B27") (pintype "bidirectional"))
    )
    (net (code "219") (name "unconnected-(CON6A-B30~{A6}IO_L4N_0-PadB30)") (class "Default")
      (node (ref "CON6") (pin "B30") (pinfunction "B30~{A6}IO_L4N_0_B30") (pintype "bidirectional"))
    )
    (net (code "220") (name "unconnected-(CON6A-E15~{A16}IO_L63N_SCP6_0-PadE15)") (class "Default")
      (node (ref "CON6") (pin "E15") (pinfunction "E15~{A16}IO_L63N_SCP6_0_E15") (pintype "bidirectional"))
    )
    (net (code "221") (name "unconnected-(CON6A-E16~{B12}IO_L36P_GCLK15_0-PadE16)") (class "Default")
      (node (ref "CON6") (pin "E16") (pinfunction "E16~{B12}IO_L36P_GCLK15_0_E16") (pintype "bidirectional"))
    )
    (net (code "222") (name "unconnected-(CON6A-E26~{A7}IO_L5N_0-PadE26)") (class "Default")
      (node (ref "CON6") (pin "E26") (pinfunction "E26~{A7}IO_L5N_0_E26") (pintype "bidirectional"))
    )
    (net (code "223") (name "unconnected-(CON6A-E27~{B6}IO_L4P_0-PadE27)") (class "Default")
      (node (ref "CON6") (pin "E27") (pinfunction "E27~{B6}IO_L4P_0_E27") (pintype "bidirectional"))
    )
    (net (code "224") (name "unconnected-(CON6C-E12~{VREF_IO}-PadE12)") (class "Default")
      (node (ref "CON6") (pin "E12") (pinfunction "E12~{VREF_IO}_E12") (pintype "bidirectional"))
    )
    (net (code "225") (name "unconnected-(CON6C-E28~{VREF_IO}-PadE28)") (class "Default")
      (node (ref "CON6") (pin "E28") (pinfunction "E28~{VREF_IO}_E28") (pintype "bidirectional"))
    )
    (net (code "226") (name "unconnected-(CON6D-C3~{L20}IO_L43P_GCLK5_M1DQ4_1-PadC3)") (class "Default")
      (node (ref "CON6") (pin "C3") (pinfunction "C3~{L20}IO_L43P_GCLK5_M1DQ4_1_C3") (pintype "bidirectional"))
    )
    (net (code "227") (name "unconnected-(CON6D-F27~{Y8}IO_L47N_2-PadF27)") (class "Default")
      (node (ref "CON6") (pin "F27") (pinfunction "F27~{Y8}IO_L47N_2_F27") (pintype "bidirectional"))
    )
    (net (code "228") (name "unconnected-(CON6D-F28~{AB7}IO_L63N_2-PadF28)") (class "Default")
      (node (ref "CON6") (pin "F28") (pinfunction "F28~{AB7}IO_L63N_2_F28") (pintype "bidirectional"))
    )
    (net (code "229") (name "unconnected-(CON6D-F29~{Y7}IO_L63P_2-PadF29)") (class "Default")
      (node (ref "CON6") (pin "F29") (pinfunction "F29~{Y7}IO_L63P_2_F29") (pintype "bidirectional"))
    )
    (net (code "230") (name "unconnected-(CON6D-F30~{AB6}IO_L64N_D9_2-PadF30)") (class "Default")
      (node (ref "CON6") (pin "F30") (pinfunction "F30~{AB6}IO_L64N_D9_2_F30") (pintype "bidirectional"))
    )
    (net (code "231") (name "unconnected-(CON6D-F31~{AA6}IO_L64P_D8_2-PadF31)") (class "Default")
      (node (ref "CON6") (pin "F31") (pinfunction "F31~{AA6}IO_L64P_D8_2_F31") (pintype "bidirectional"))
    )
    (net (code "232") (name "unconnected-(CON6G-C30~{M0}-PadC30)") (class "Default")
      (node (ref "CON6") (pin "C30") (pinfunction "C30~{M0}_C30") (pintype "bidirectional"))
    )
    (net (code "233") (name "unconnected-(CON6G-C31~{M1}-PadC31)") (class "Default")
      (node (ref "CON6") (pin "C31") (pinfunction "C31~{M1}_C31") (pintype "bidirectional"))
    )
    (net (code "234") (name "unconnected-(D4-CA-Pad1)") (class "Default")
      (node (ref "D4") (pin "1") (pinfunction "CA_1") (pintype "passive"))
    )
    (net (code "235") (name "unconnected-(H1-MOUNT-PadB2,8)") (class "Default")
      (node (ref "H1") (pin "B2,8") (pinfunction "MOUNT_B2,8") (pintype "passive"))
    )
    (net (code "236") (name "unconnected-(IC4-D7-Pad12)") (class "Default")
      (node (ref "IC4") (pin "12") (pinfunction "D7_12") (pintype "bidirectional"))
    )
    (net (code "237") (name "unconnected-(IC4-D8-Pad11)") (class "Default")
      (node (ref "IC4") (pin "11") (pinfunction "D8_11") (pintype "bidirectional"))
    )
    (net (code "238") (name "unconnected-(IC5-PB0(SS)-Pad14)") (class "Default")
      (node (ref "IC5") (pin "14") (pinfunction "PB0(SS)_14") (pintype "bidirectional"))
    )
    (net (code "239") (name "unconnected-(IC5-PB5-Pad19)") (class "Default")
      (node (ref "IC5") (pin "19") (pinfunction "PB5_19") (pintype "bidirectional"))
    )
    (net (code "240") (name "unconnected-(IC5-PB6-Pad20)") (class "Default")
      (node (ref "IC5") (pin "20") (pinfunction "PB6_20") (pintype "bidirectional"))
    )
    (net (code "241") (name "unconnected-(IC5-PB7(OC0A{slash}OC1C)-Pad21)") (class "Default")
      (node (ref "IC5") (pin "21") (pinfunction "PB7(OC0A/OC1C)_21") (pintype "bidirectional"))
    )
    (net (code "242") (name "unconnected-(IC5-PC2-Pad5)") (class "Default")
      (node (ref "IC5") (pin "5") (pinfunction "PC2_5") (pintype "bidirectional"))
    )
    (net (code "243") (name "unconnected-(IC5-PC4-Pad26)") (class "Default")
      (node (ref "IC5") (pin "26") (pinfunction "PC4_26") (pintype "bidirectional"))
    )
    (net (code "244") (name "unconnected-(IC5-PC5(OC1B)-Pad25)") (class "Default")
      (node (ref "IC5") (pin "25") (pinfunction "PC5(OC1B)_25") (pintype "bidirectional"))
    )
    (net (code "245") (name "unconnected-(IC5-PC6(OC1A)-Pad23)") (class "Default")
      (node (ref "IC5") (pin "23") (pinfunction "PC6(OC1A)_23") (pintype "bidirectional"))
    )
    (net (code "246") (name "unconnected-(IC5-PC7(ICP1{slash}INT4)-Pad22)") (class "Default")
      (node (ref "IC5") (pin "22") (pinfunction "PC7(ICP1/INT4)_22") (pintype "bidirectional"))
    )
    (net (code "247") (name "unconnected-(IC5-PD0(INT0{slash}OC0B)-Pad6)") (class "Default")
      (node (ref "IC5") (pin "6") (pinfunction "PD0(INT0/OC0B)_6") (pintype "bidirectional"))
    )
    (net (code "248") (name "unconnected-(IC5-PD1(INT1{slash}AIN0)-Pad7)") (class "Default")
      (node (ref "IC5") (pin "7") (pinfunction "PD1(INT1/AIN0)_7") (pintype "bidirectional"))
    )
    (net (code "249") (name "unconnected-(IC5-PD4(XCK{slash}T0)-Pad10)") (class "Default")
      (node (ref "IC5") (pin "10") (pinfunction "PD4(XCK/T0)_10") (pintype "bidirectional"))
    )
    (net (code "250") (name "unconnected-(IC5-PD6(INT6{slash}RTS)-Pad12)") (class "Default")
      (node (ref "IC5") (pin "12") (pinfunction "PD6(INT6/RTS)_12") (pintype "bidirectional"))
    )
    (net (code "251") (name "unconnected-(JP2-Pad3)") (class "Default")
      (node (ref "JP2") (pin "3") (pinfunction "3_3") (pintype "passive"))
    )
    (net (code "252") (name "unconnected-(U5-Y2-Pad15)") (class "Default")
      (node (ref "U5") (pin "15") (pinfunction "Y2_15") (pintype "output"))
    )
    (net (code "253") (name "unconnected-(U5-Y3-Pad16)") (class "Default")
      (node (ref "U5") (pin "16") (pinfunction "Y3_16") (pintype "output"))
    )
    (net (code "254") (name "unconnected-(U5-Y4-Pad19)") (class "Default")
      (node (ref "U5") (pin "19") (pinfunction "Y4_19") (pintype "output"))
    )
    (net (code "255") (name "unconnected-(U5-Y5-Pad20)") (class "Default")
      (node (ref "U5") (pin "20") (pinfunction "Y5_20") (pintype "output"))
    )
    (net (code "256") (name "unconnected-(U6-NC-Pad6)") (class "Default")
      (node (ref "U6") (pin "6") (pinfunction "NC_6") (pintype "no_connect"))
    )
    (net (code "257") (name "unconnected-(U6-NC_2-Pad9)") (class "Default")
      (node (ref "U6") (pin "9") (pinfunction "NC_2_9") (pintype "no_connect"))
    )
  )
)
